# oresat-backplane-2u-hasp.net
KiCad netlist of a schematic drawn in EAGLE
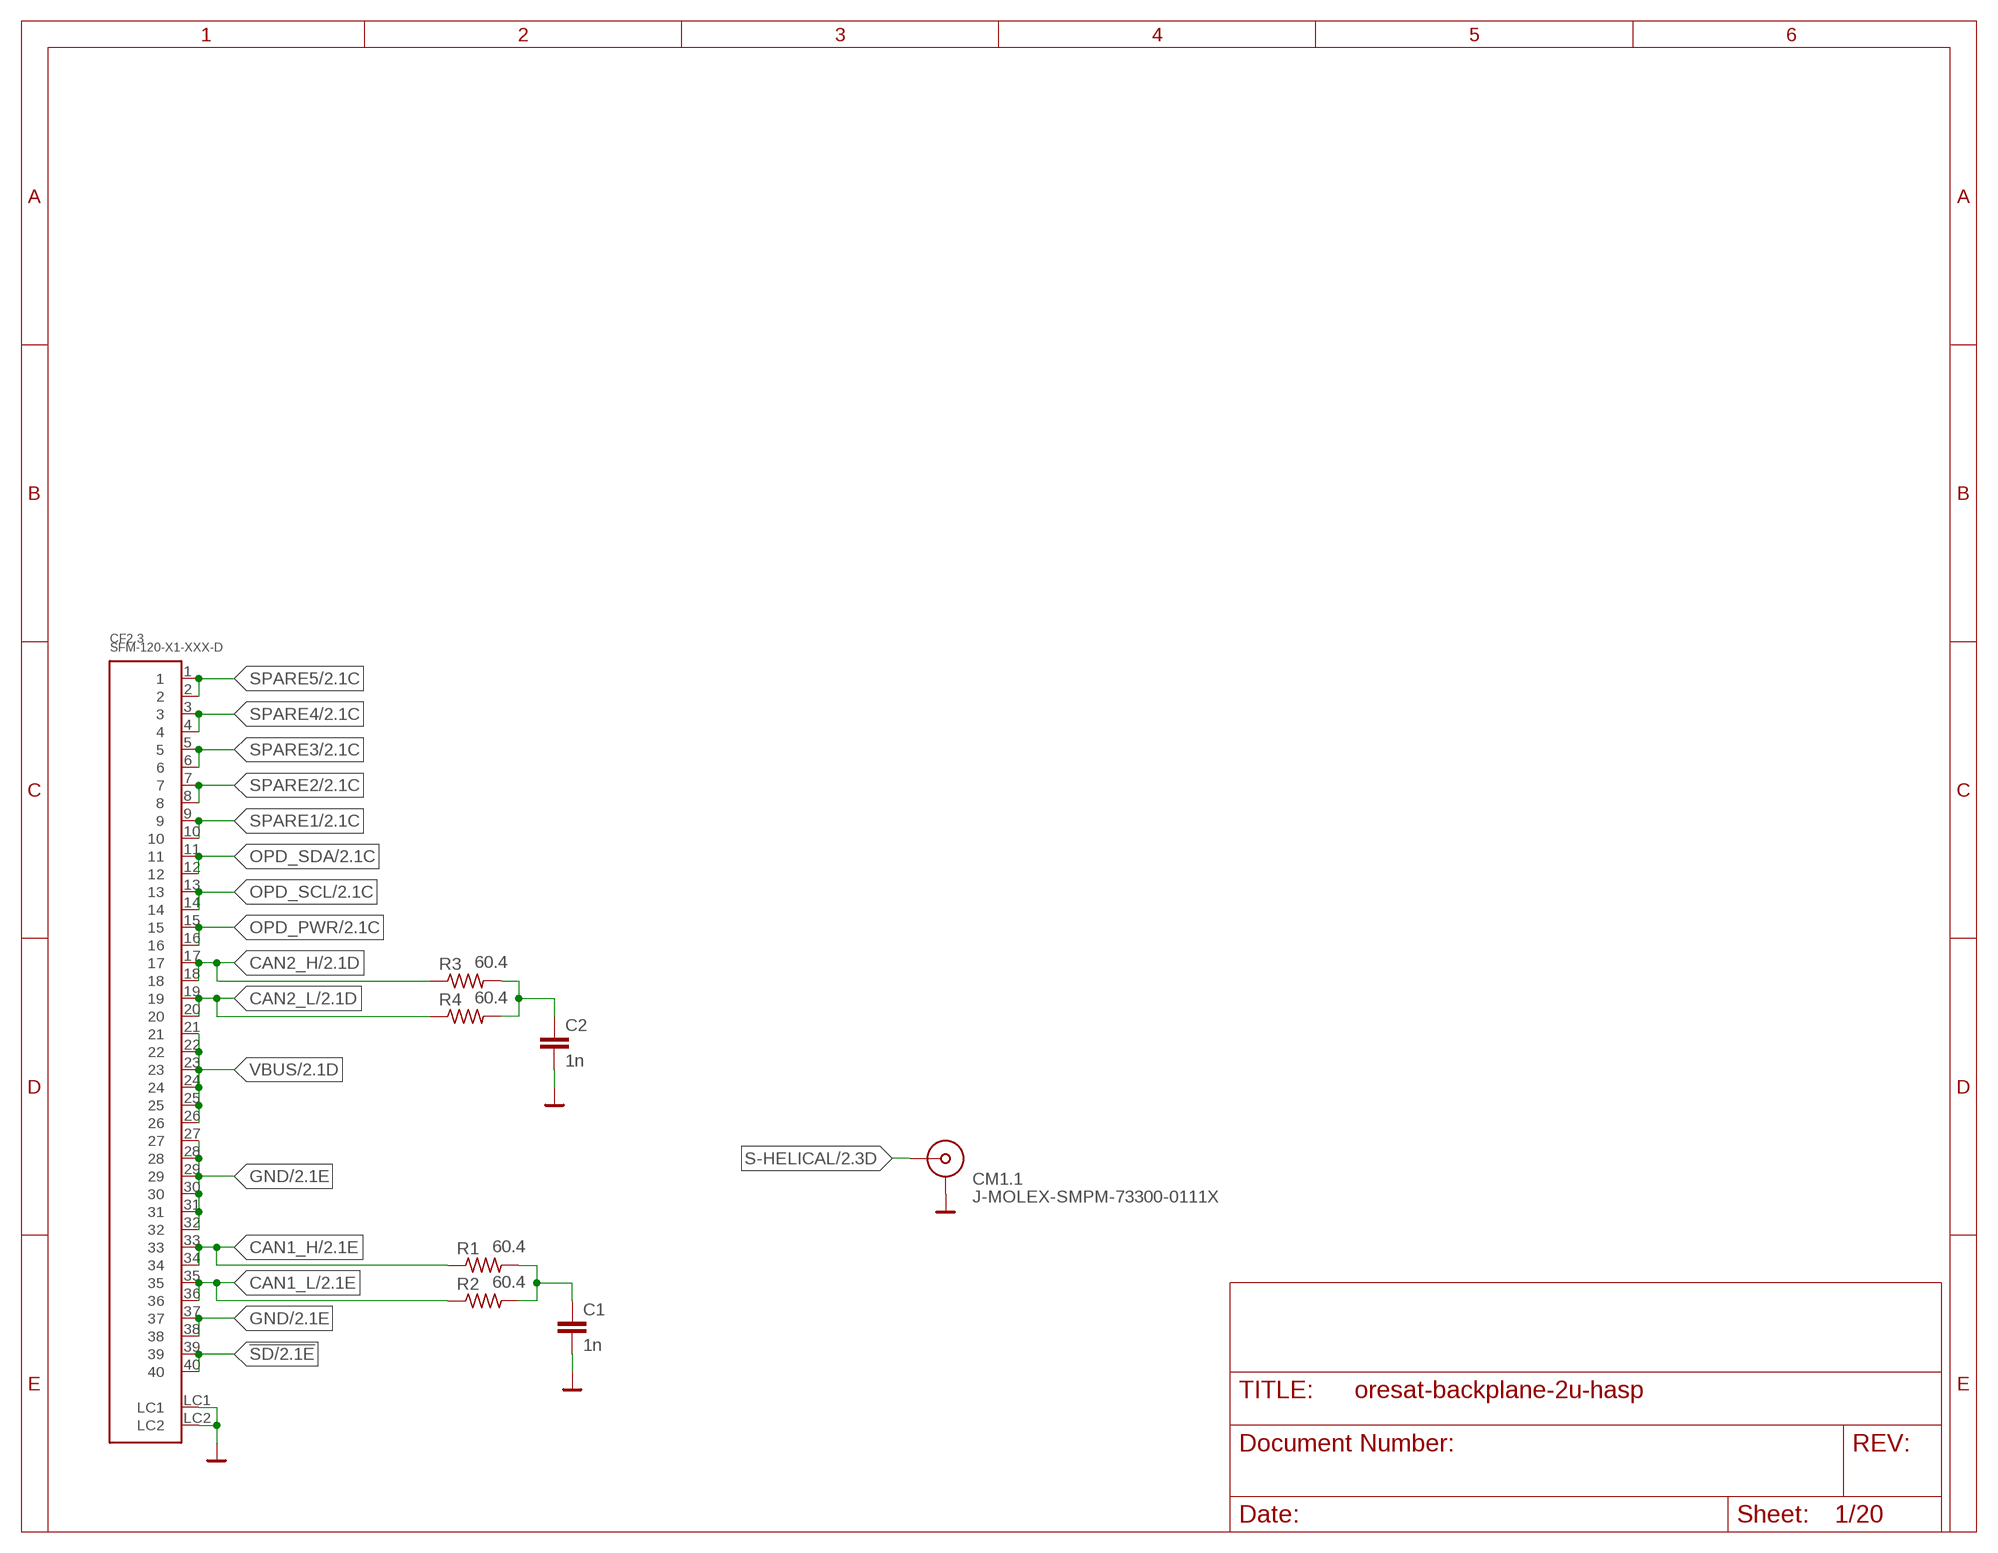
[diagram p0: schematic, sheet 1]
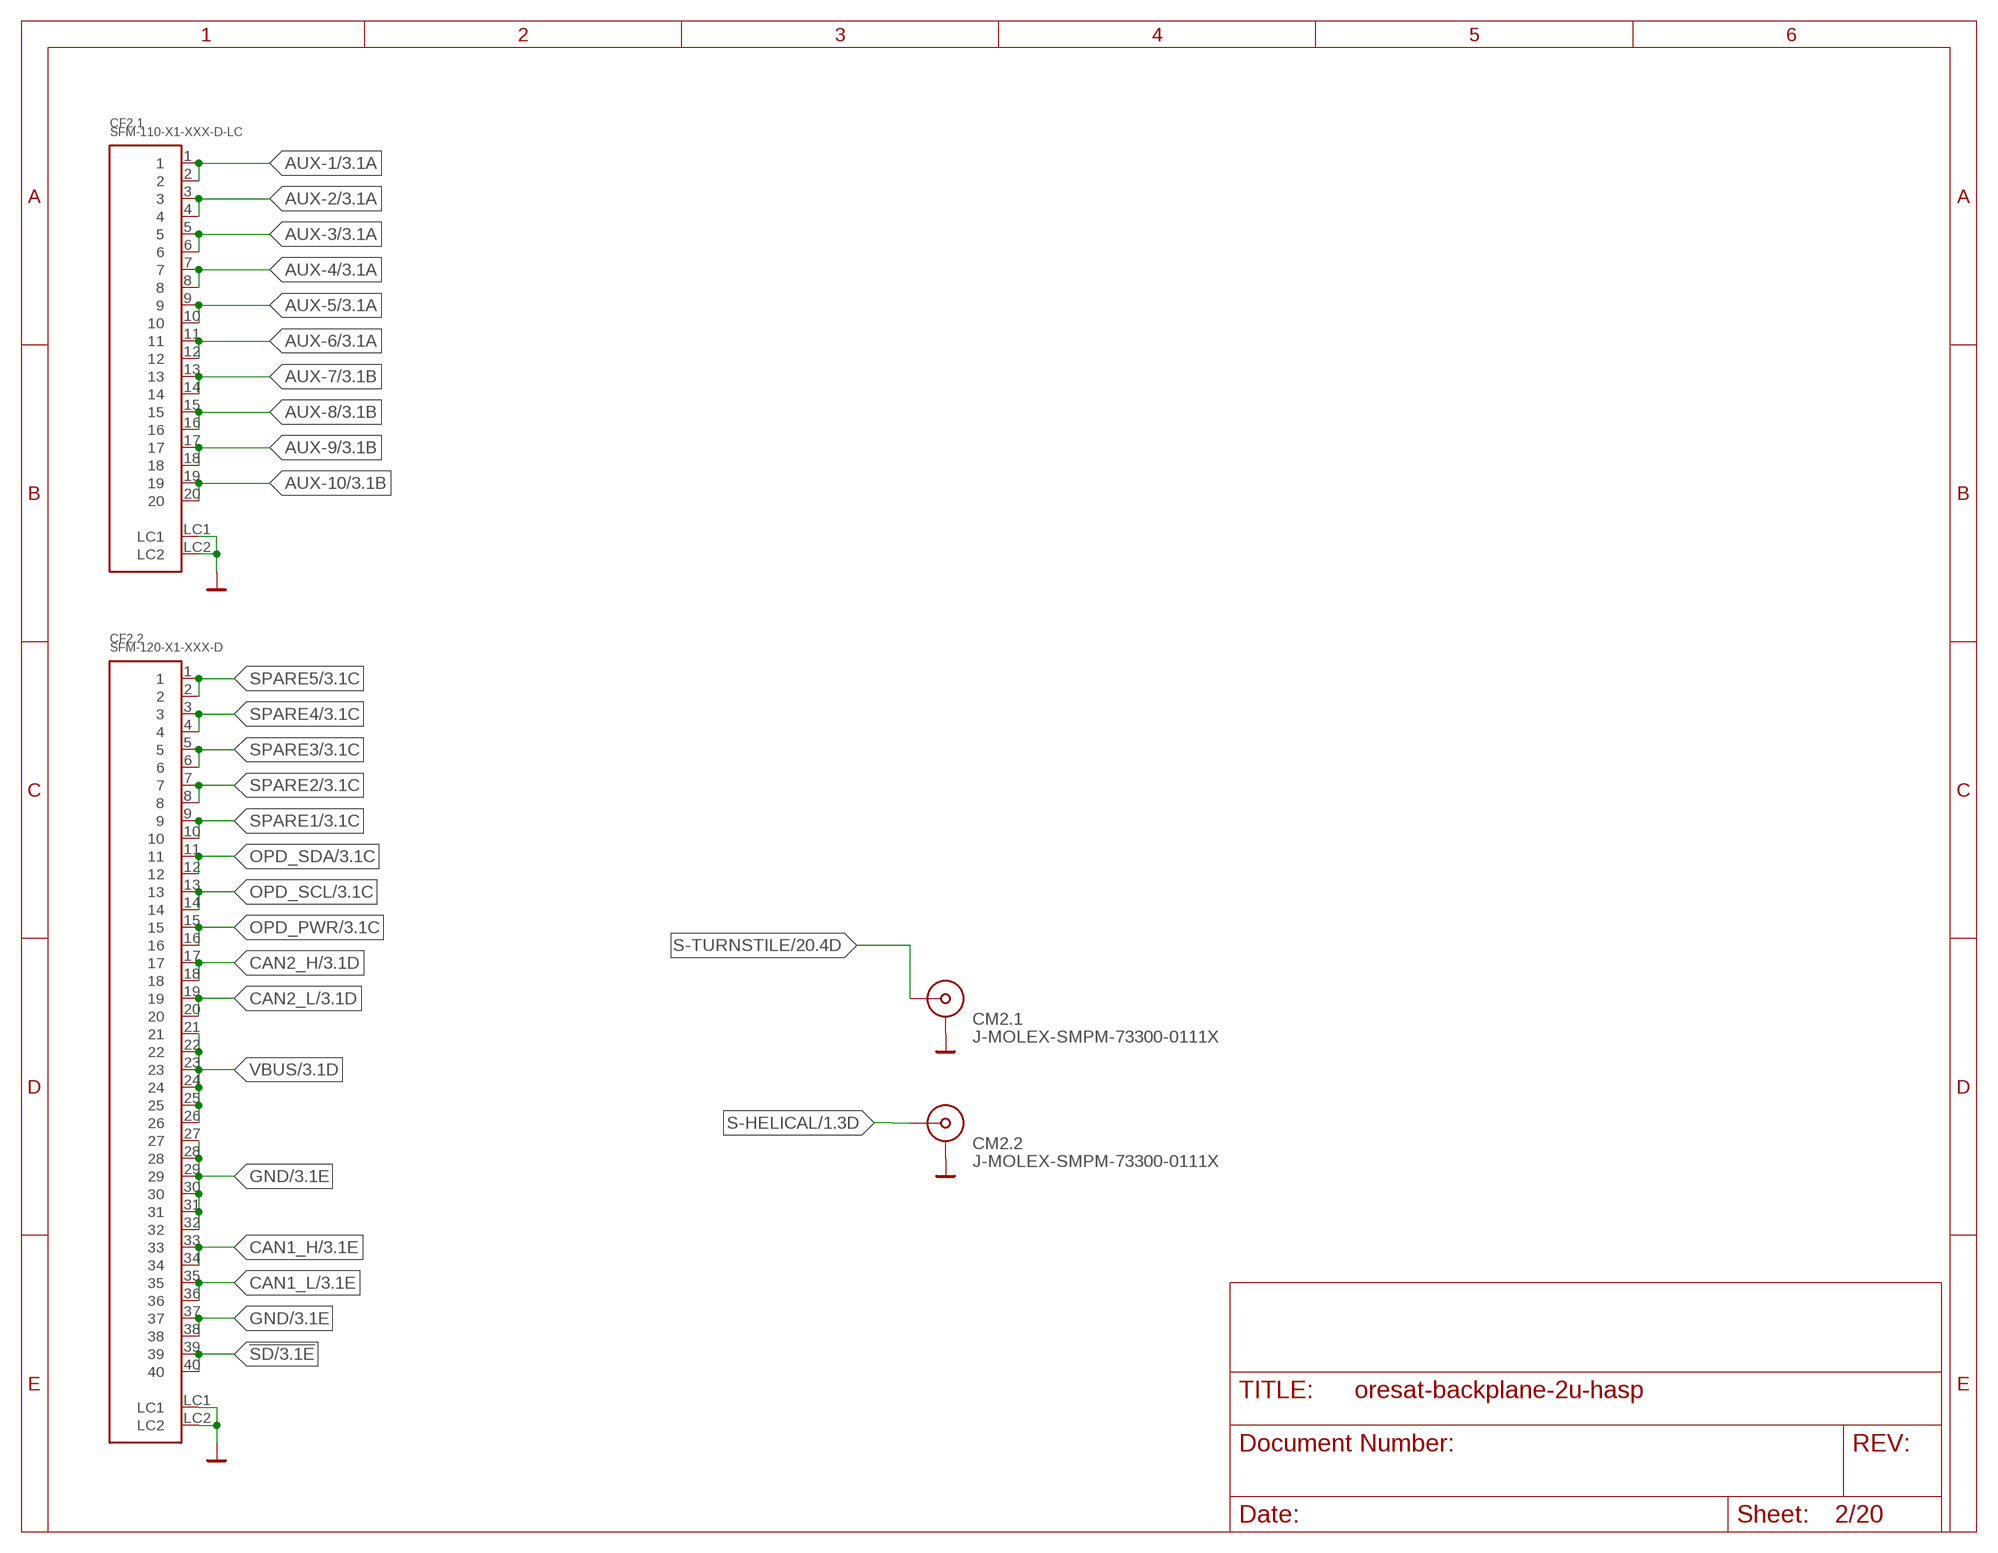
[diagram p1: schematic, sheet 2]
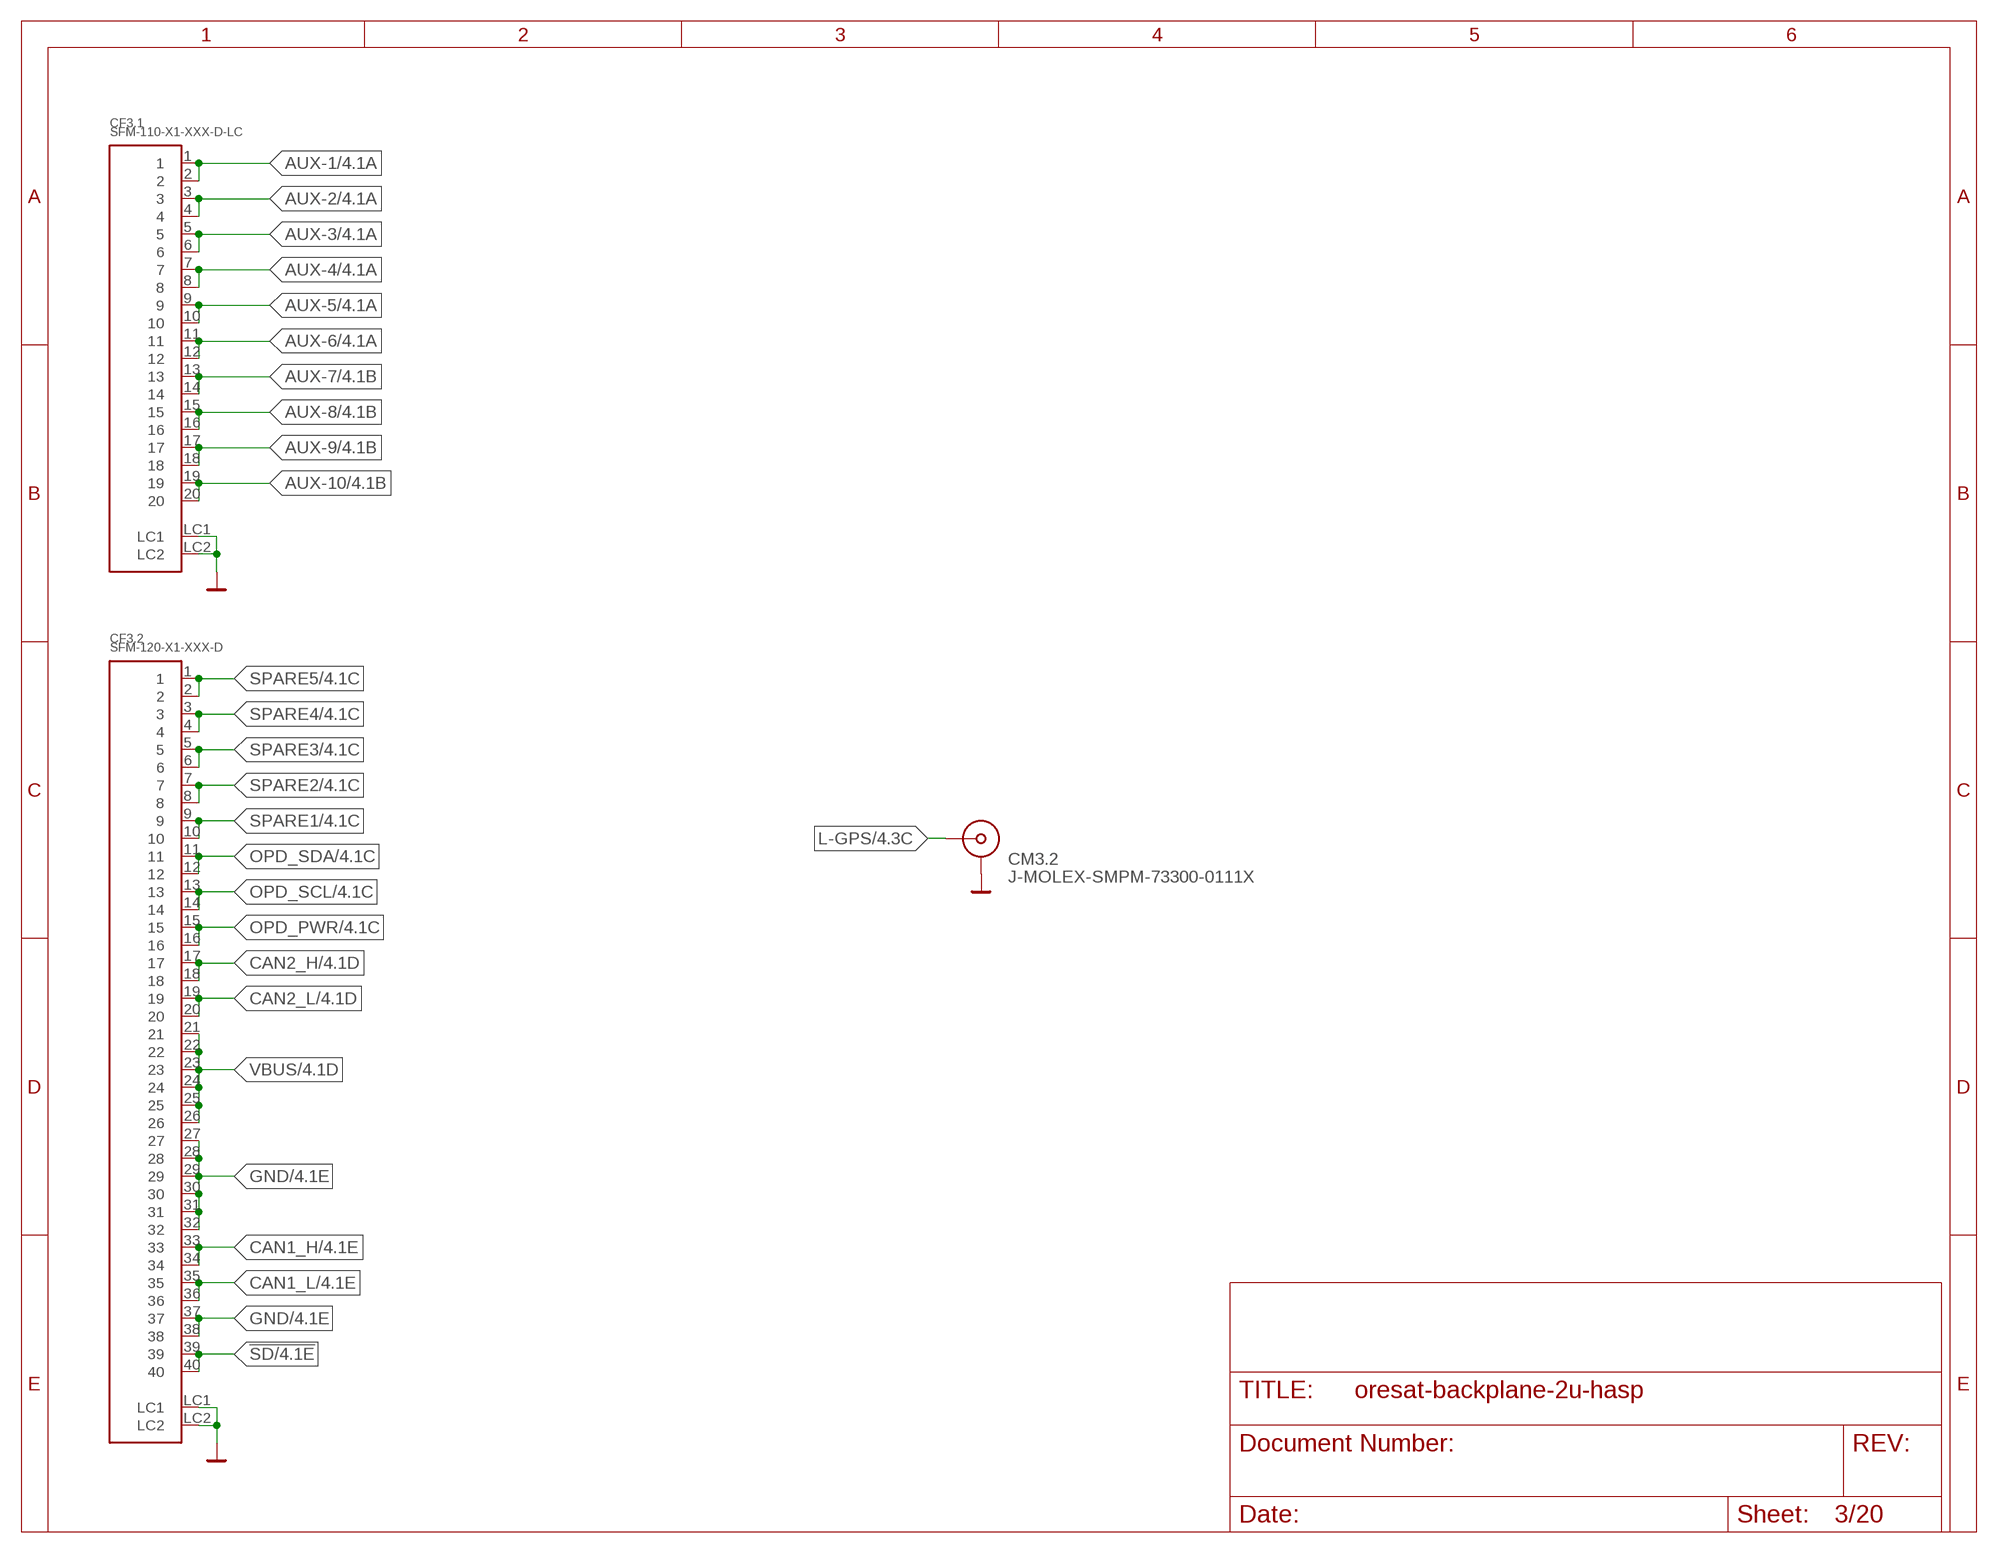
[diagram p2: schematic, sheet 3]
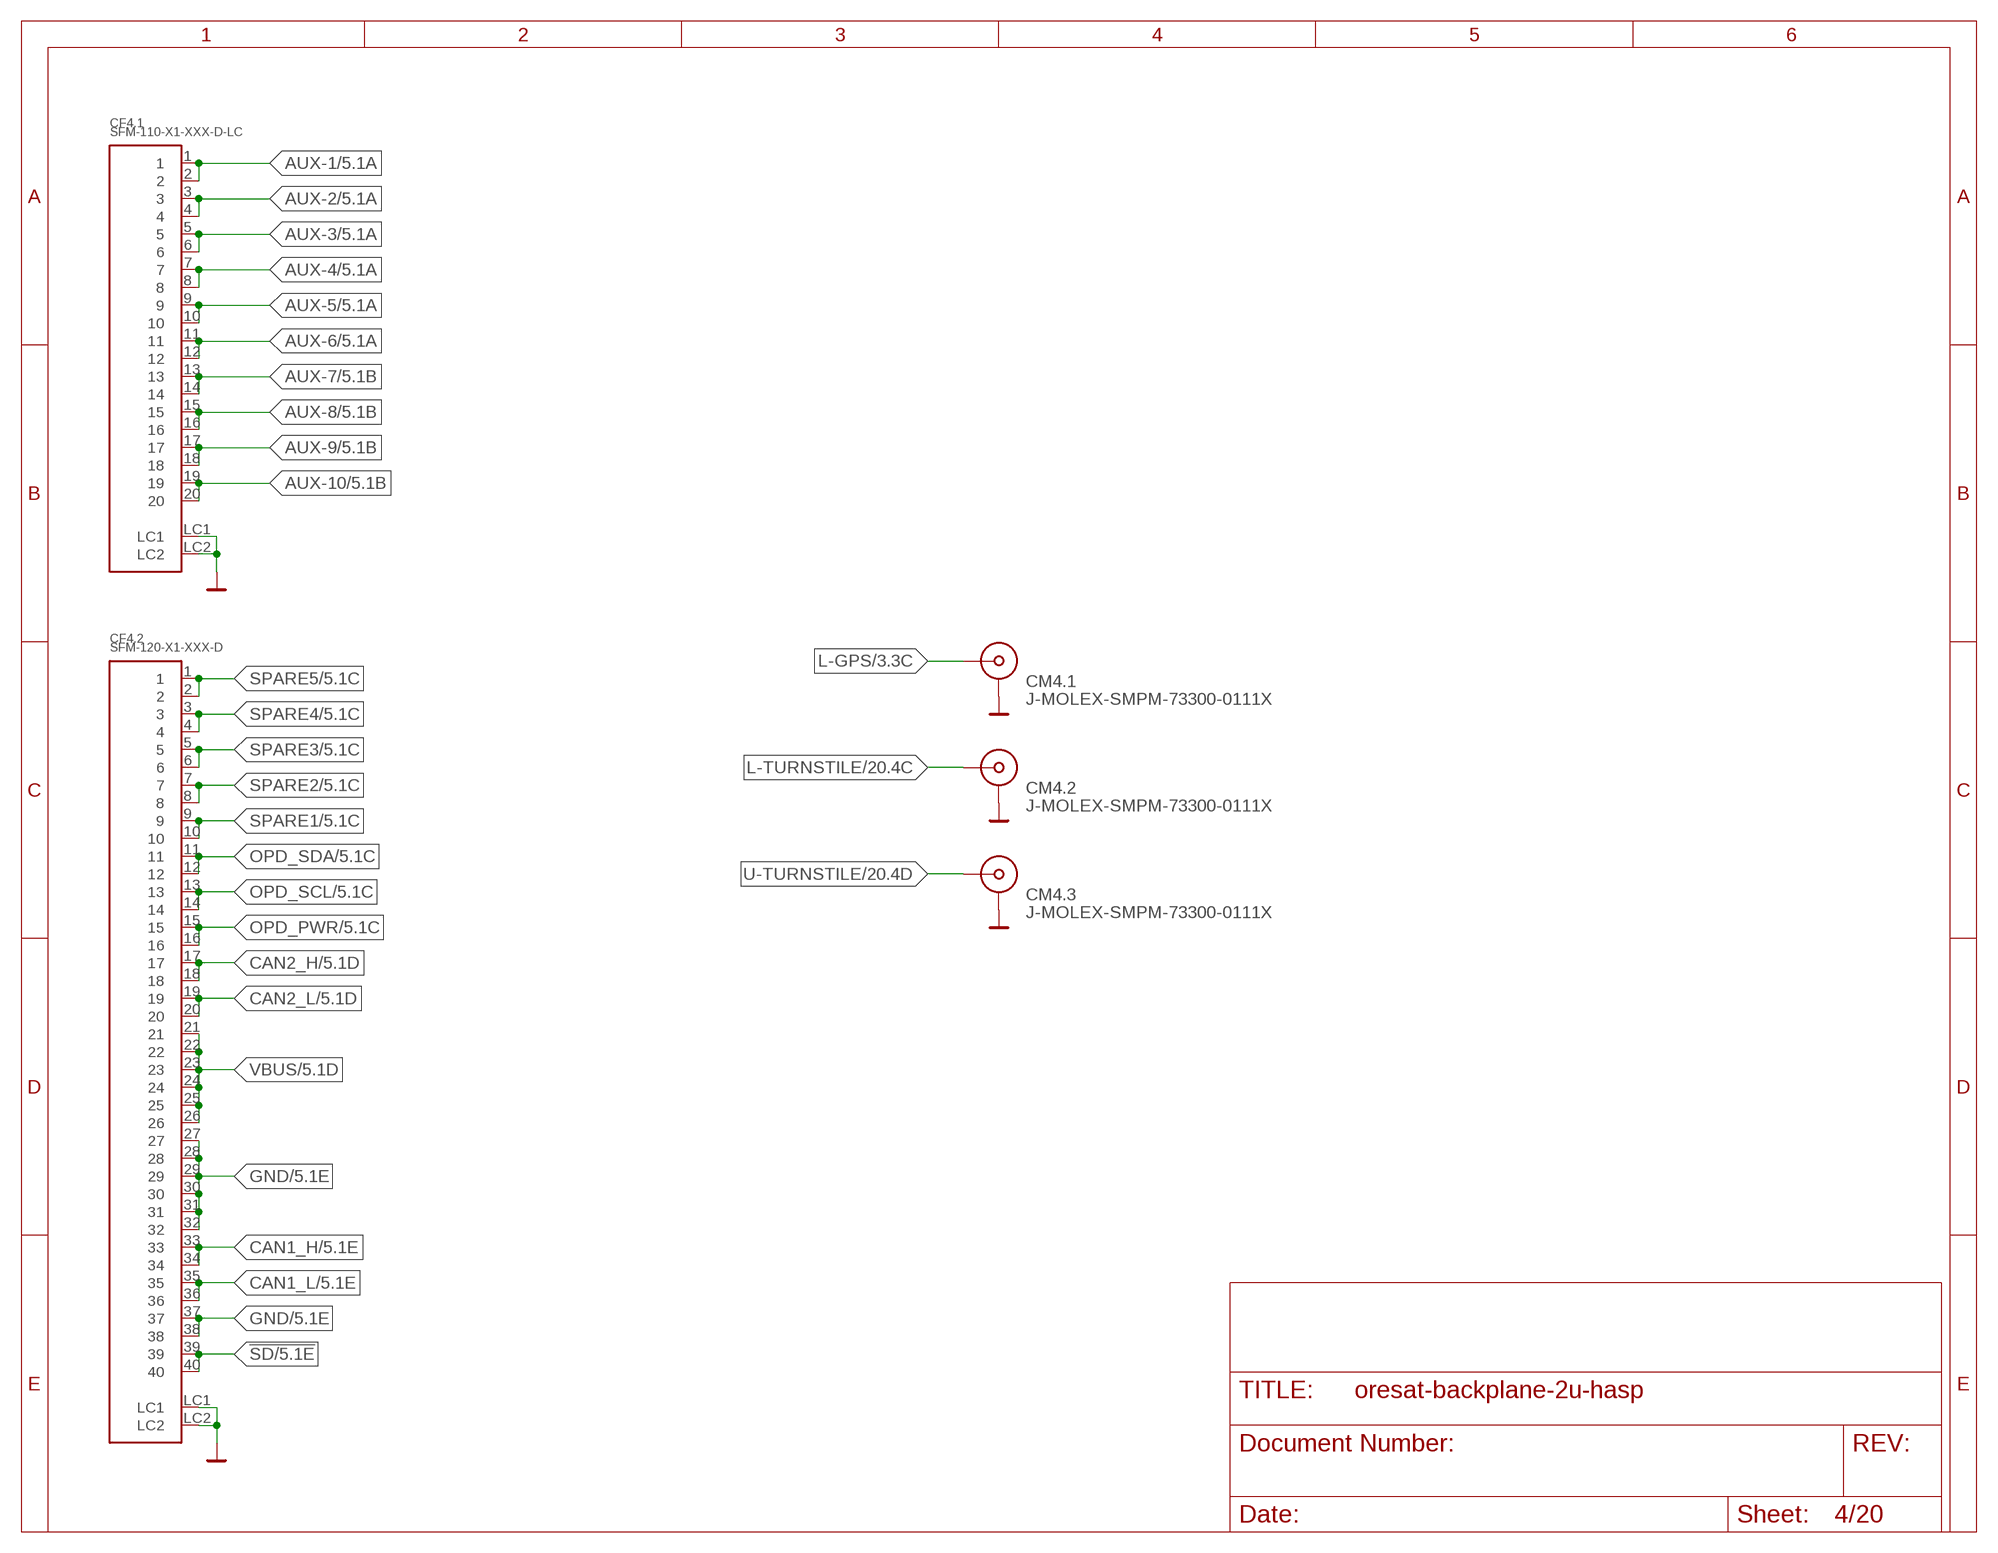
[diagram p3: schematic, sheet 4]
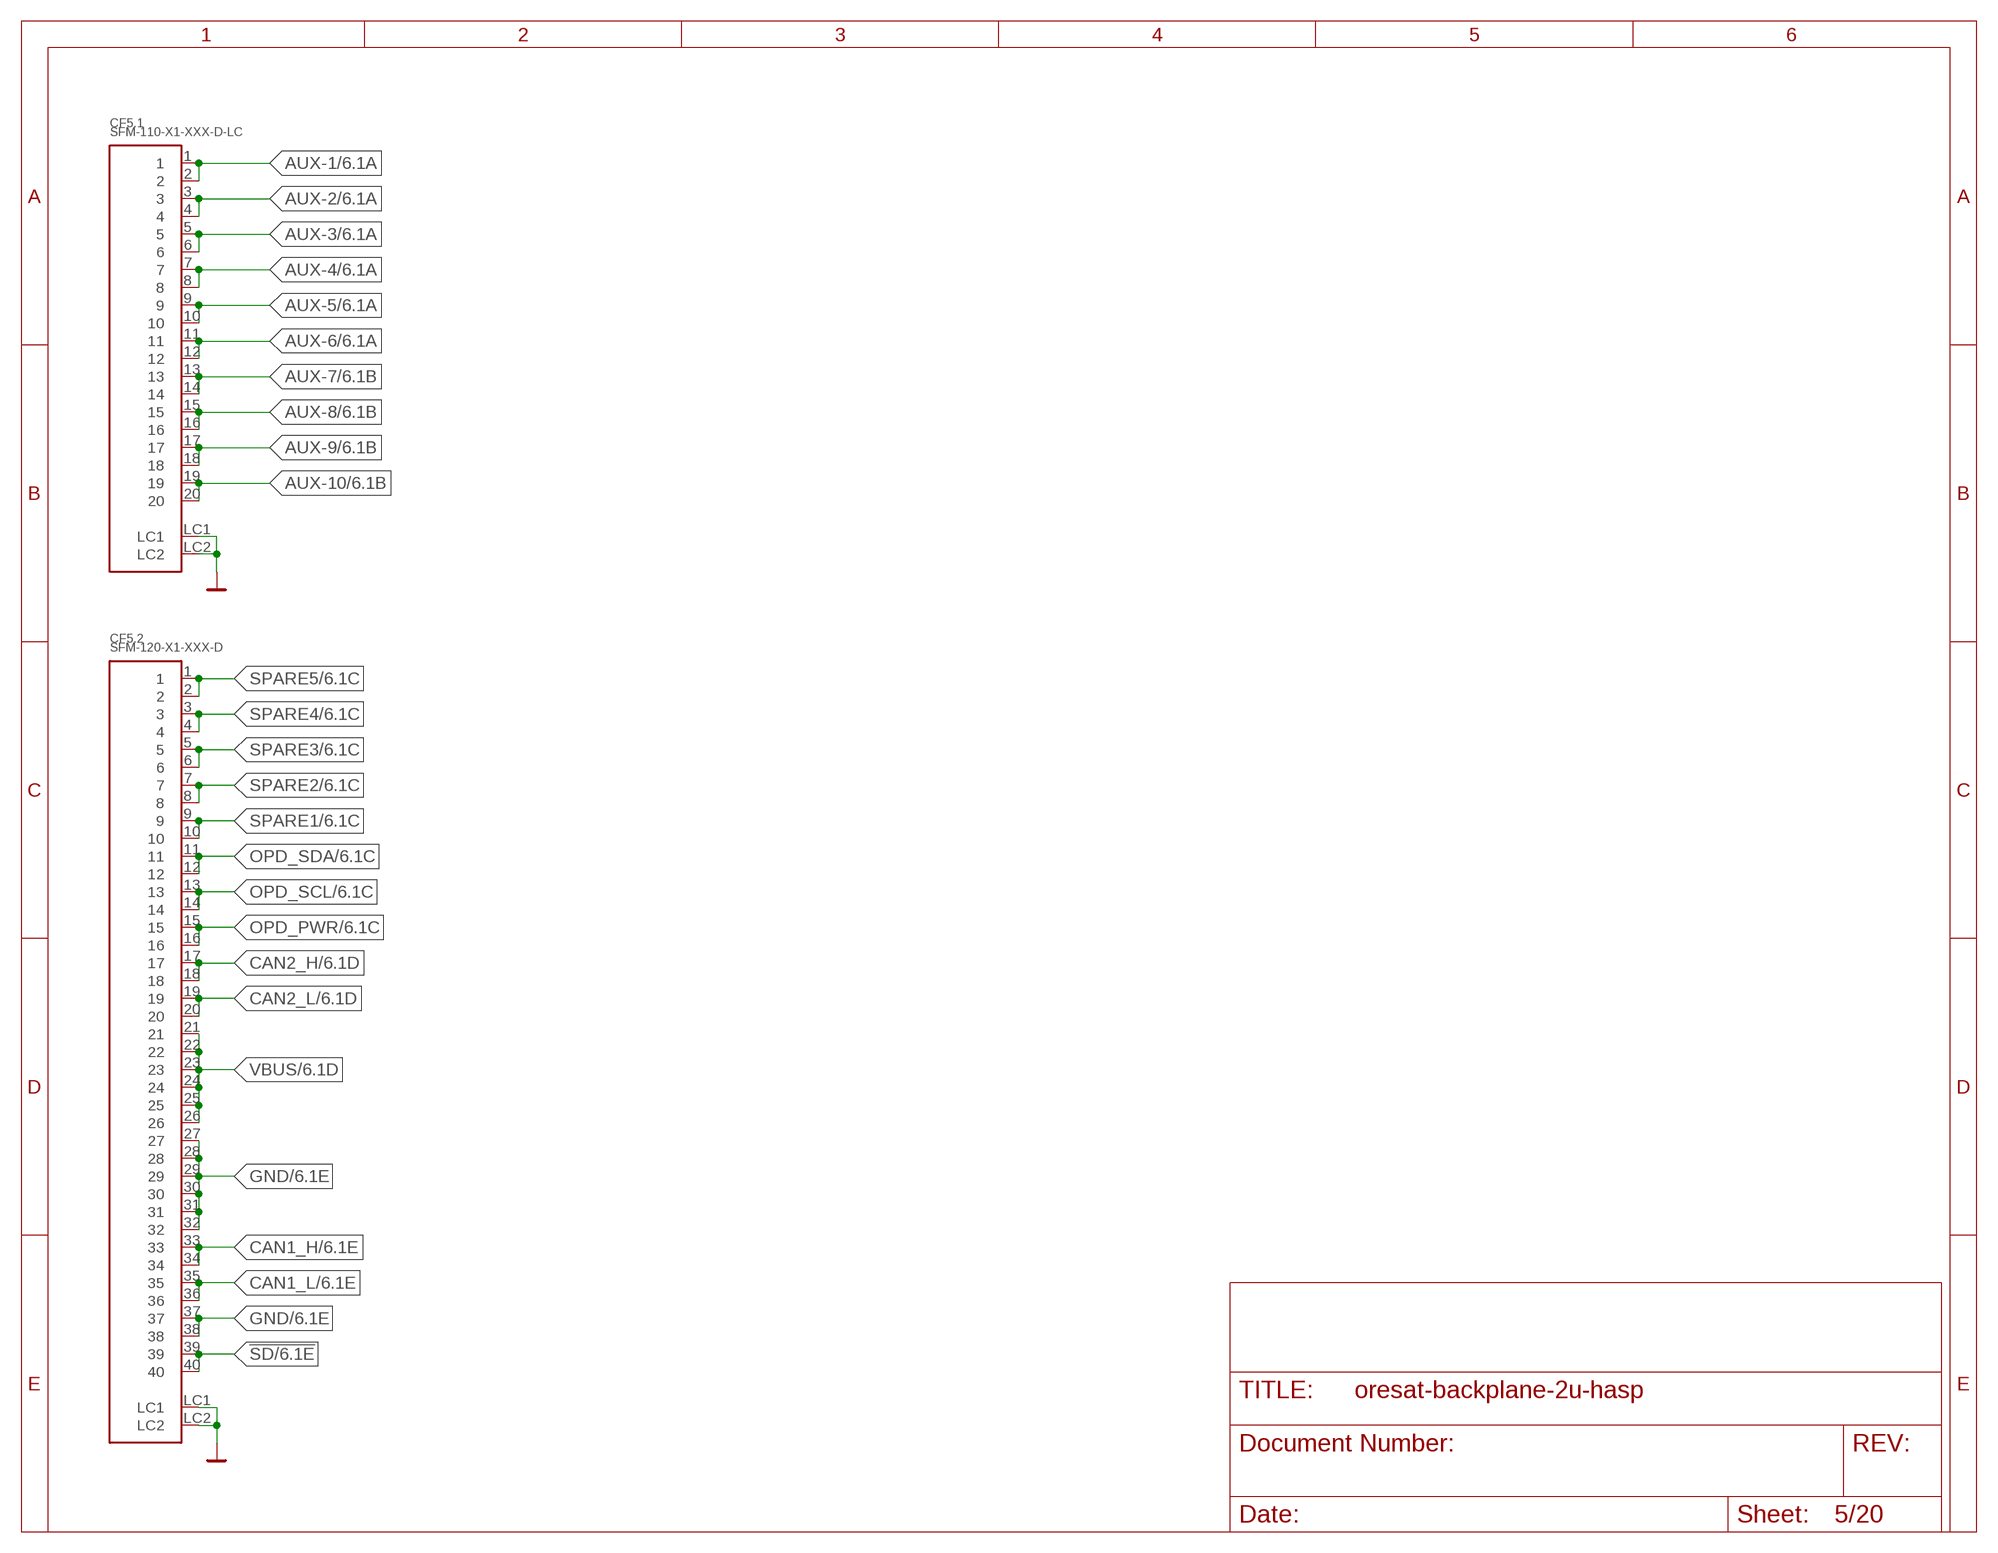
[diagram p4: schematic, sheet 5]
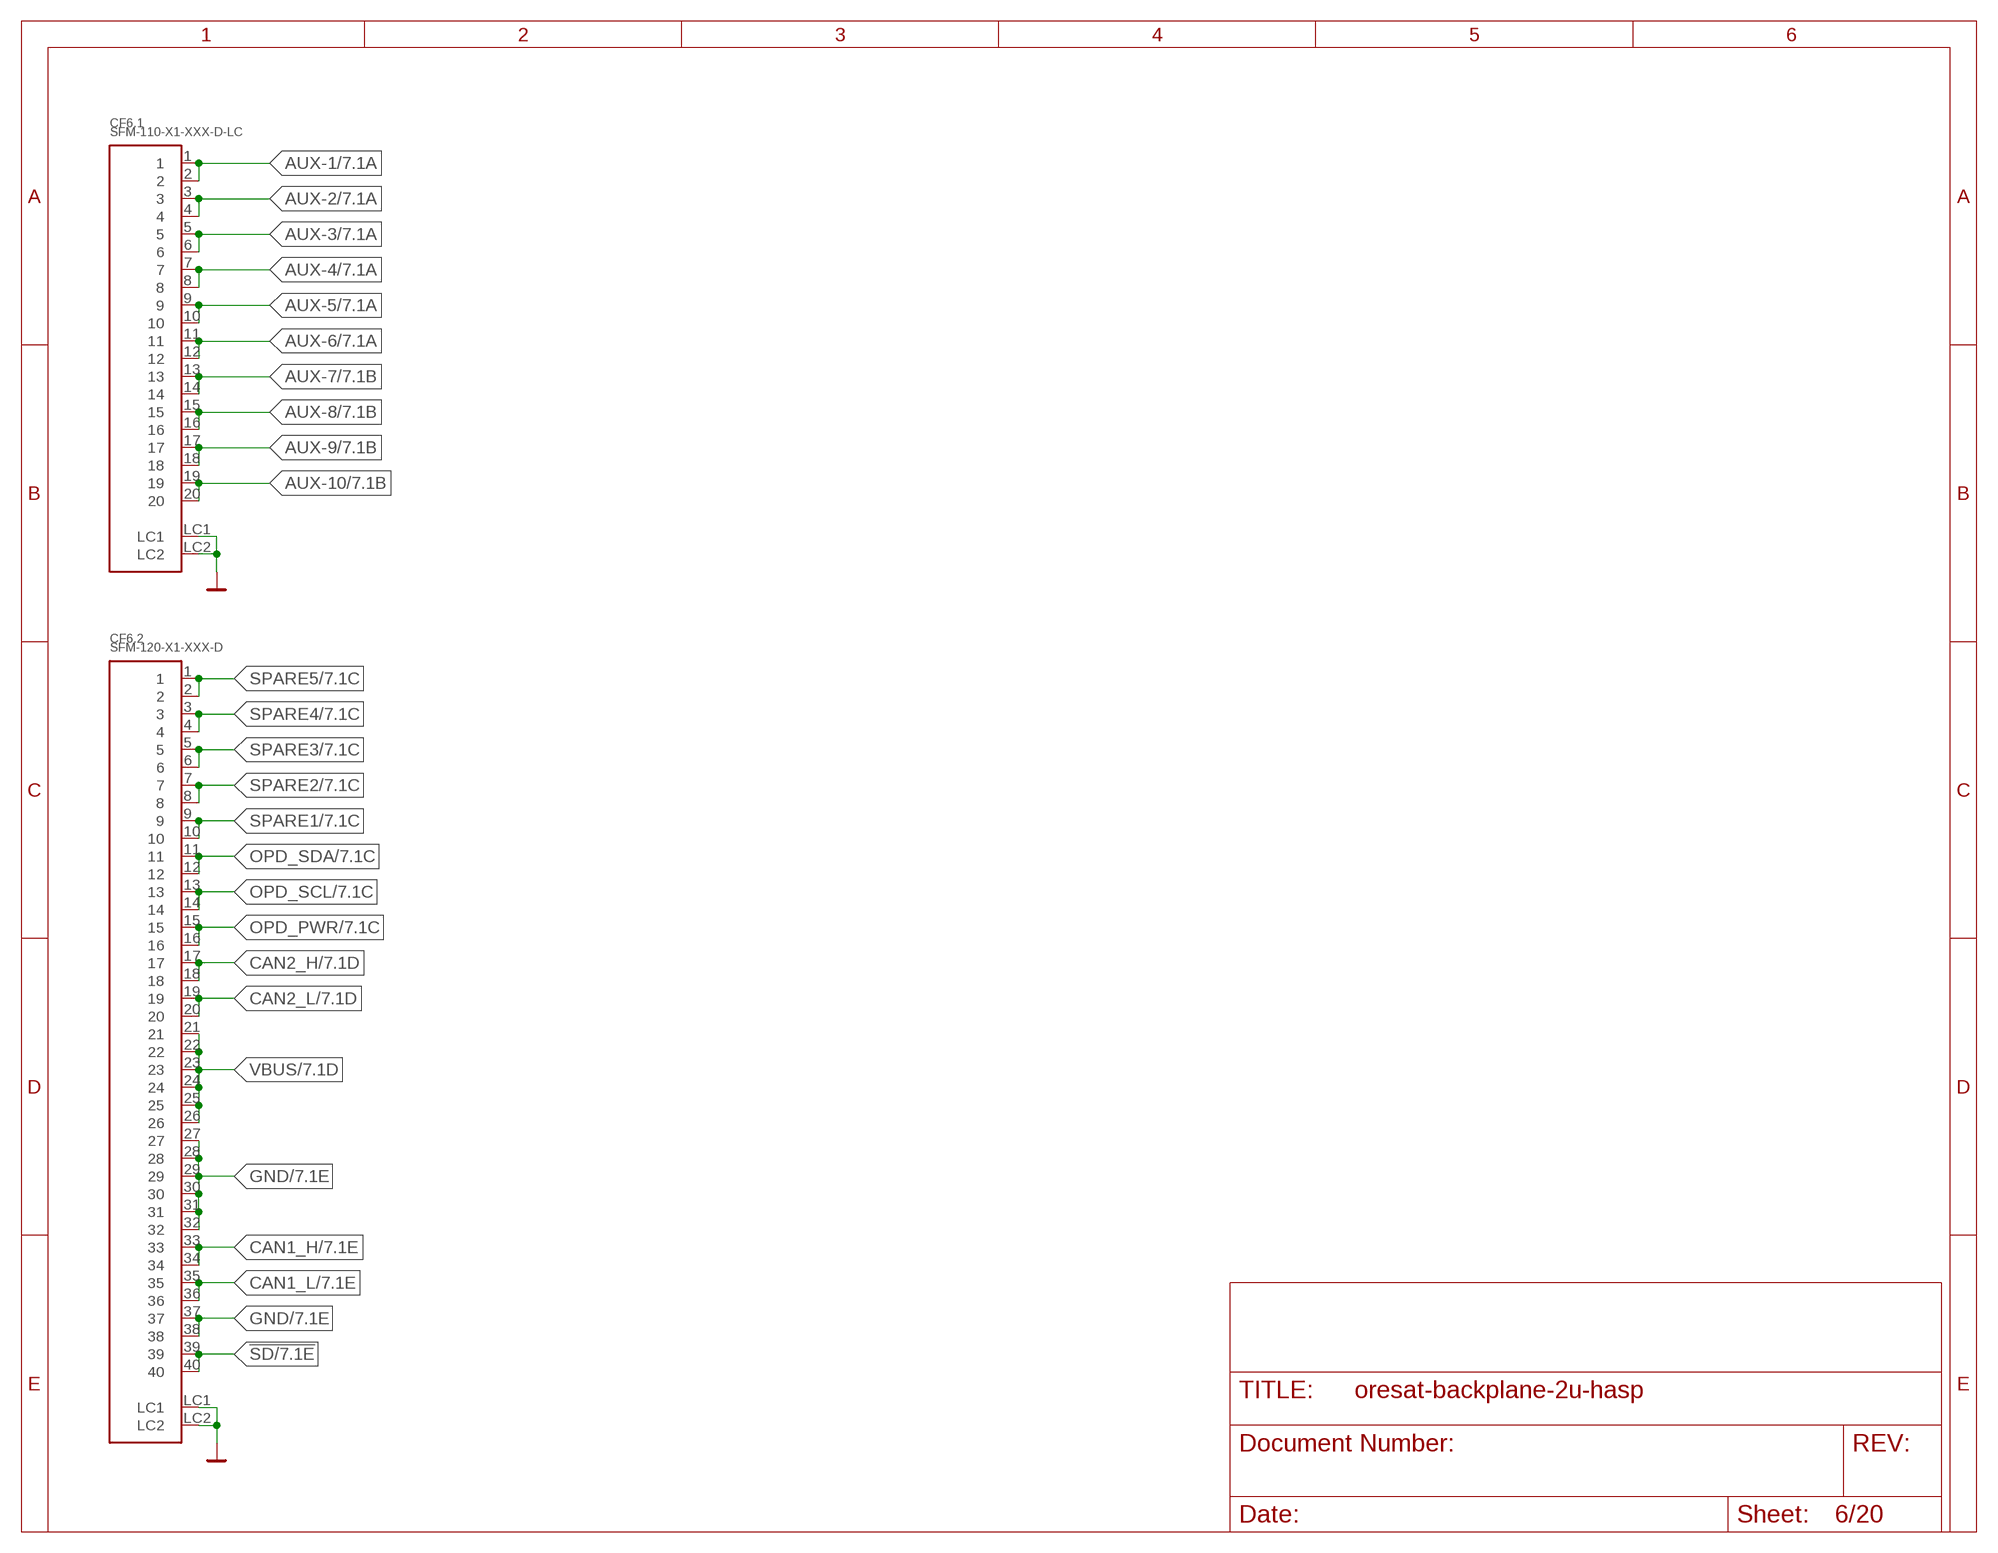
[diagram p5: schematic, sheet 6]
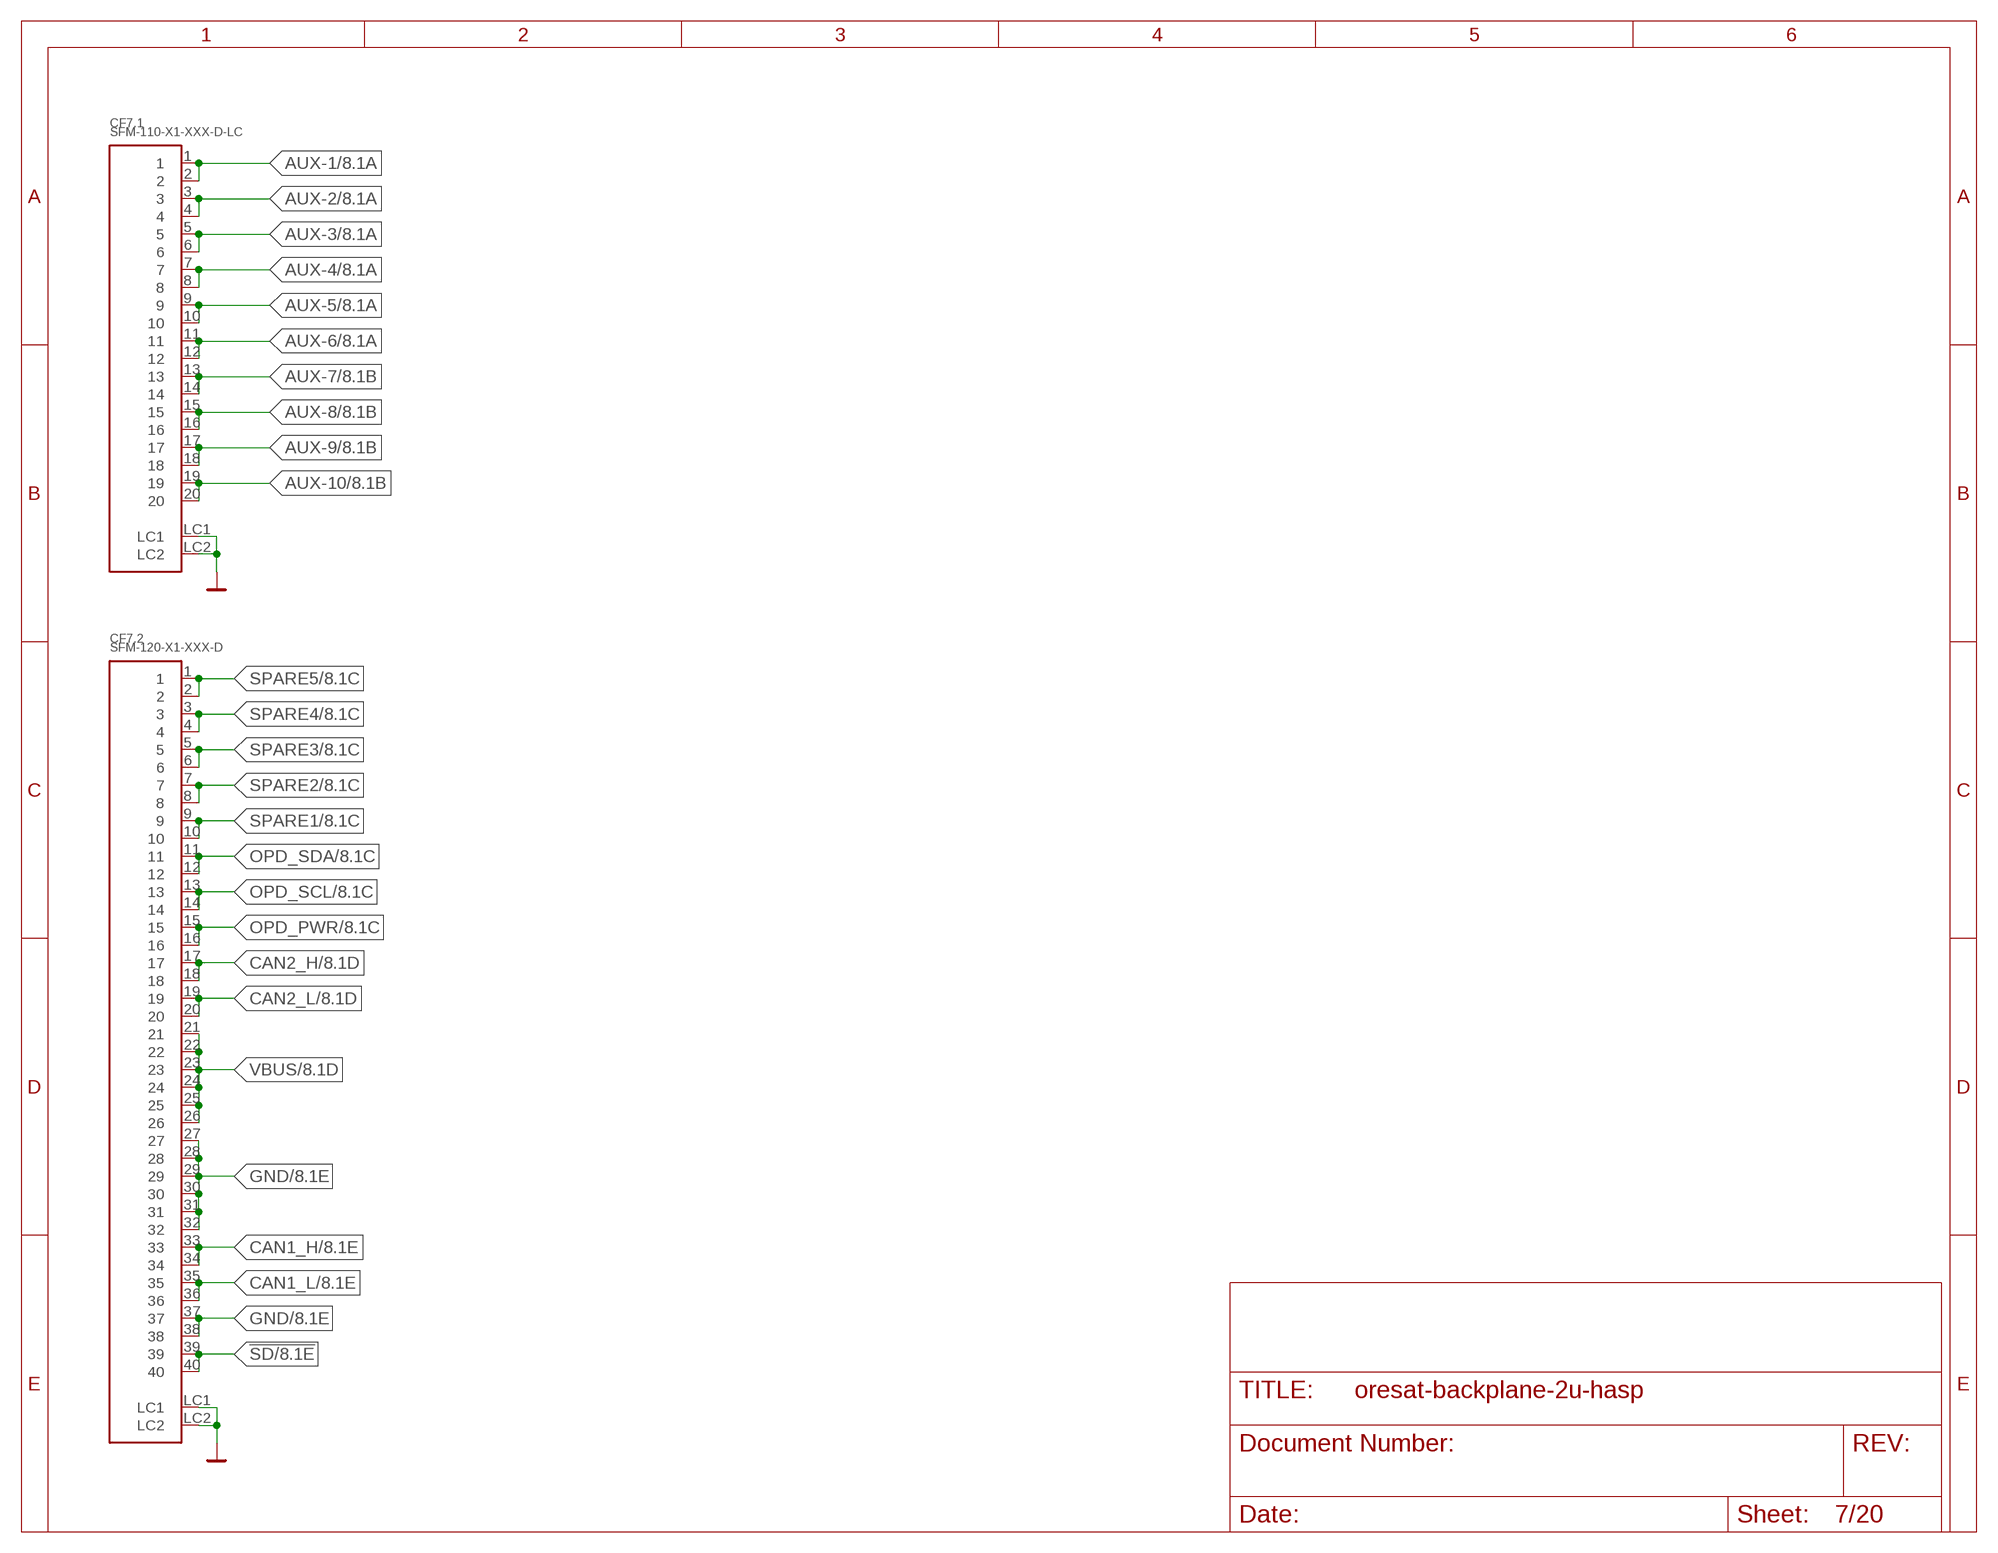
[diagram p6: schematic, sheet 7]
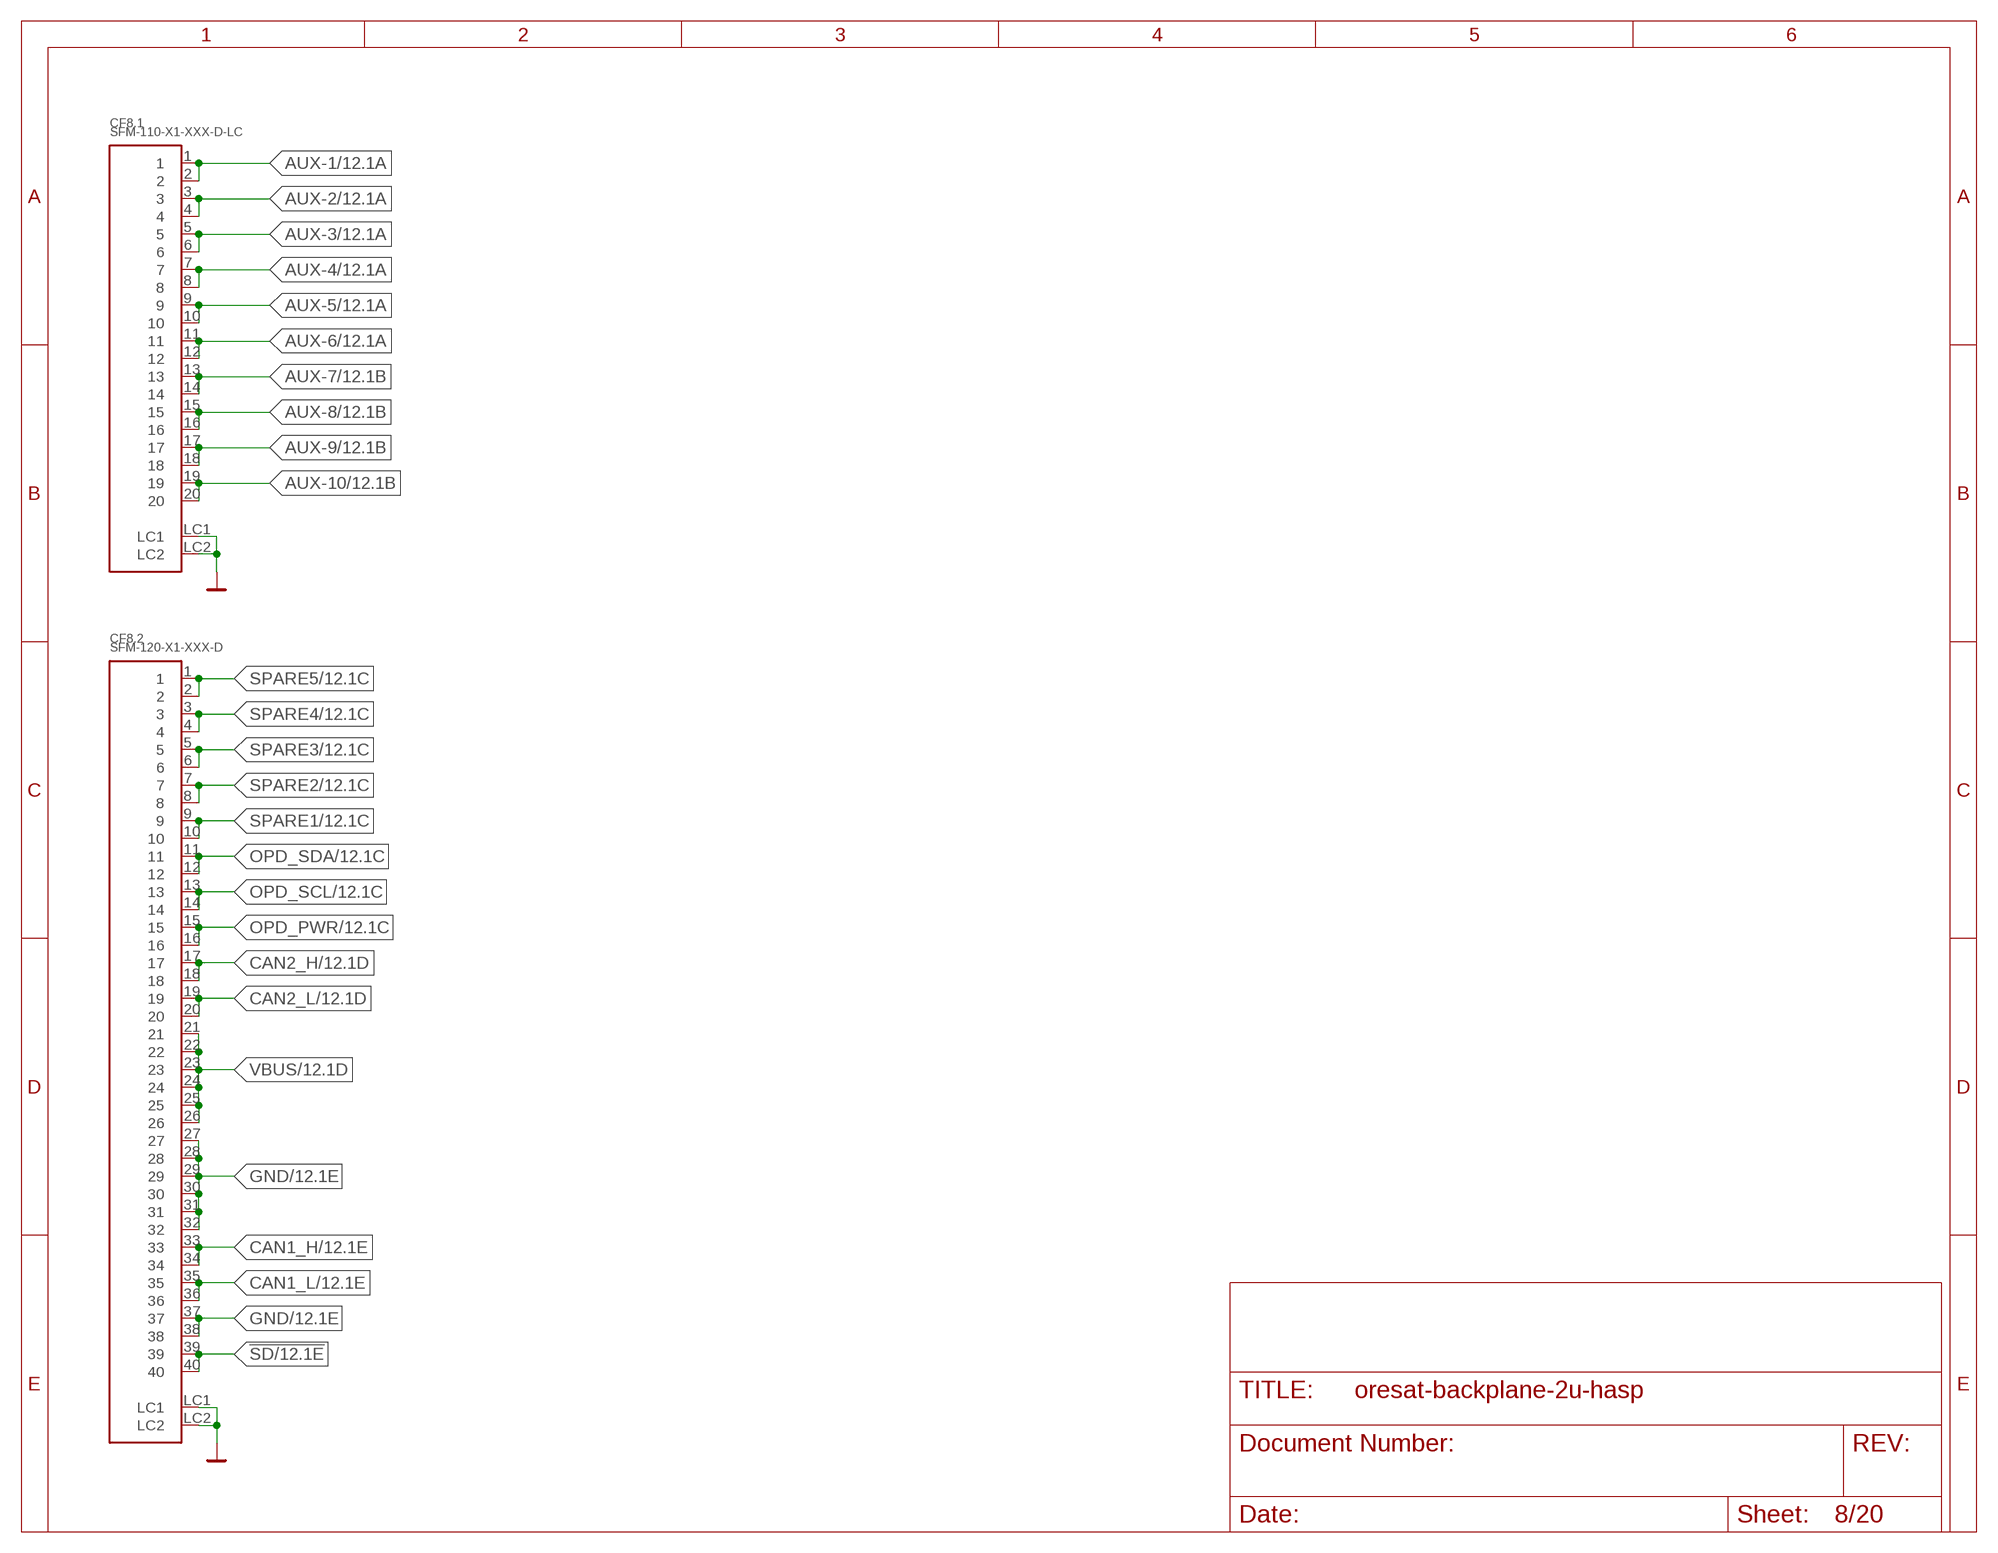
[diagram p7: schematic, sheet 8]
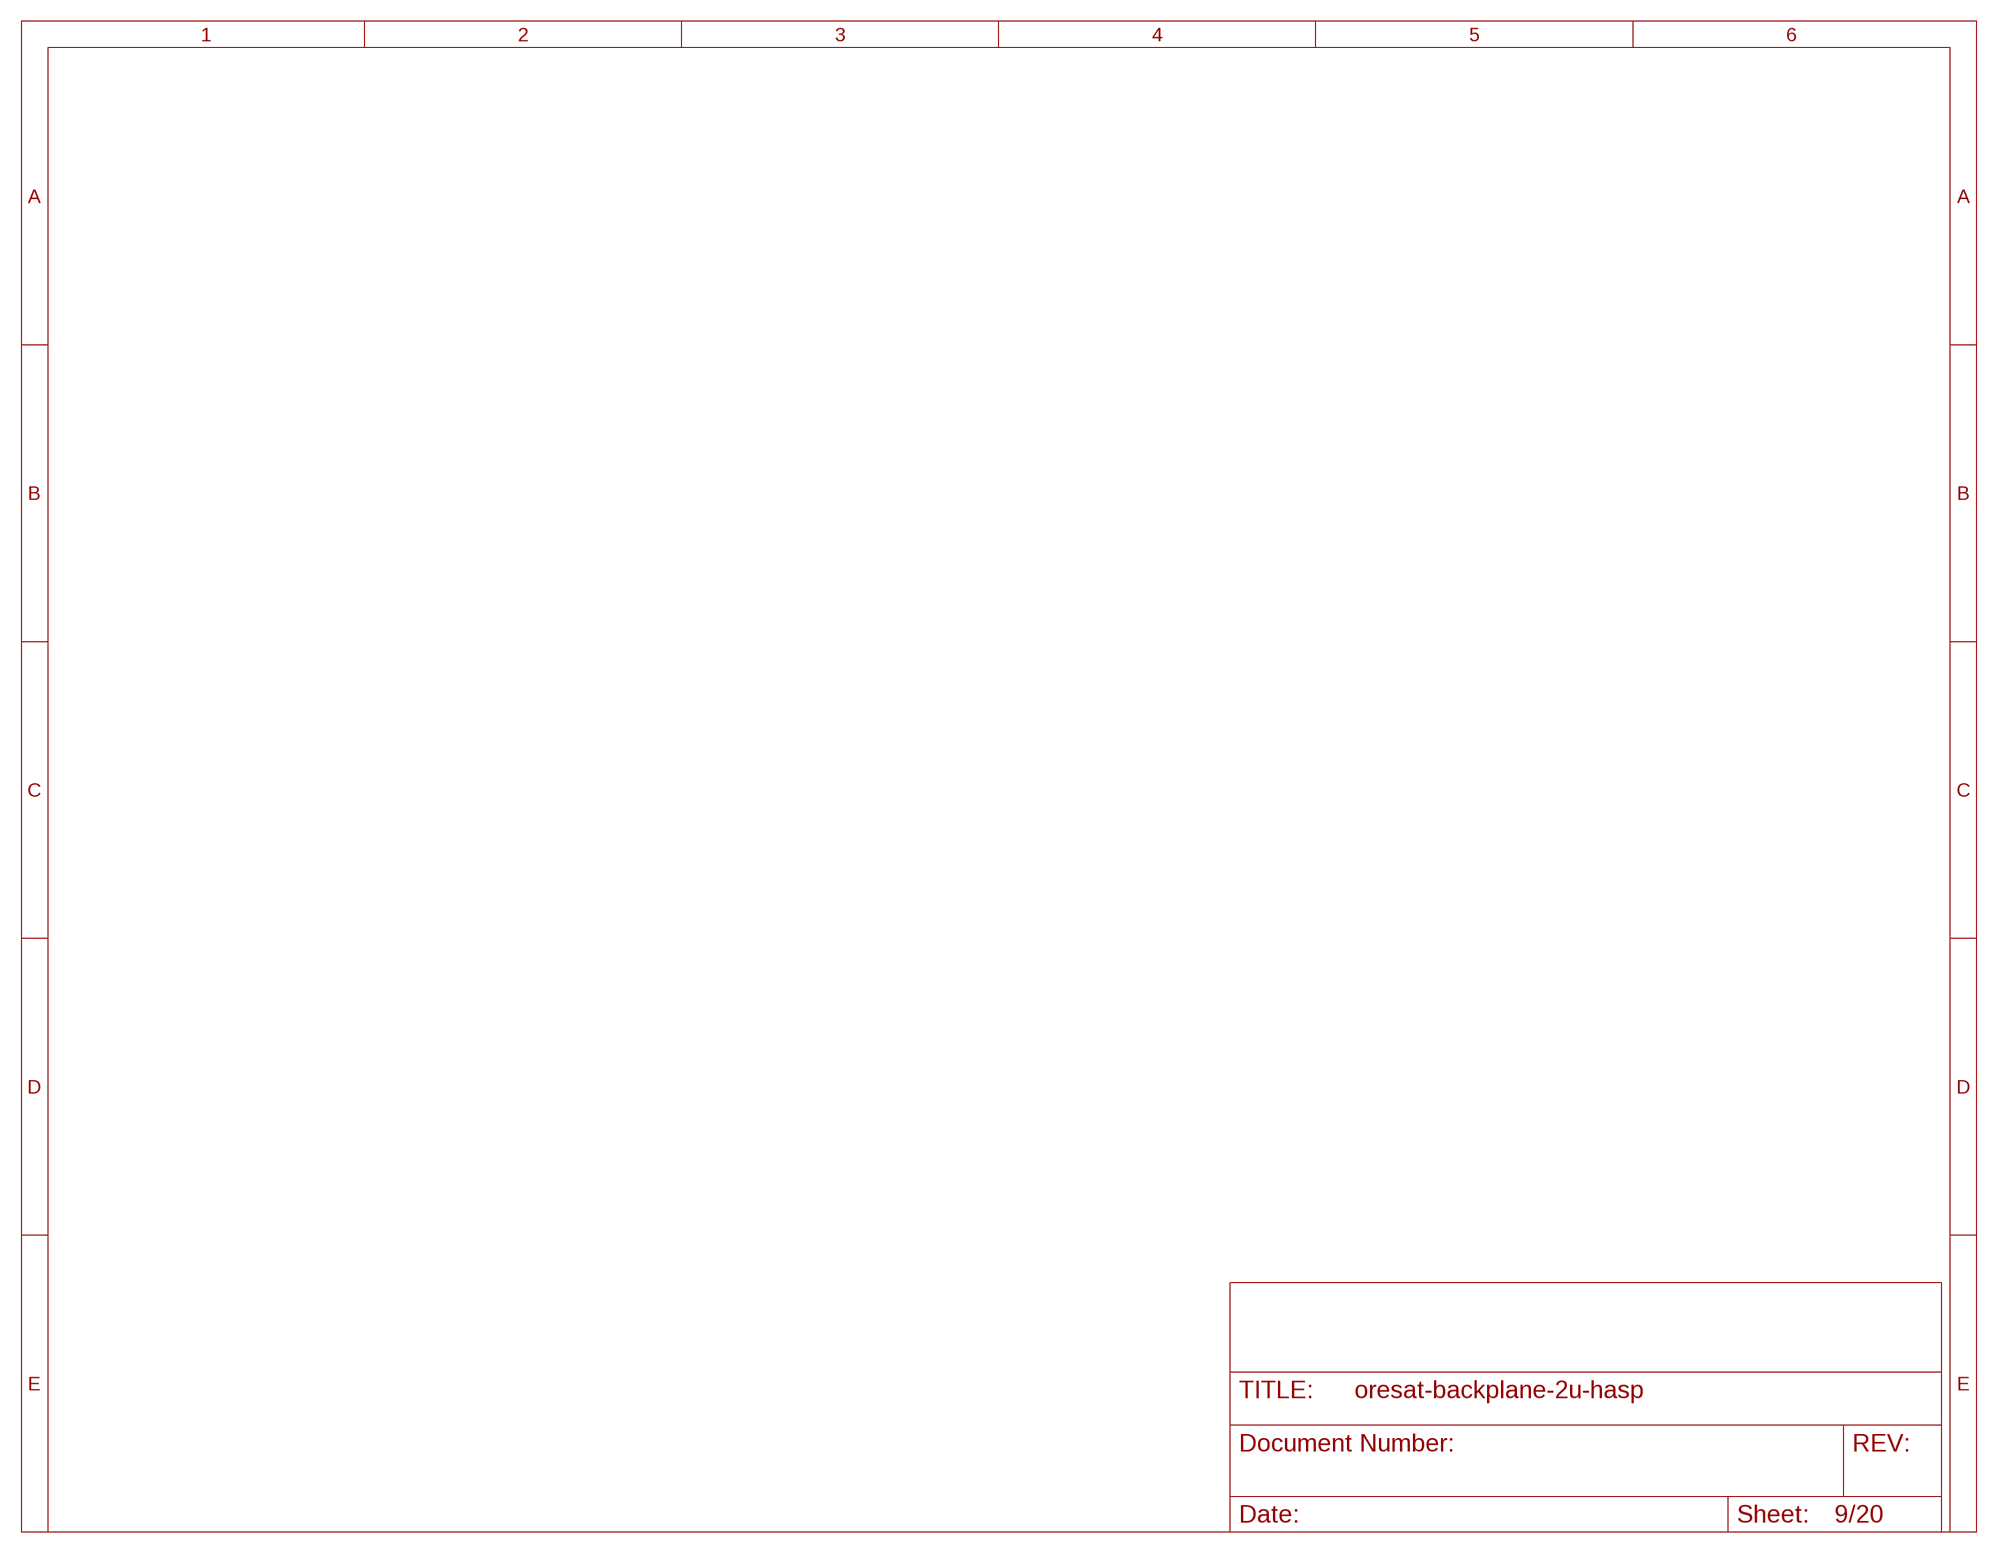
[diagram p8: schematic, sheet 9]
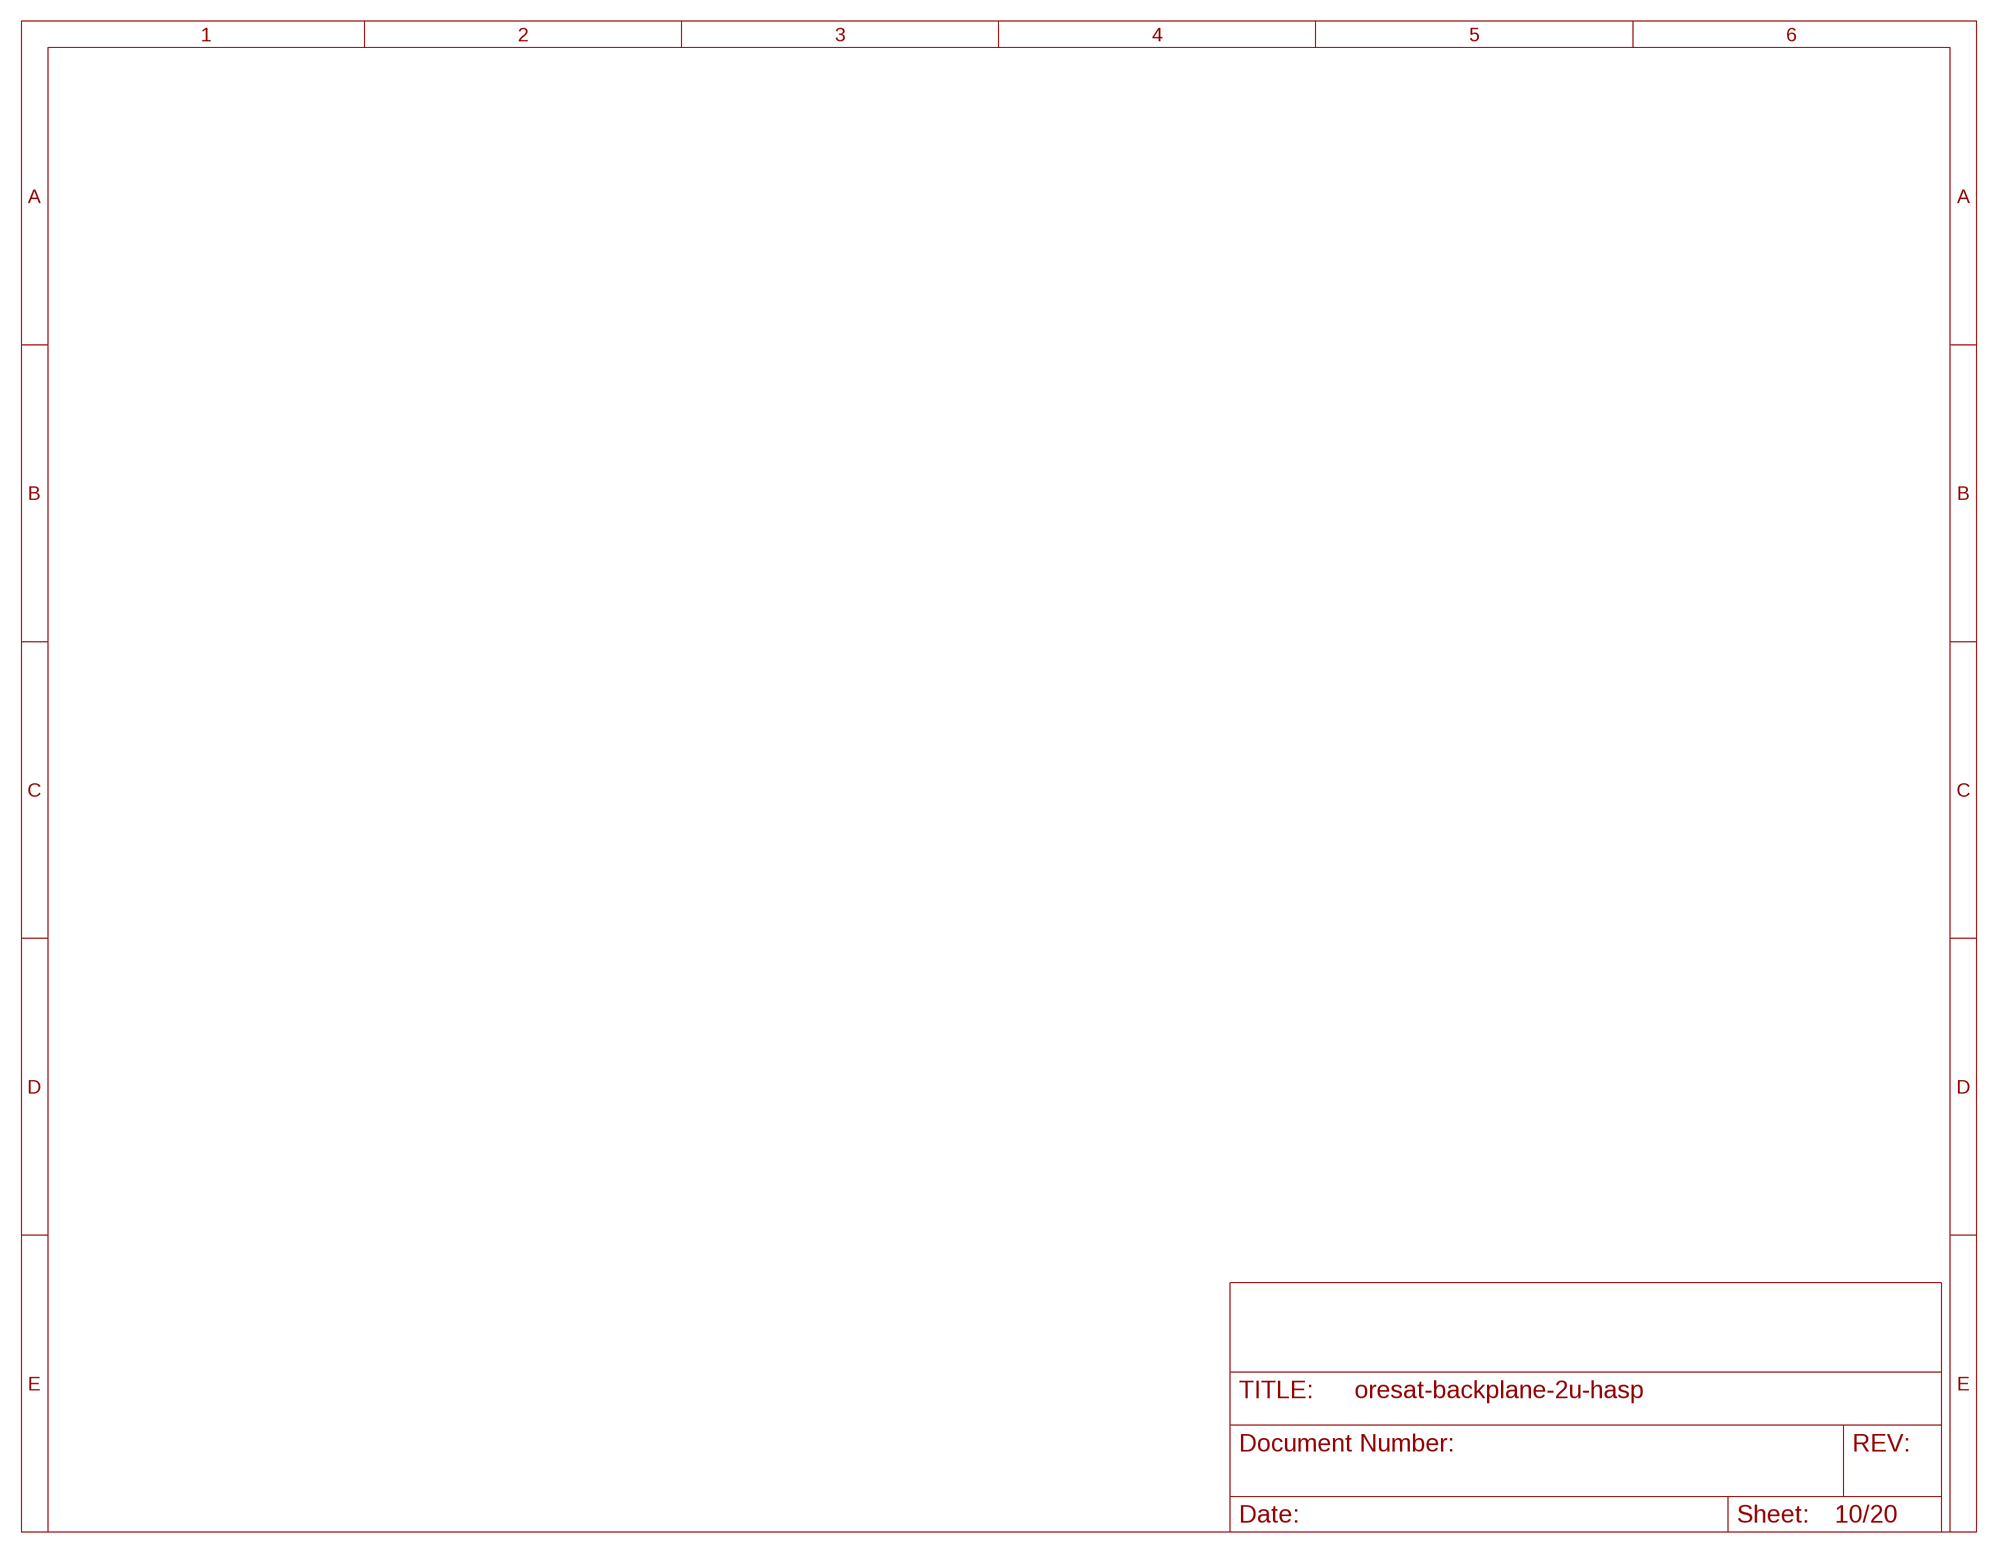
[diagram p9: schematic, sheet 10]
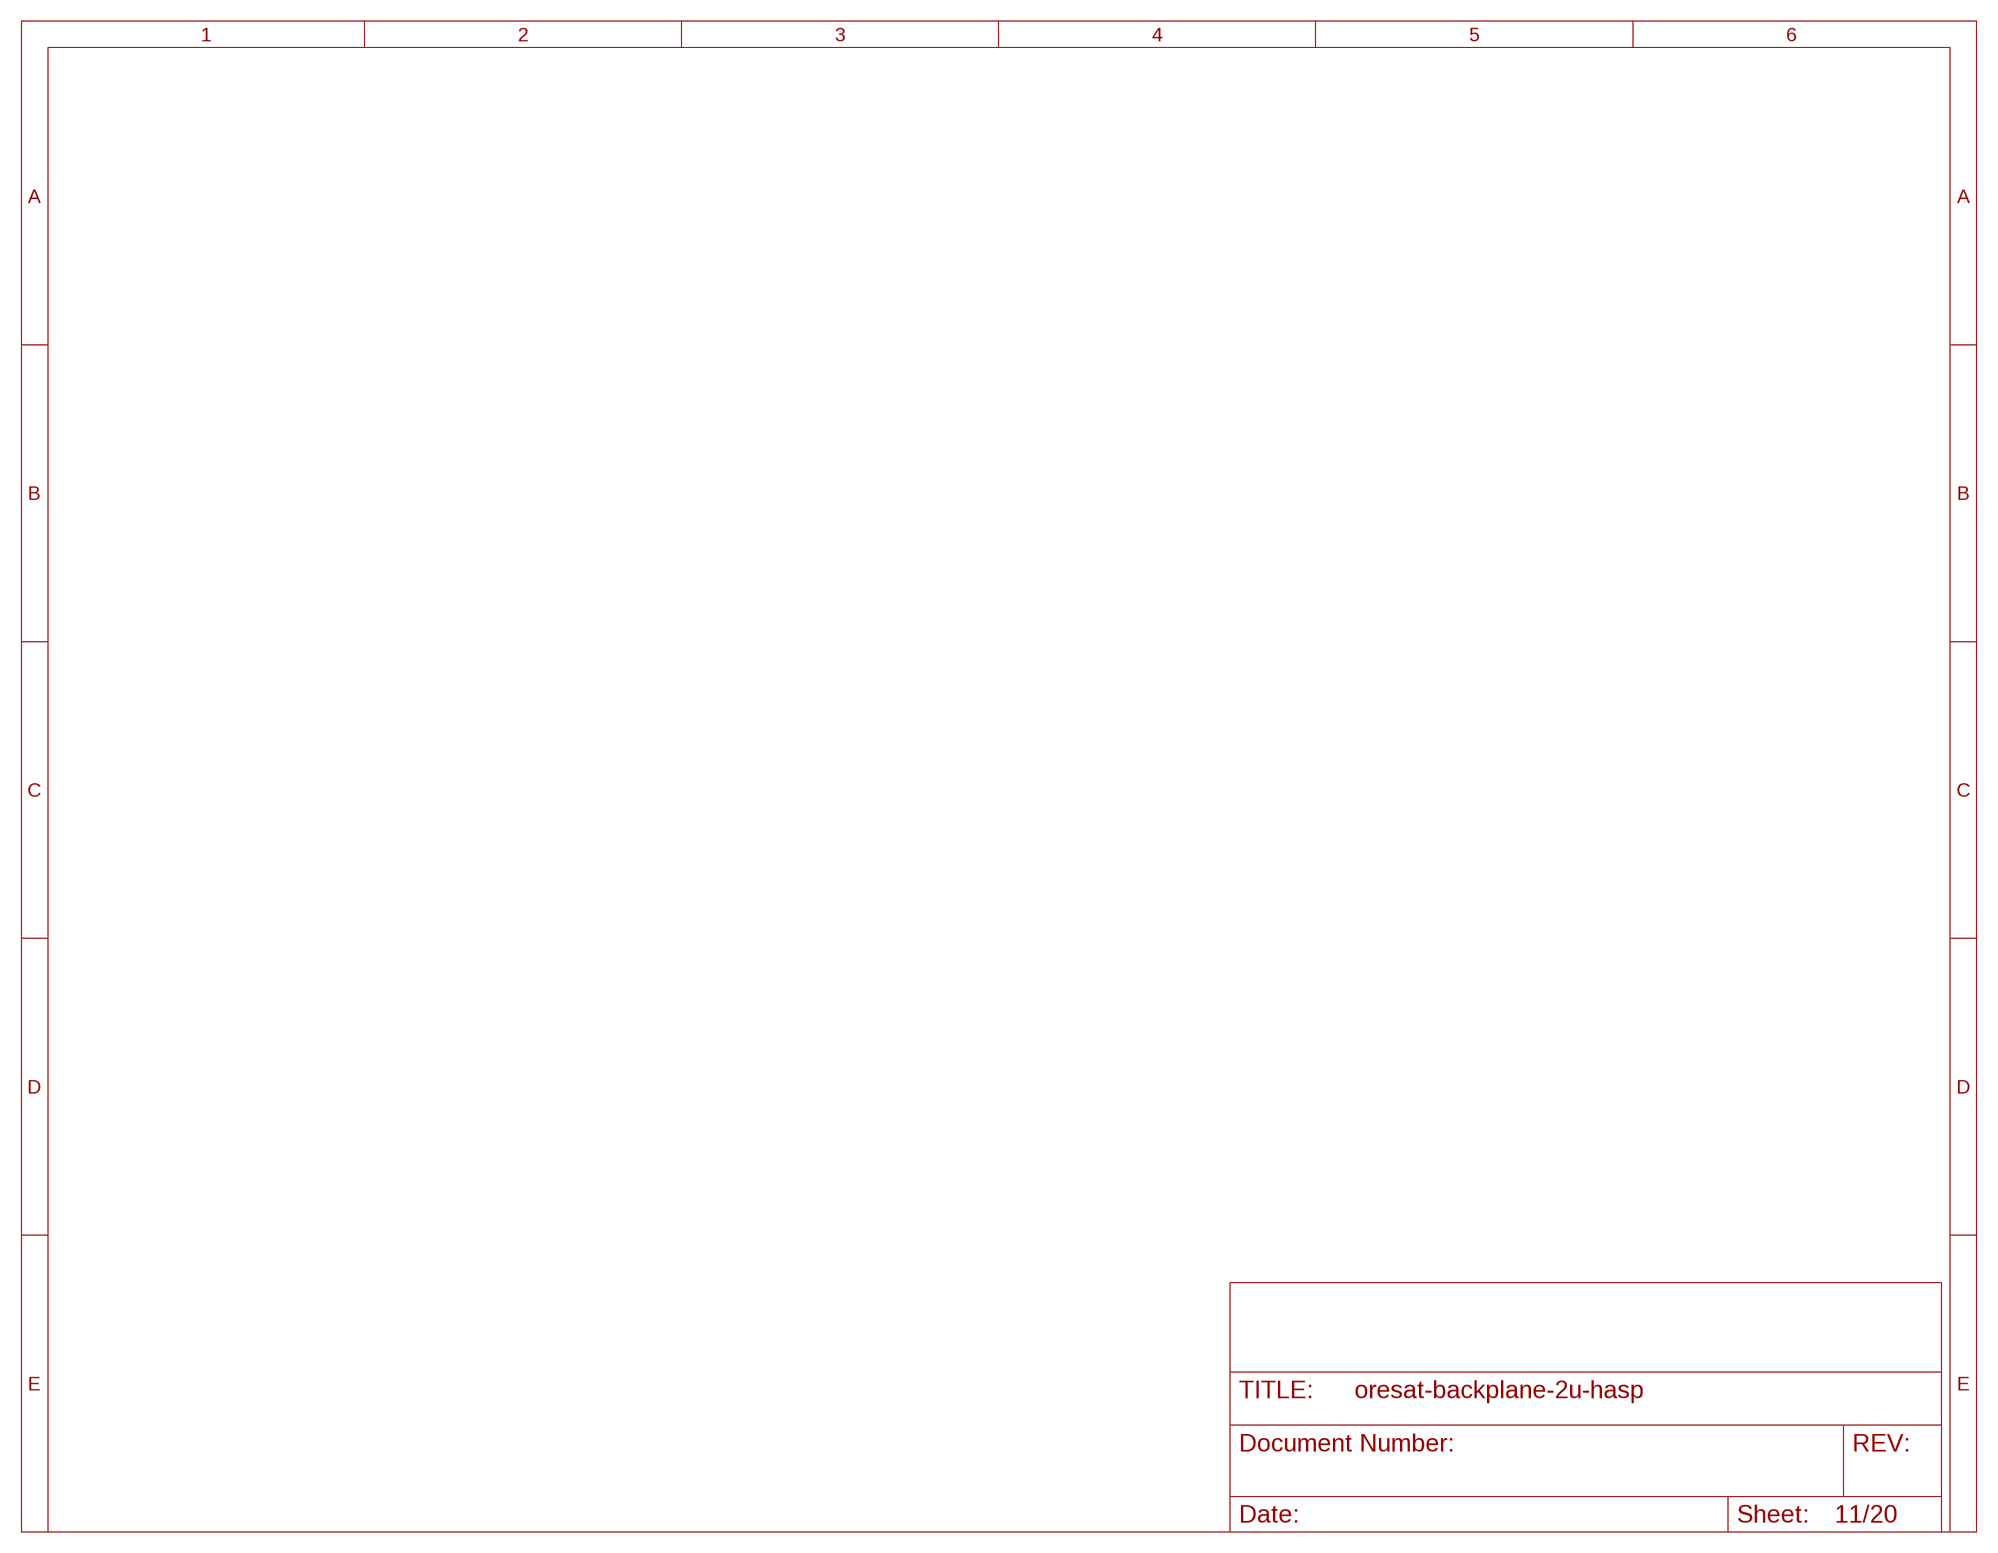
[diagram p10: schematic, sheet 11]
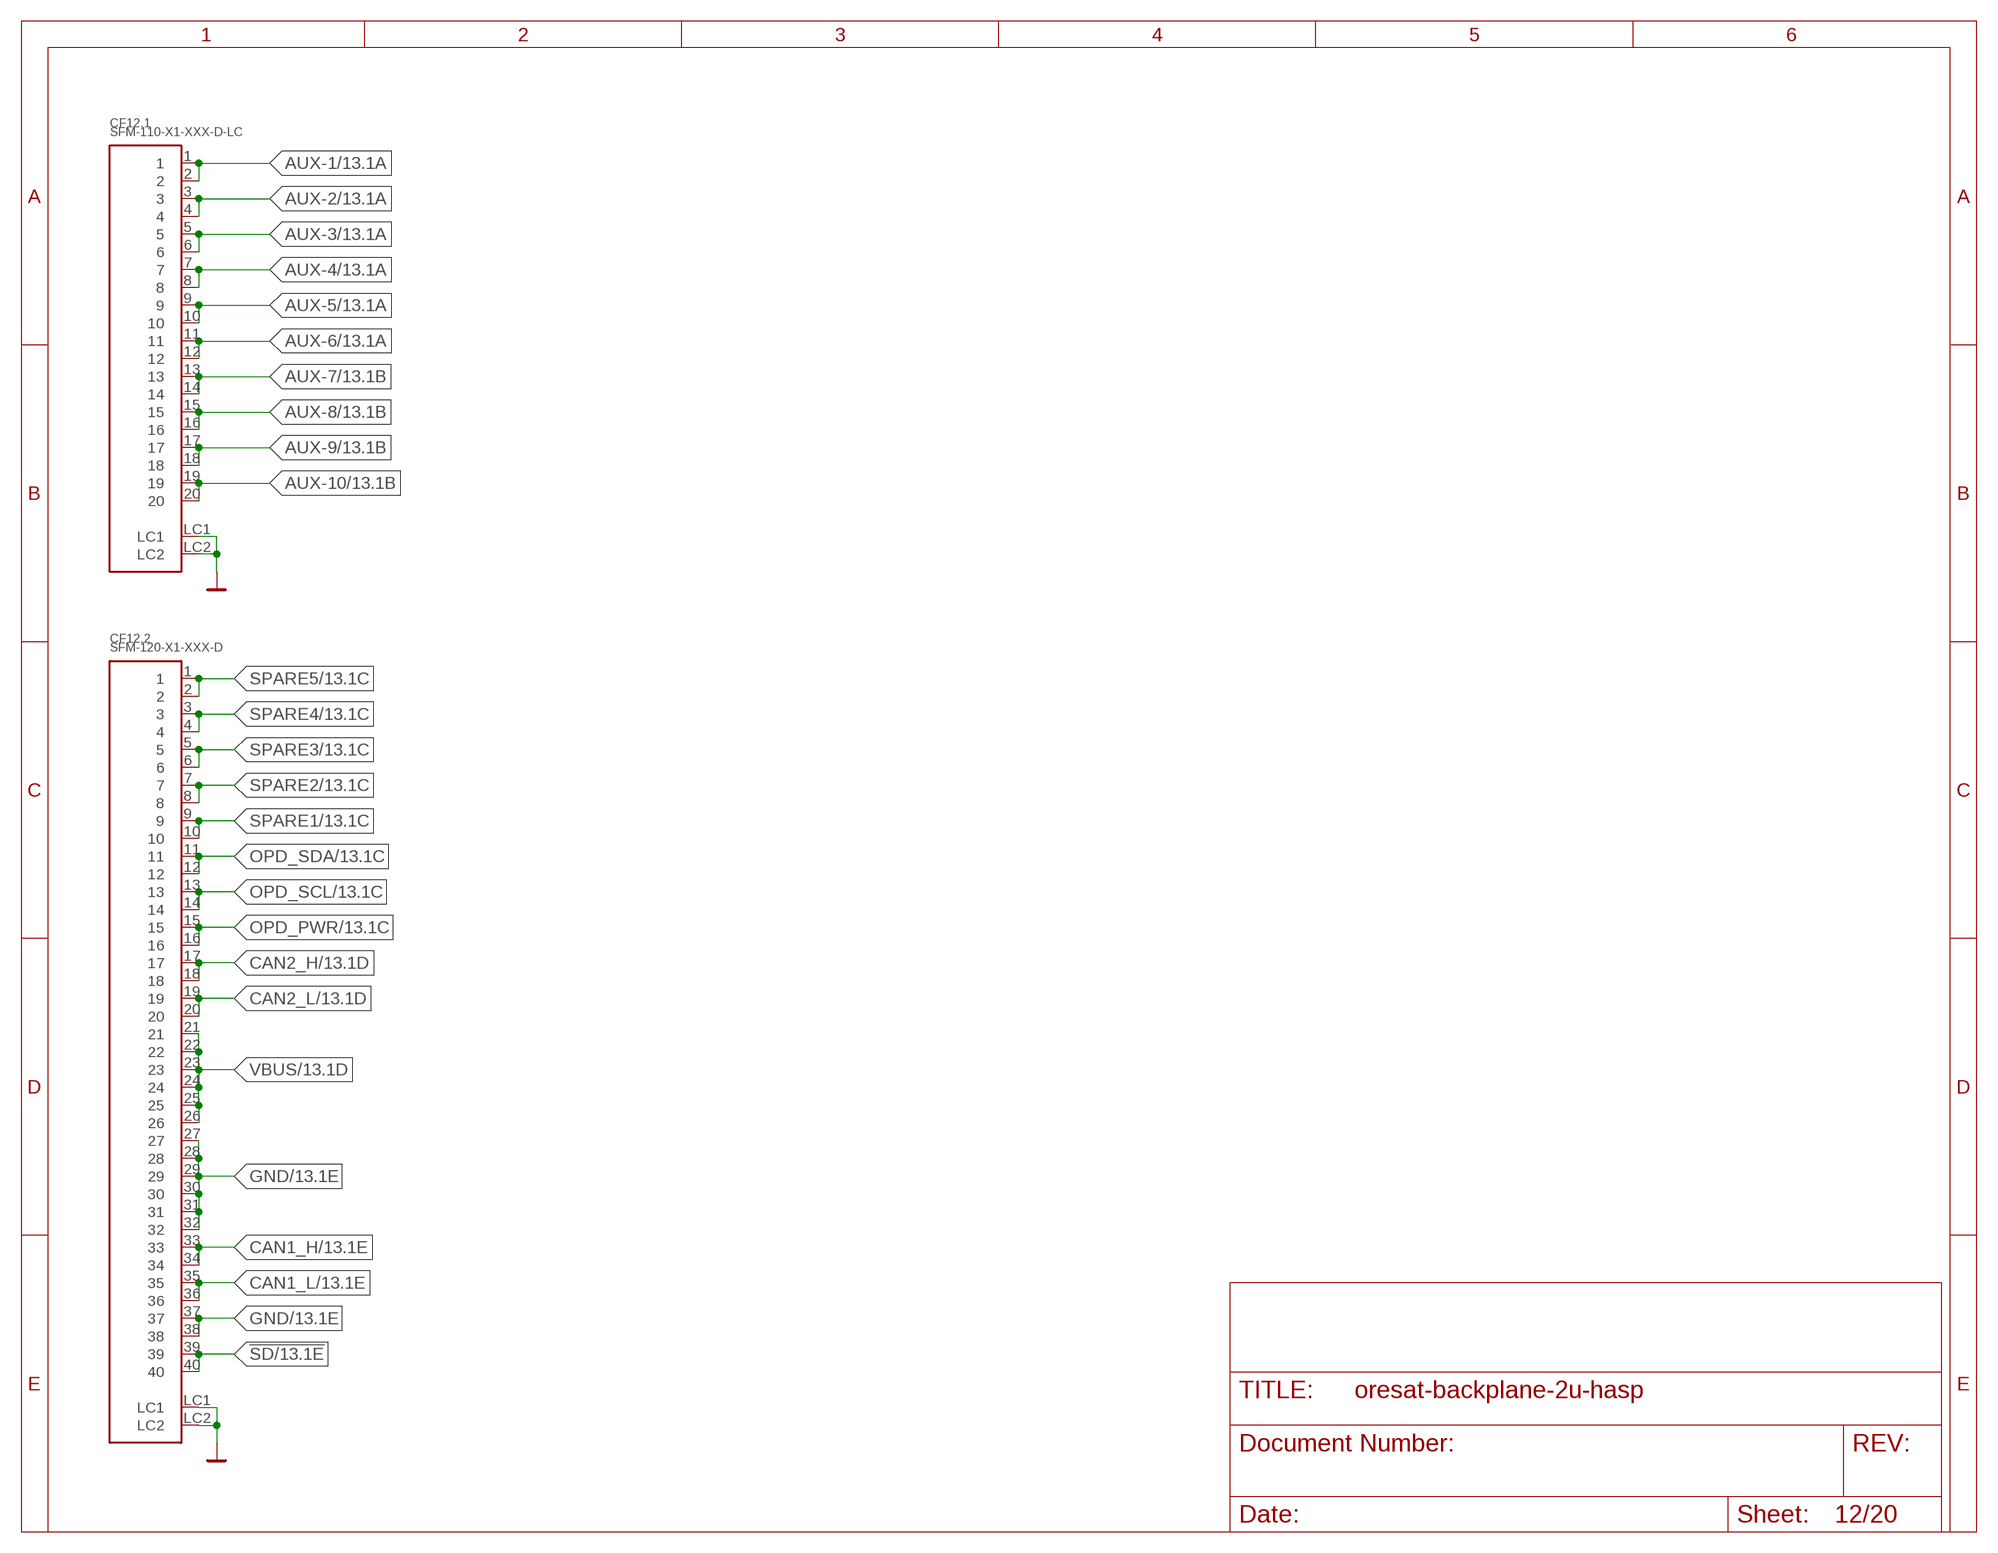
[diagram p11: schematic, sheet 12]
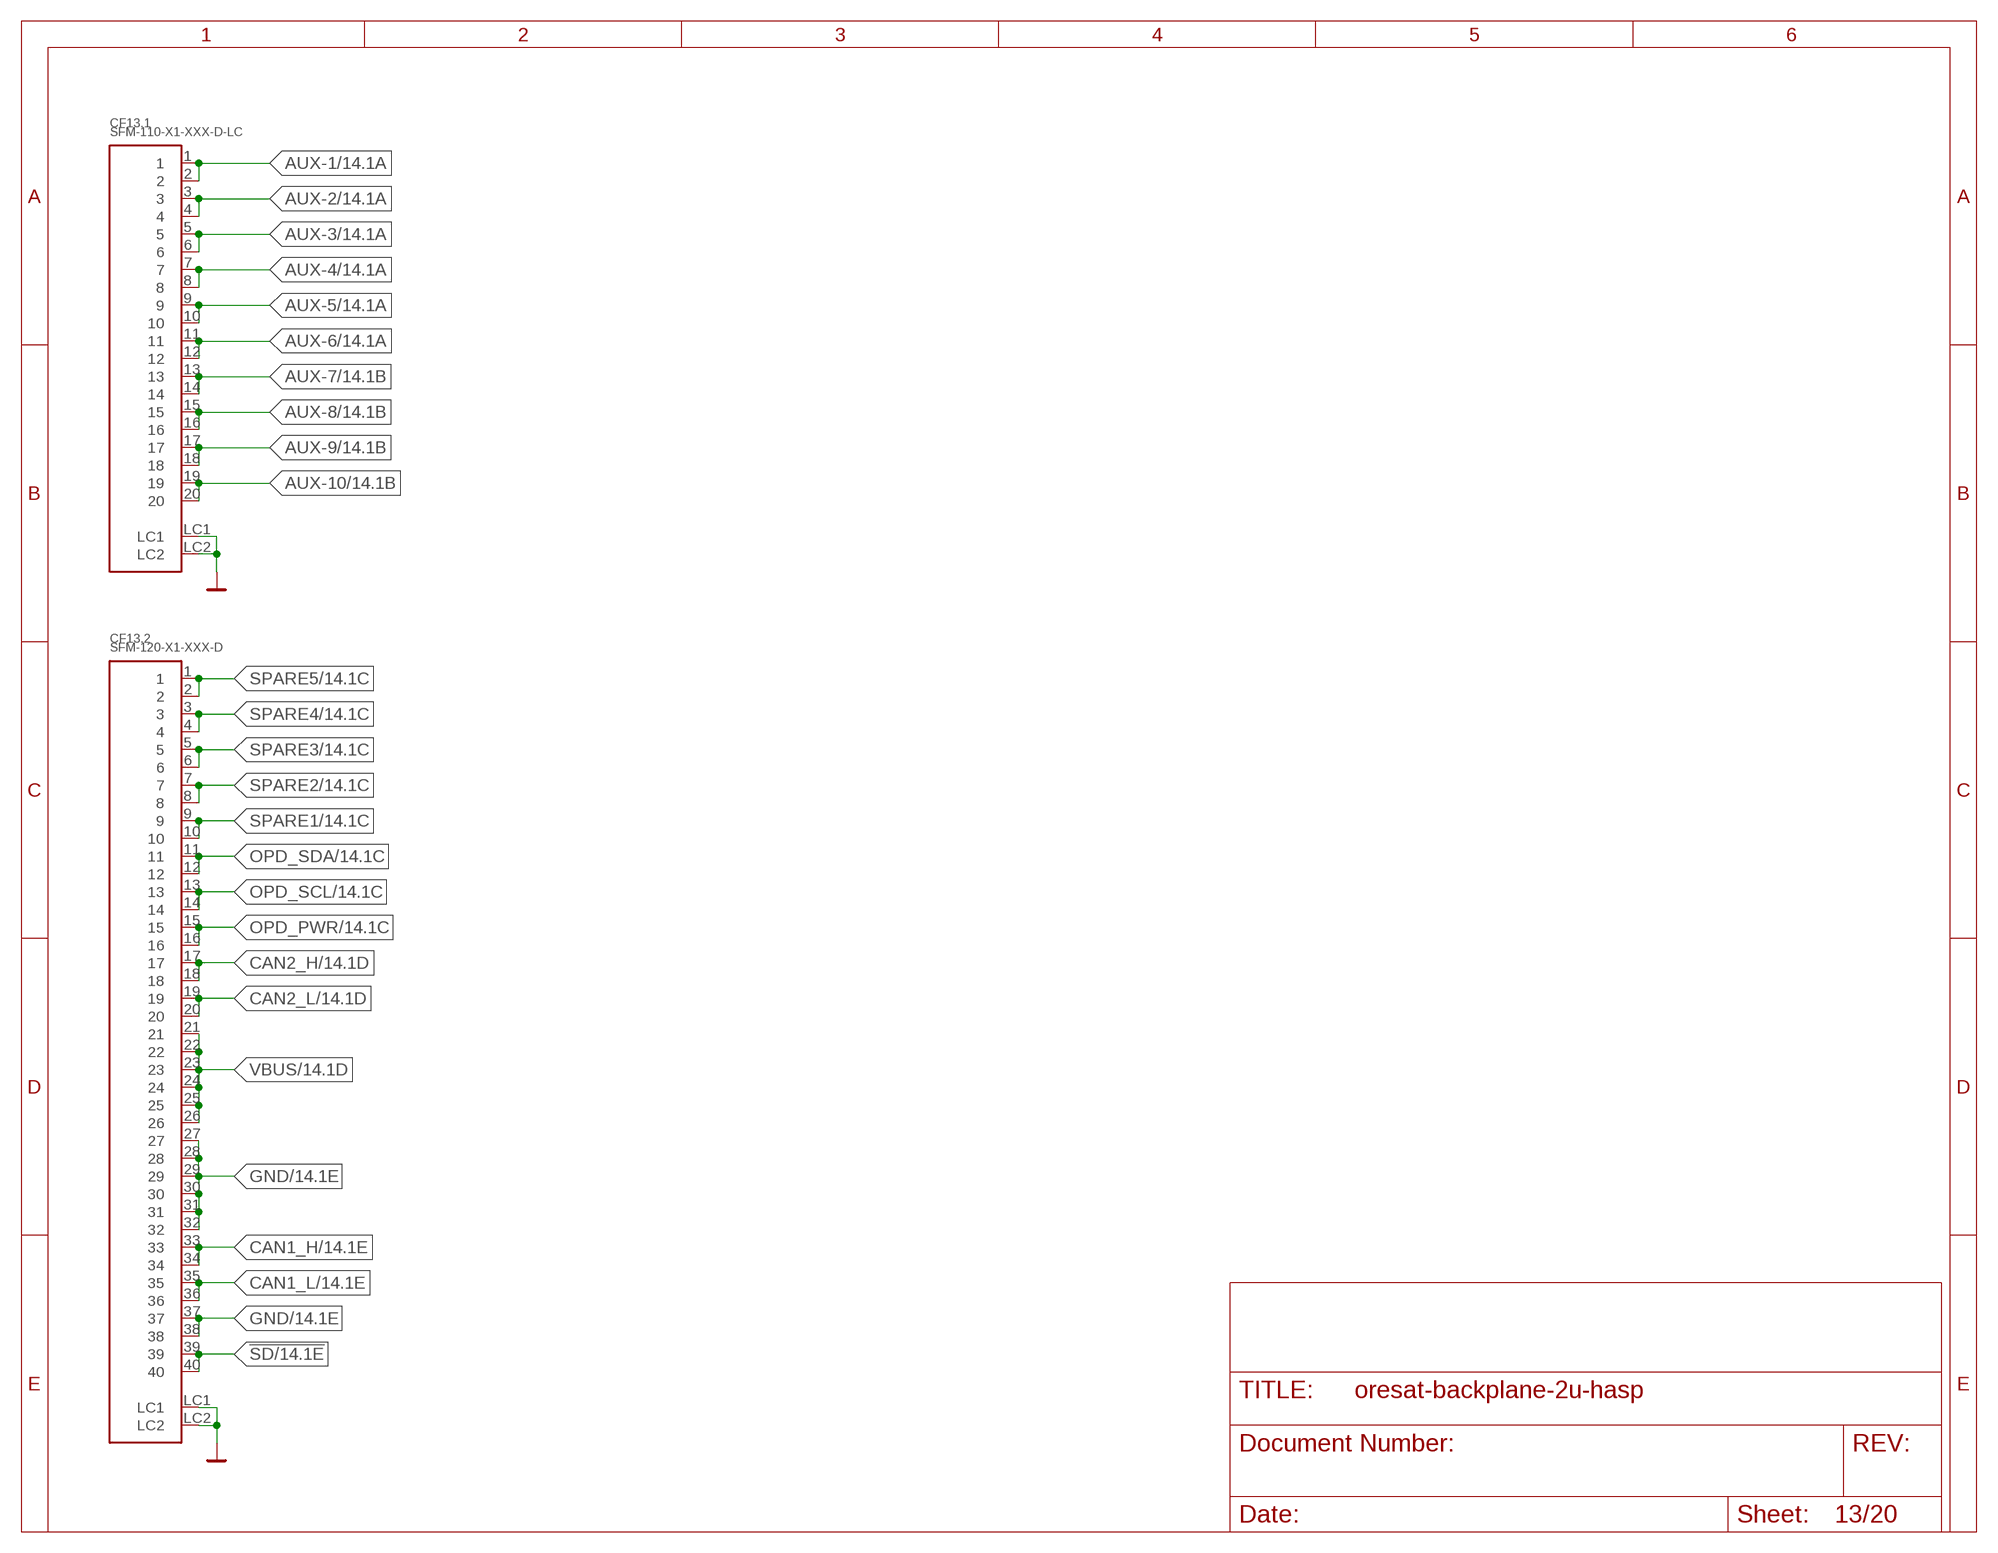
[diagram p12: schematic, sheet 13]
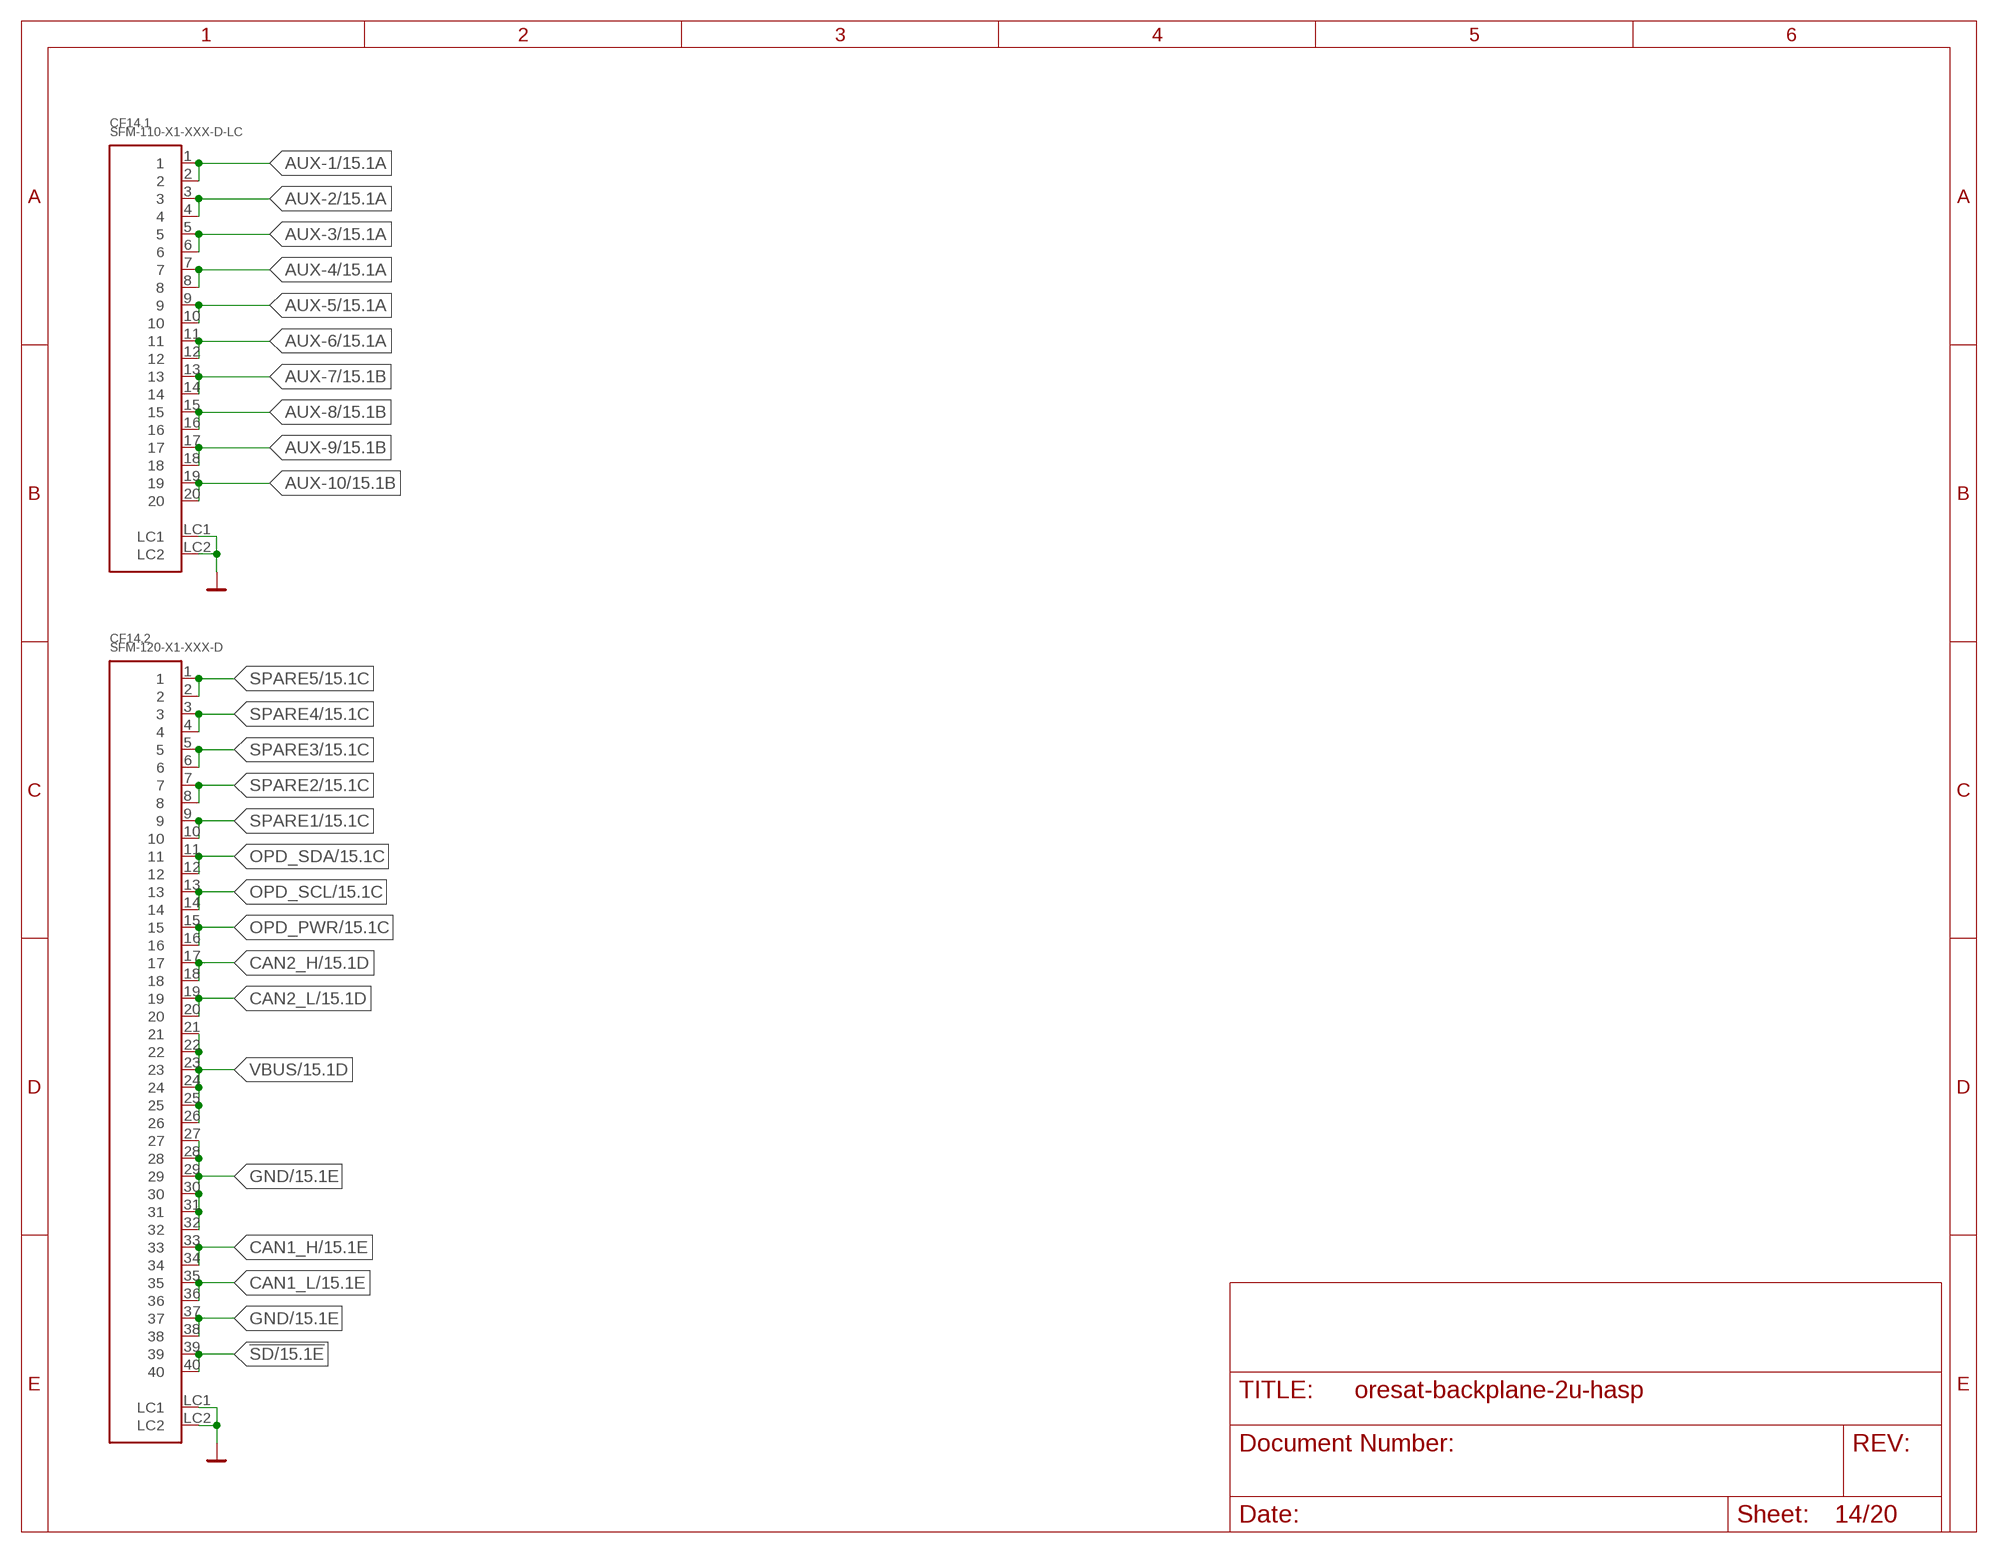
[diagram p13: schematic, sheet 14]
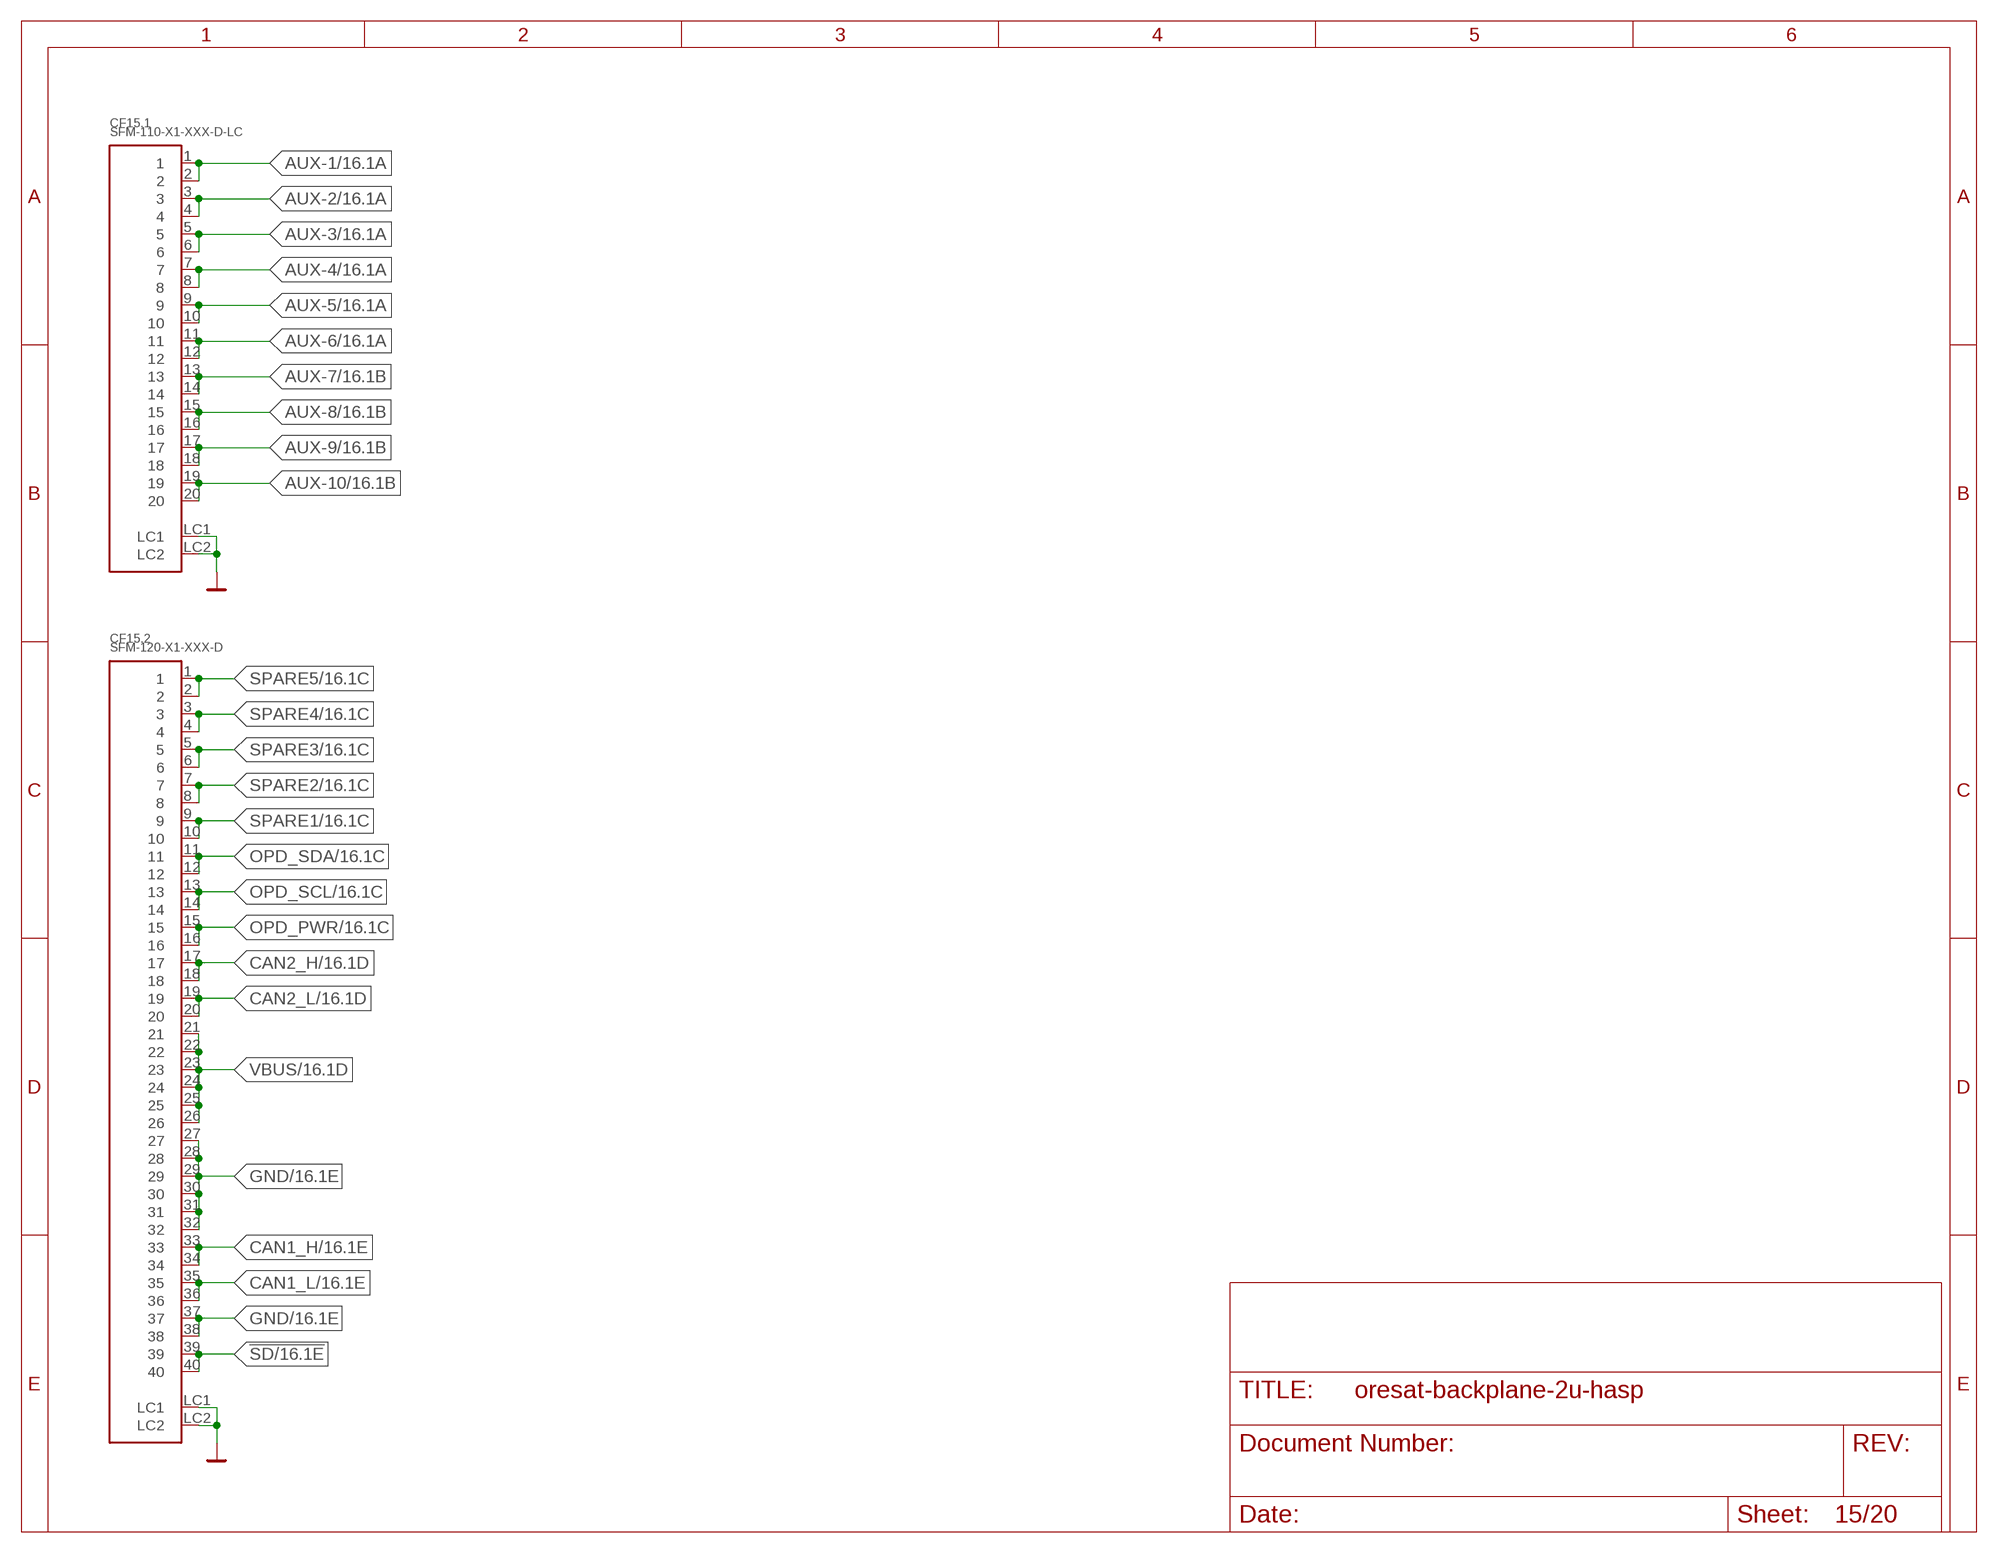
[diagram p14: schematic, sheet 15]
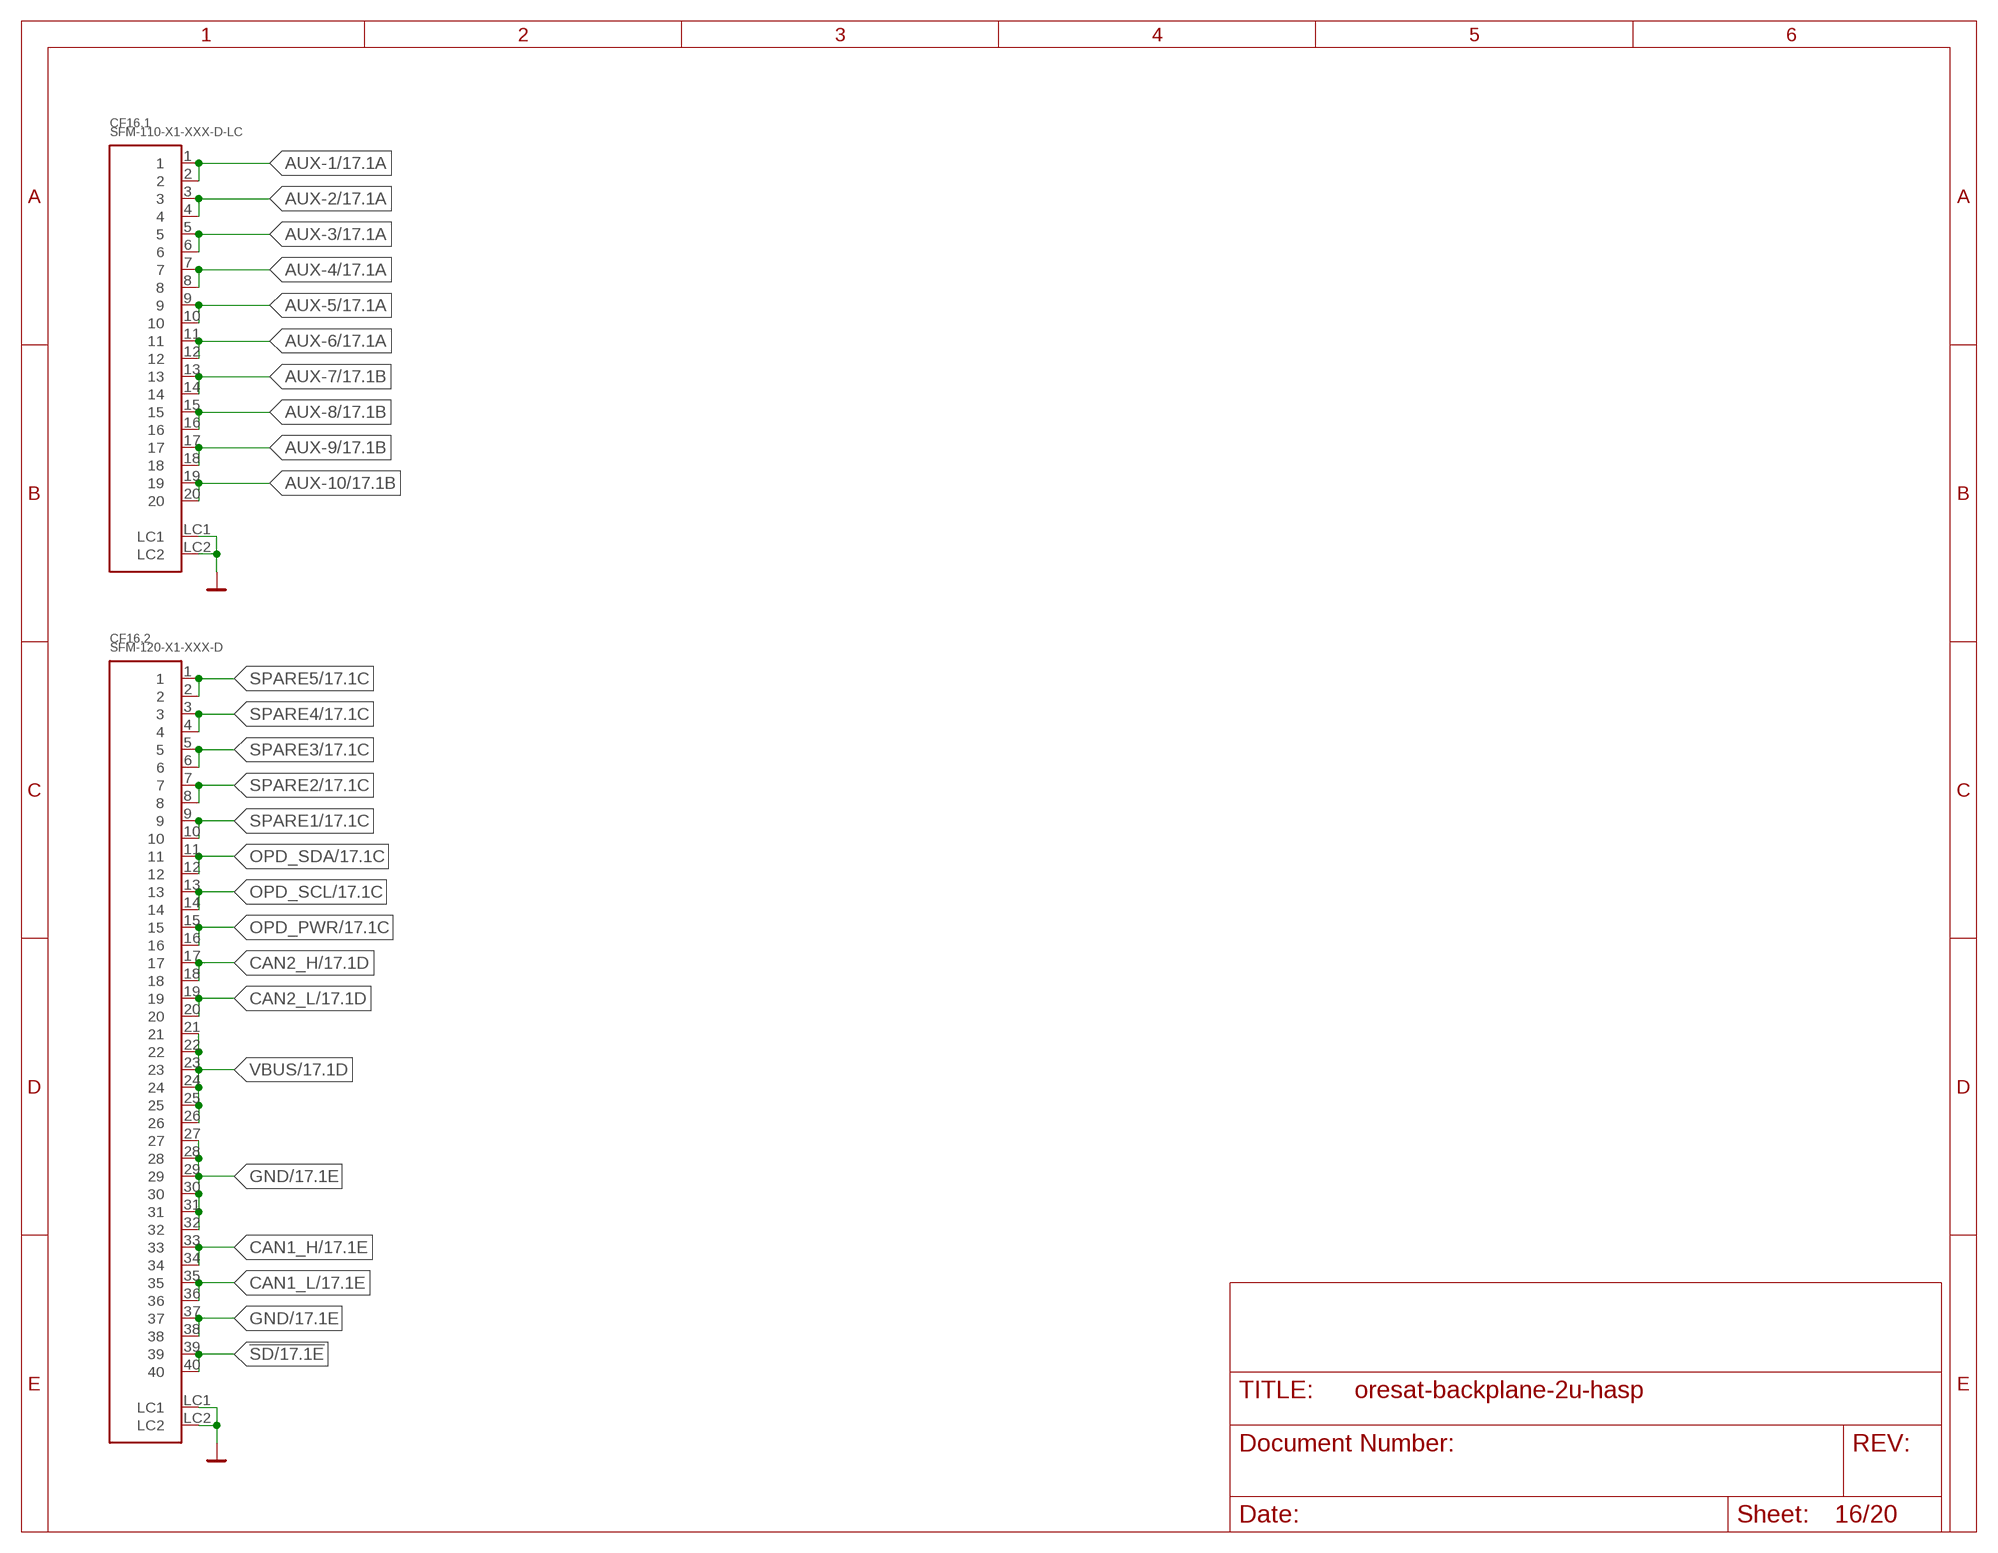
[diagram p15: schematic, sheet 16]
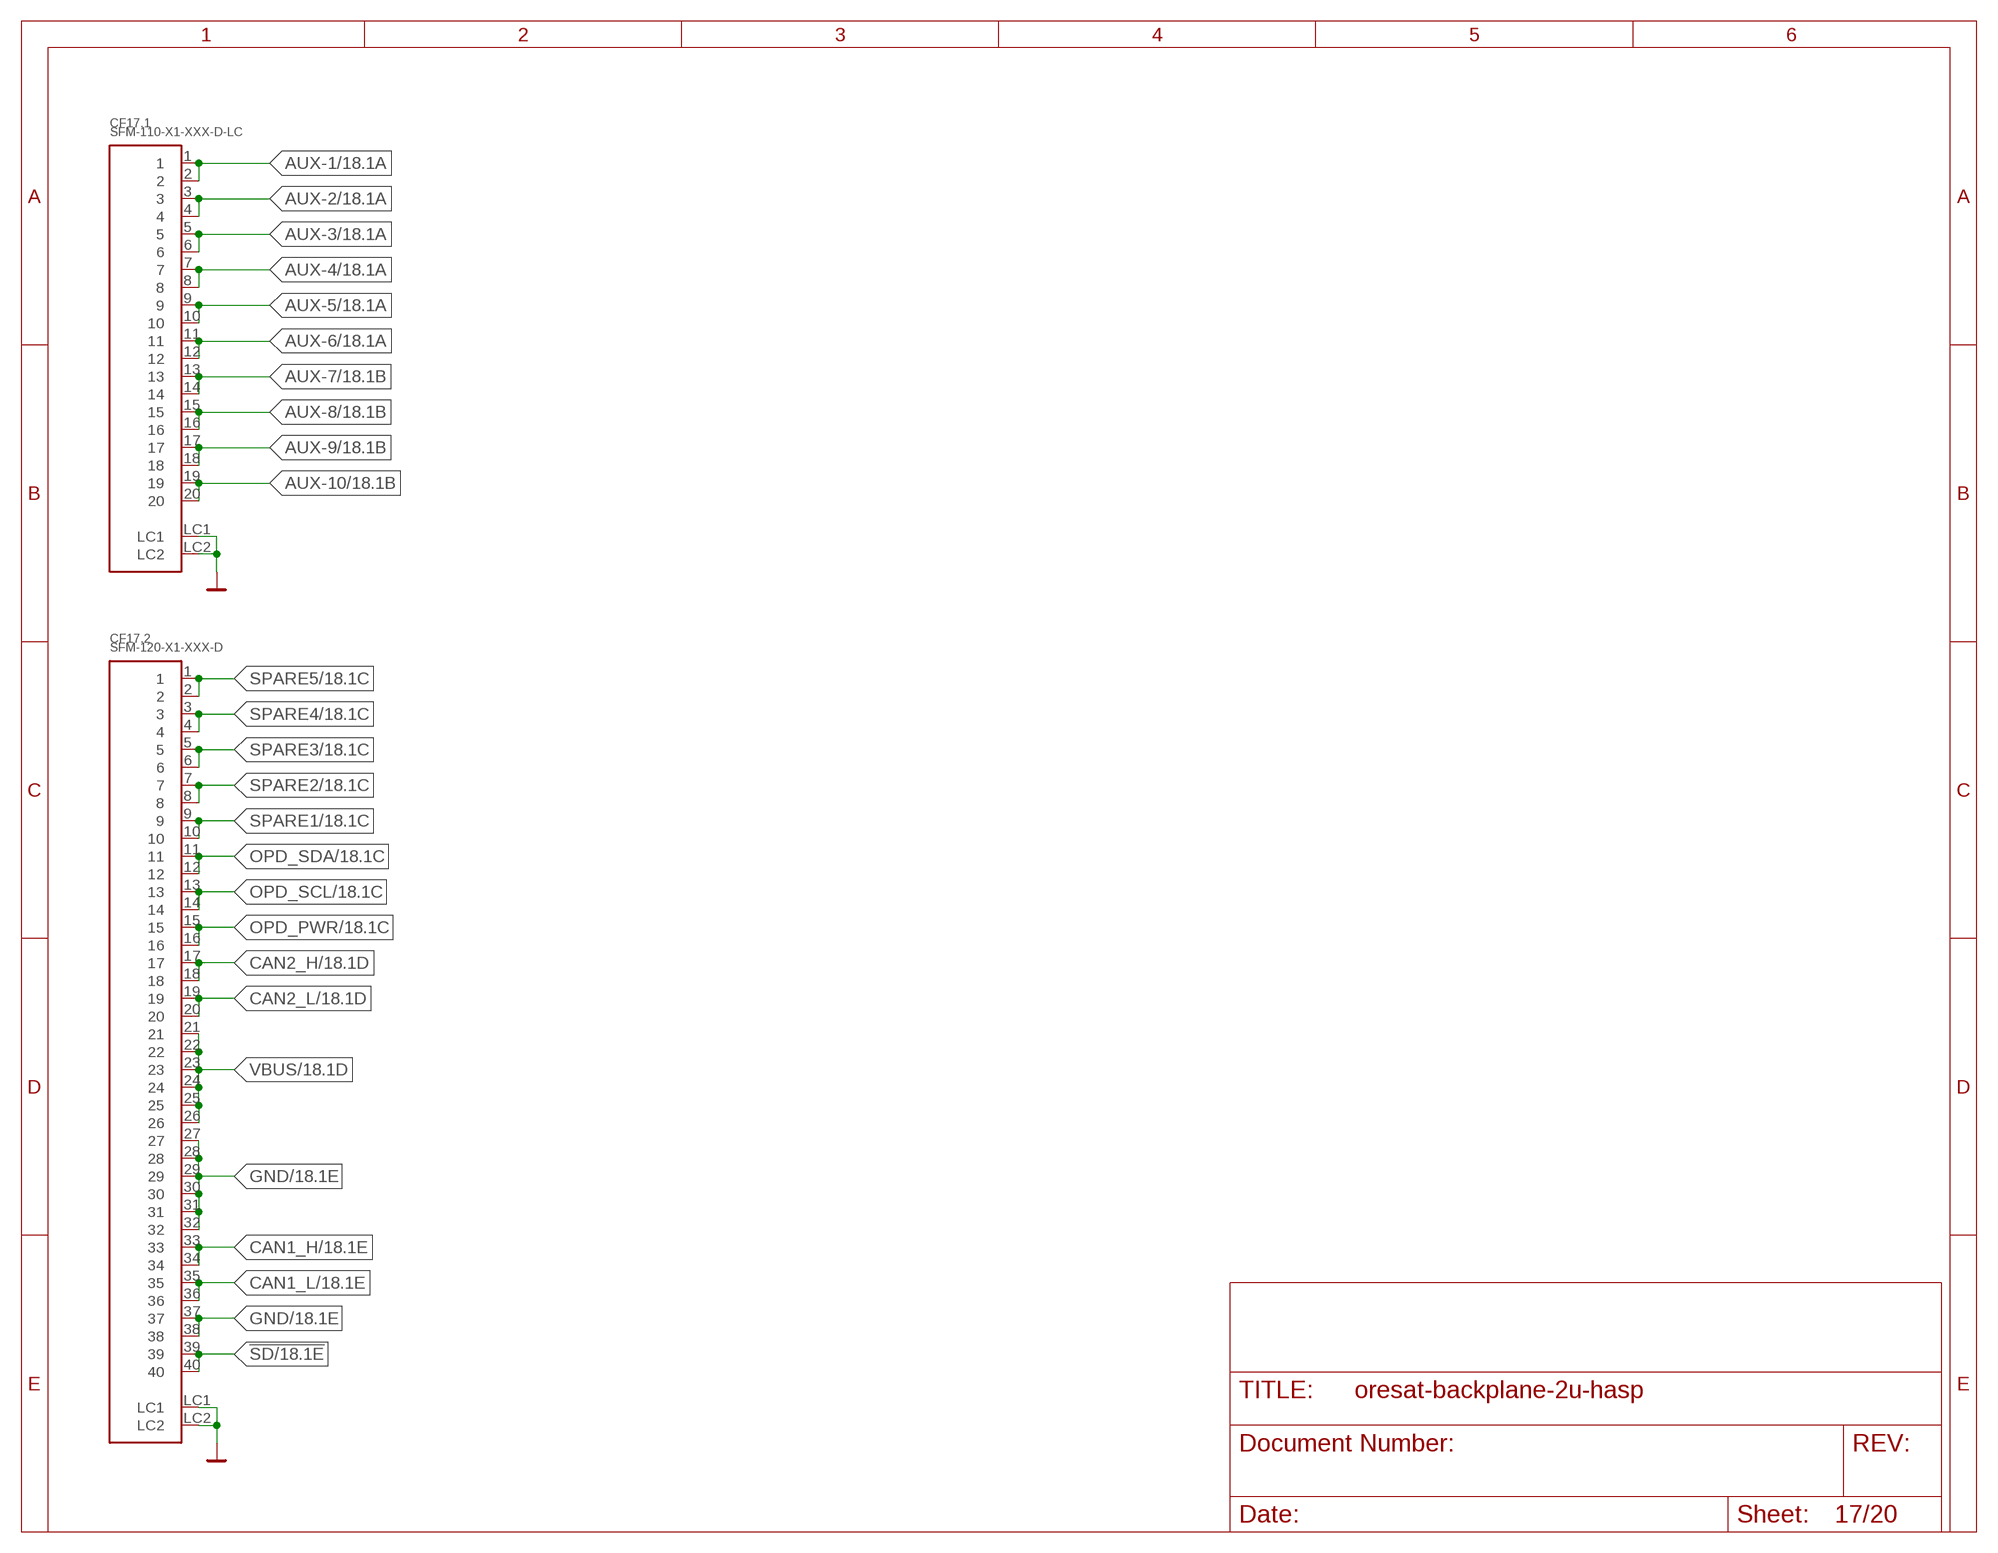
[diagram p16: schematic, sheet 17]
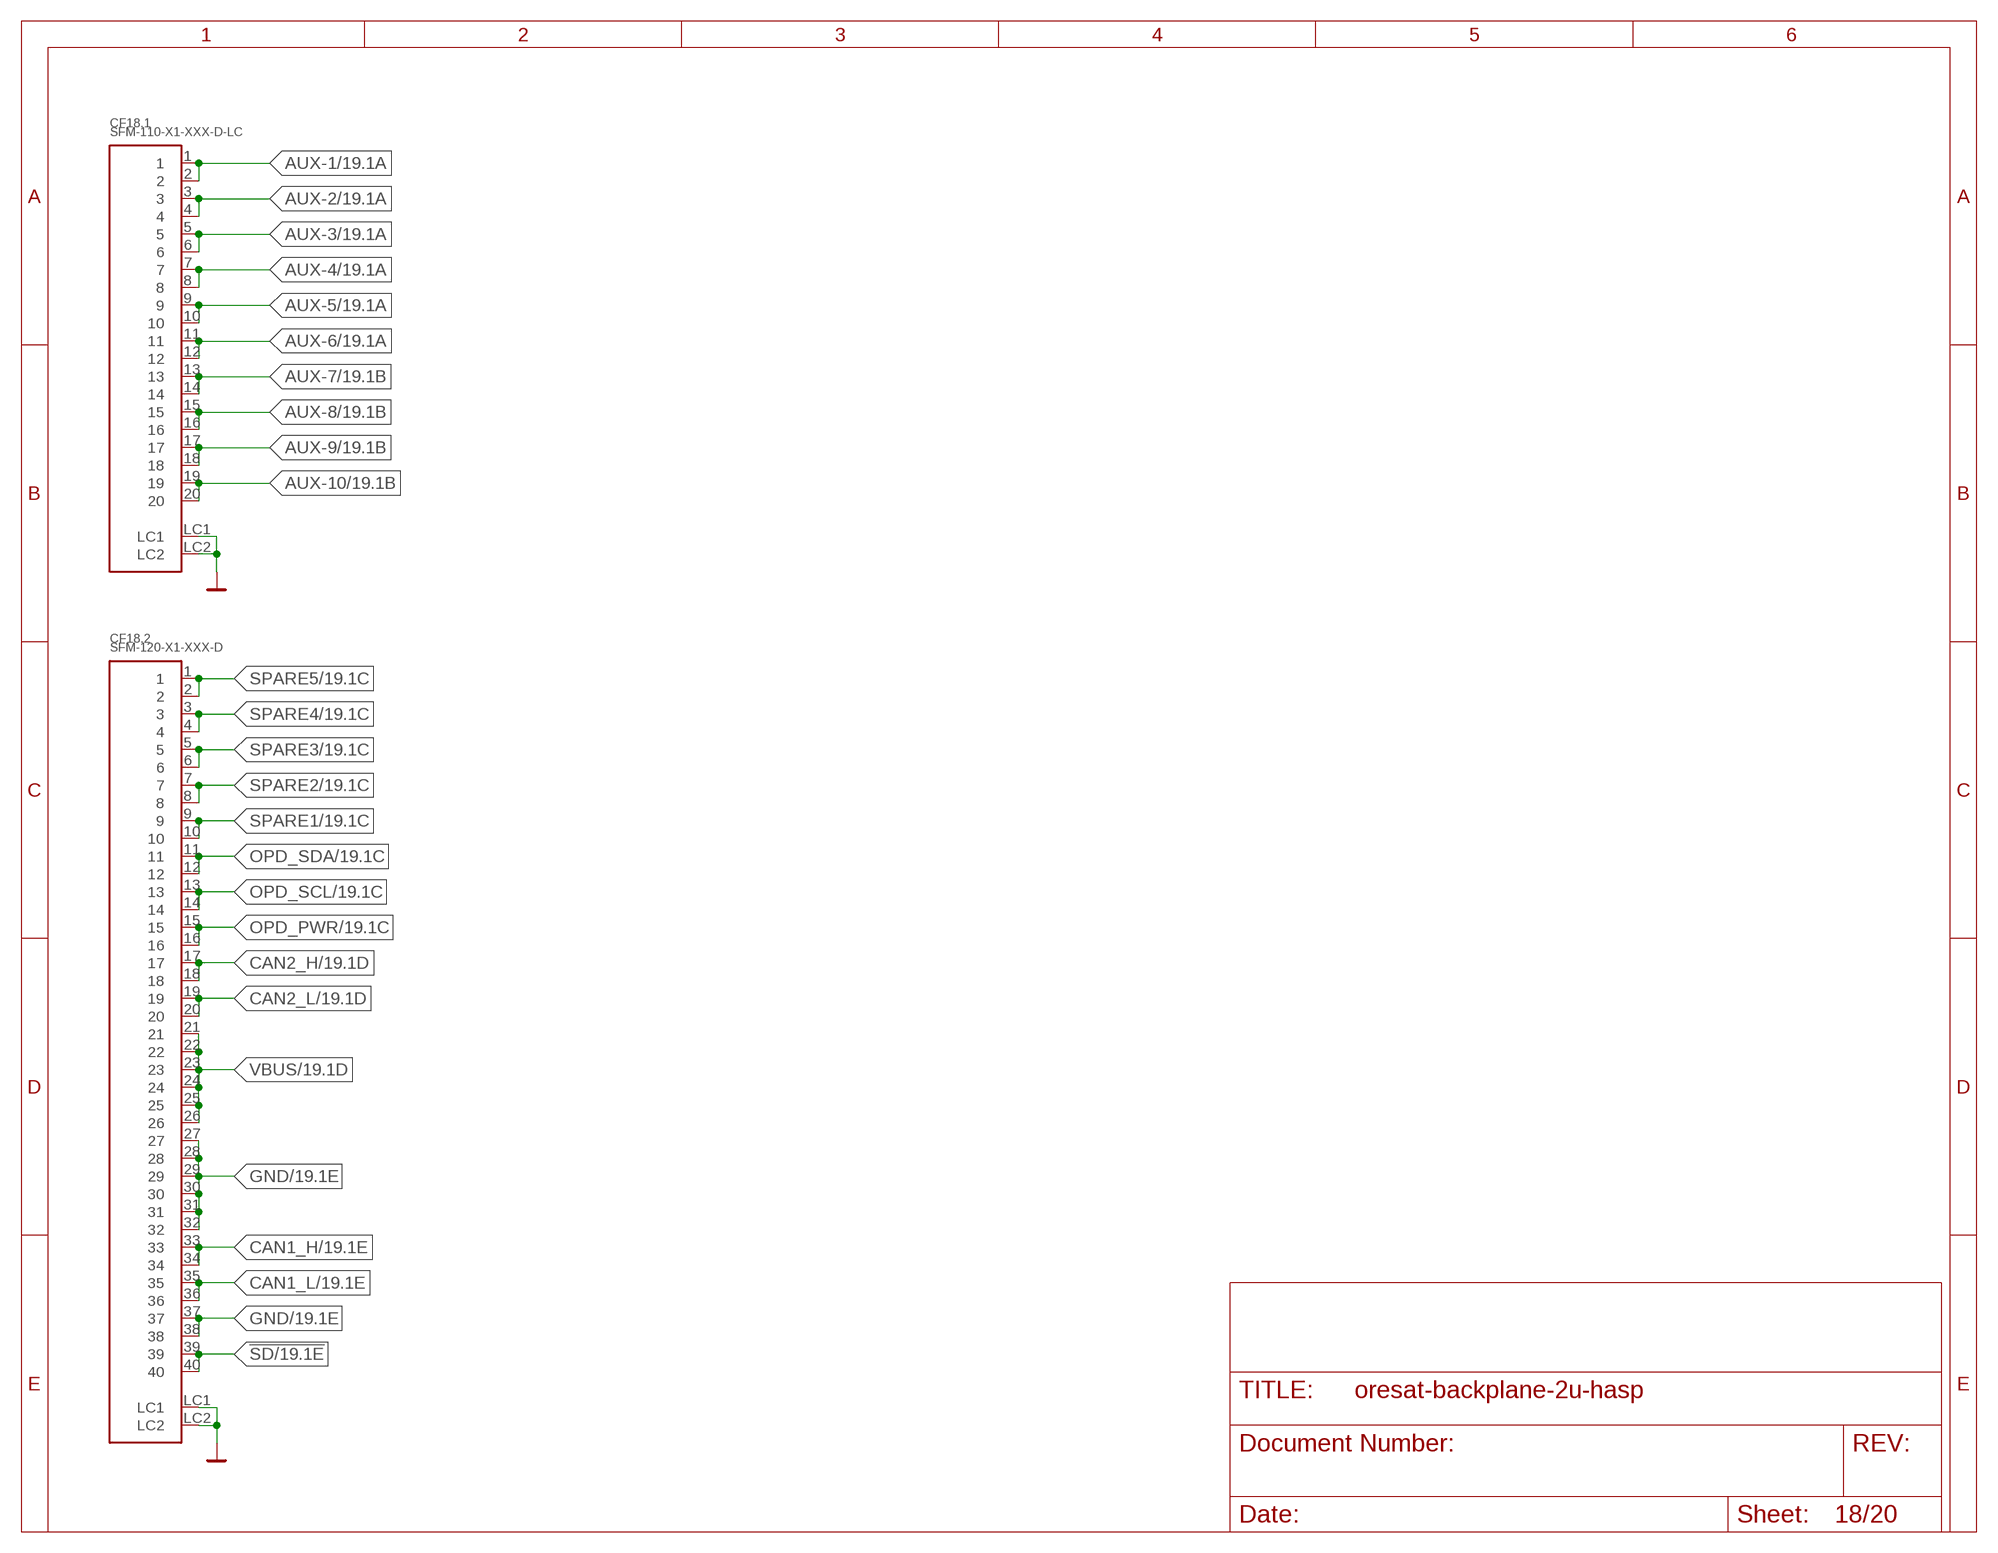
[diagram p17: schematic, sheet 18]
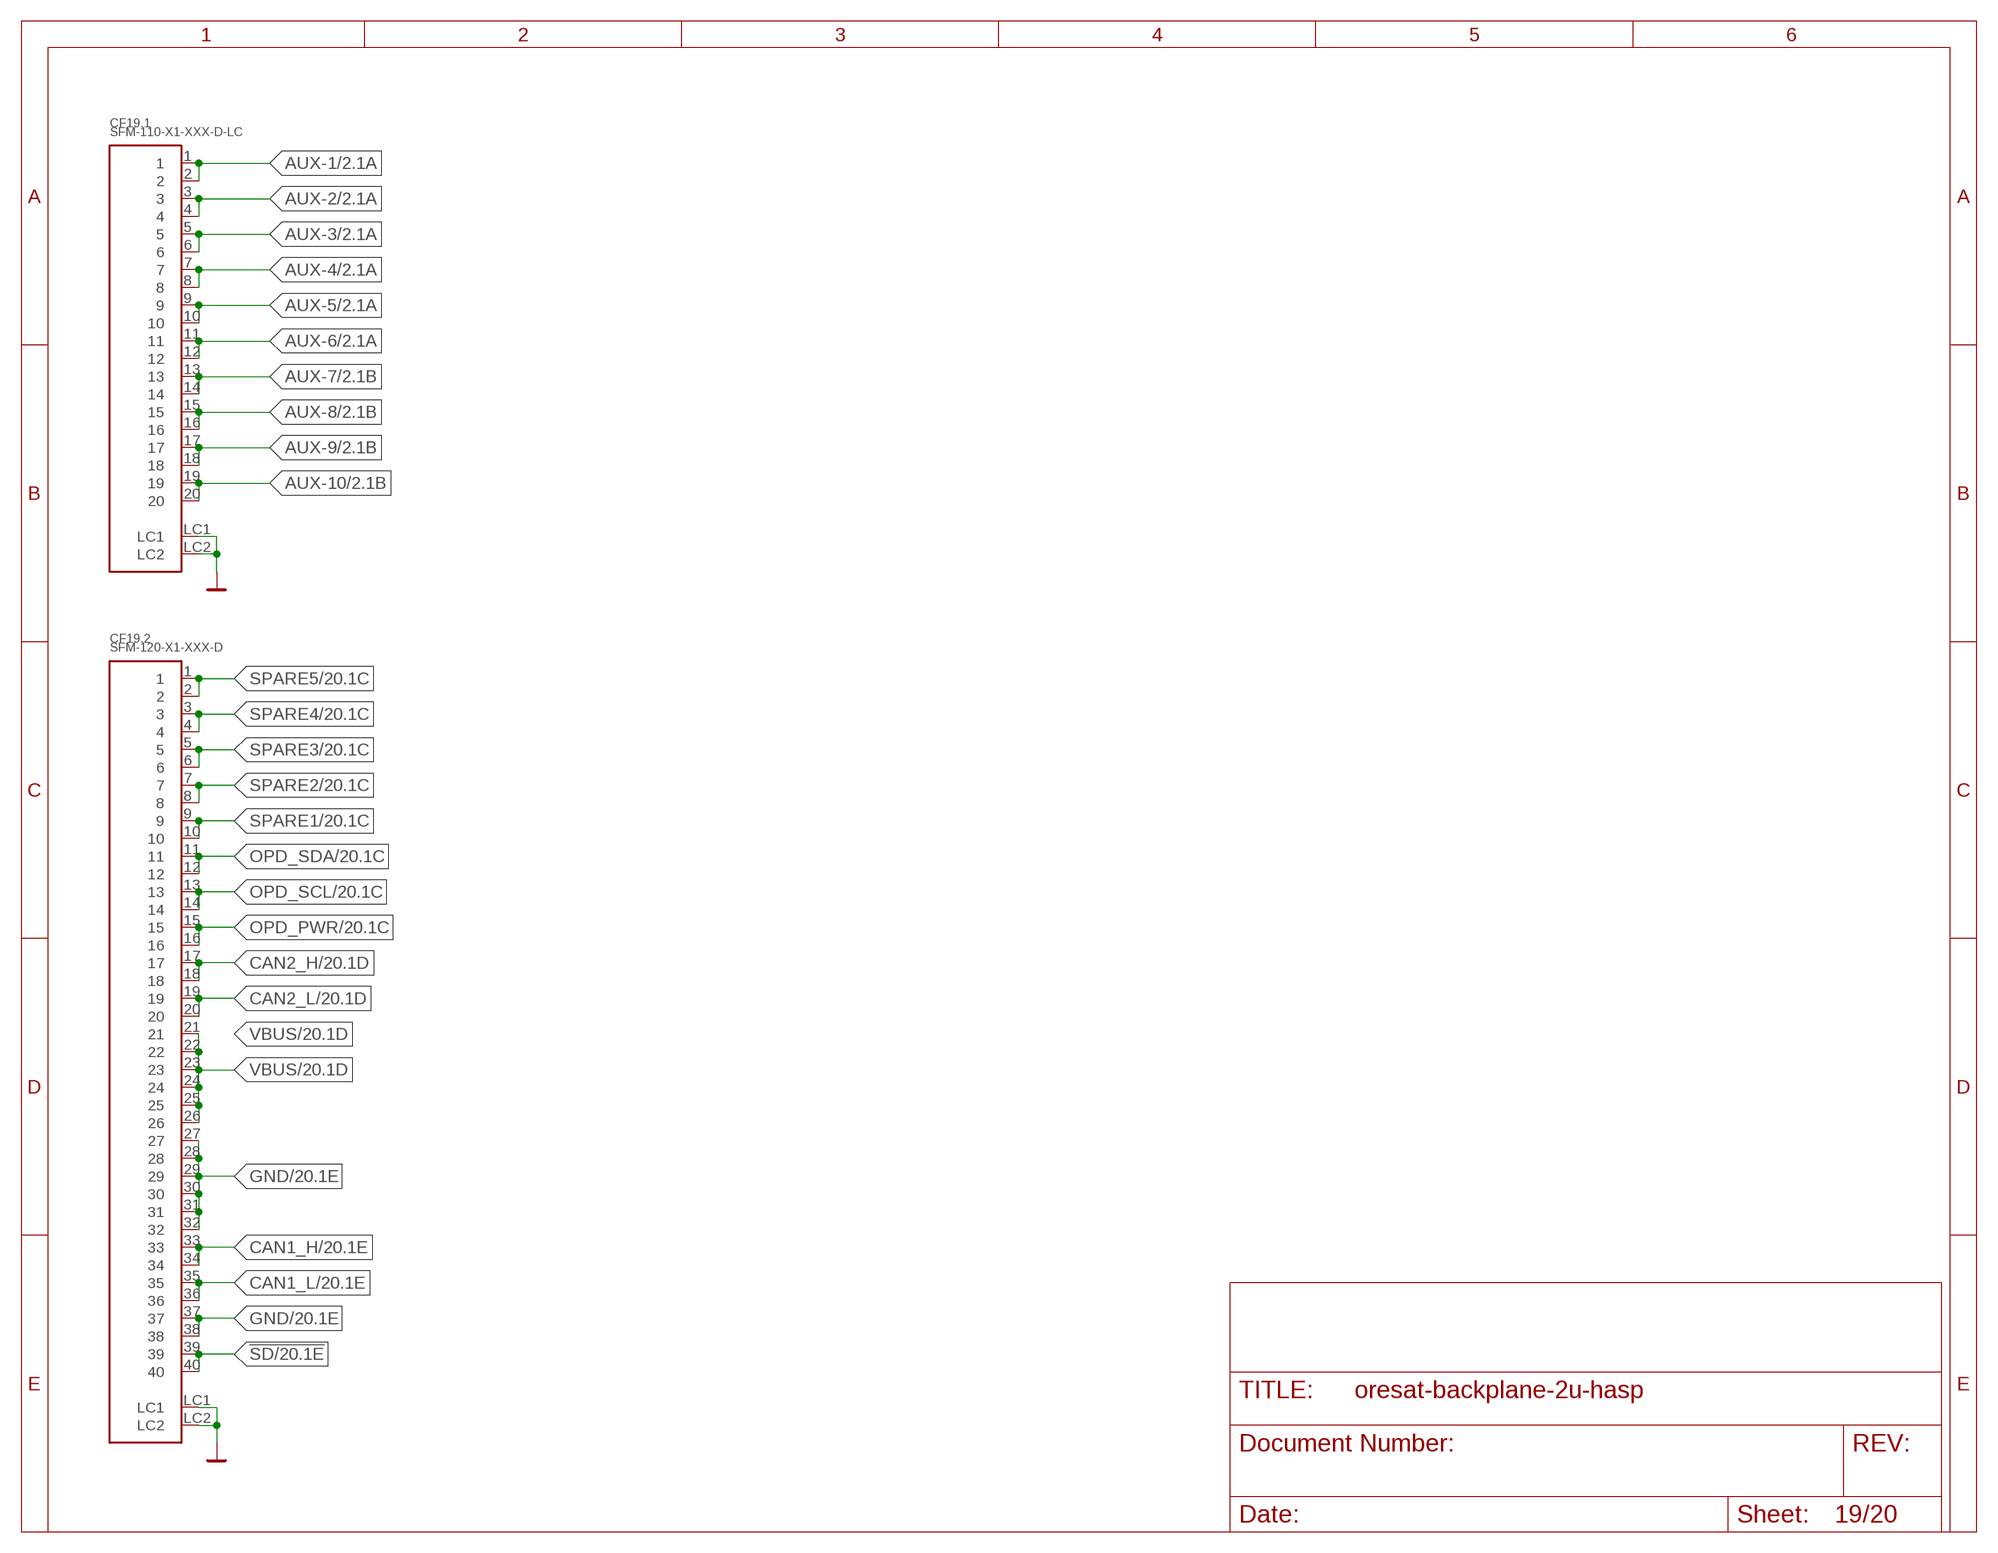
[diagram p18: schematic, sheet 19]
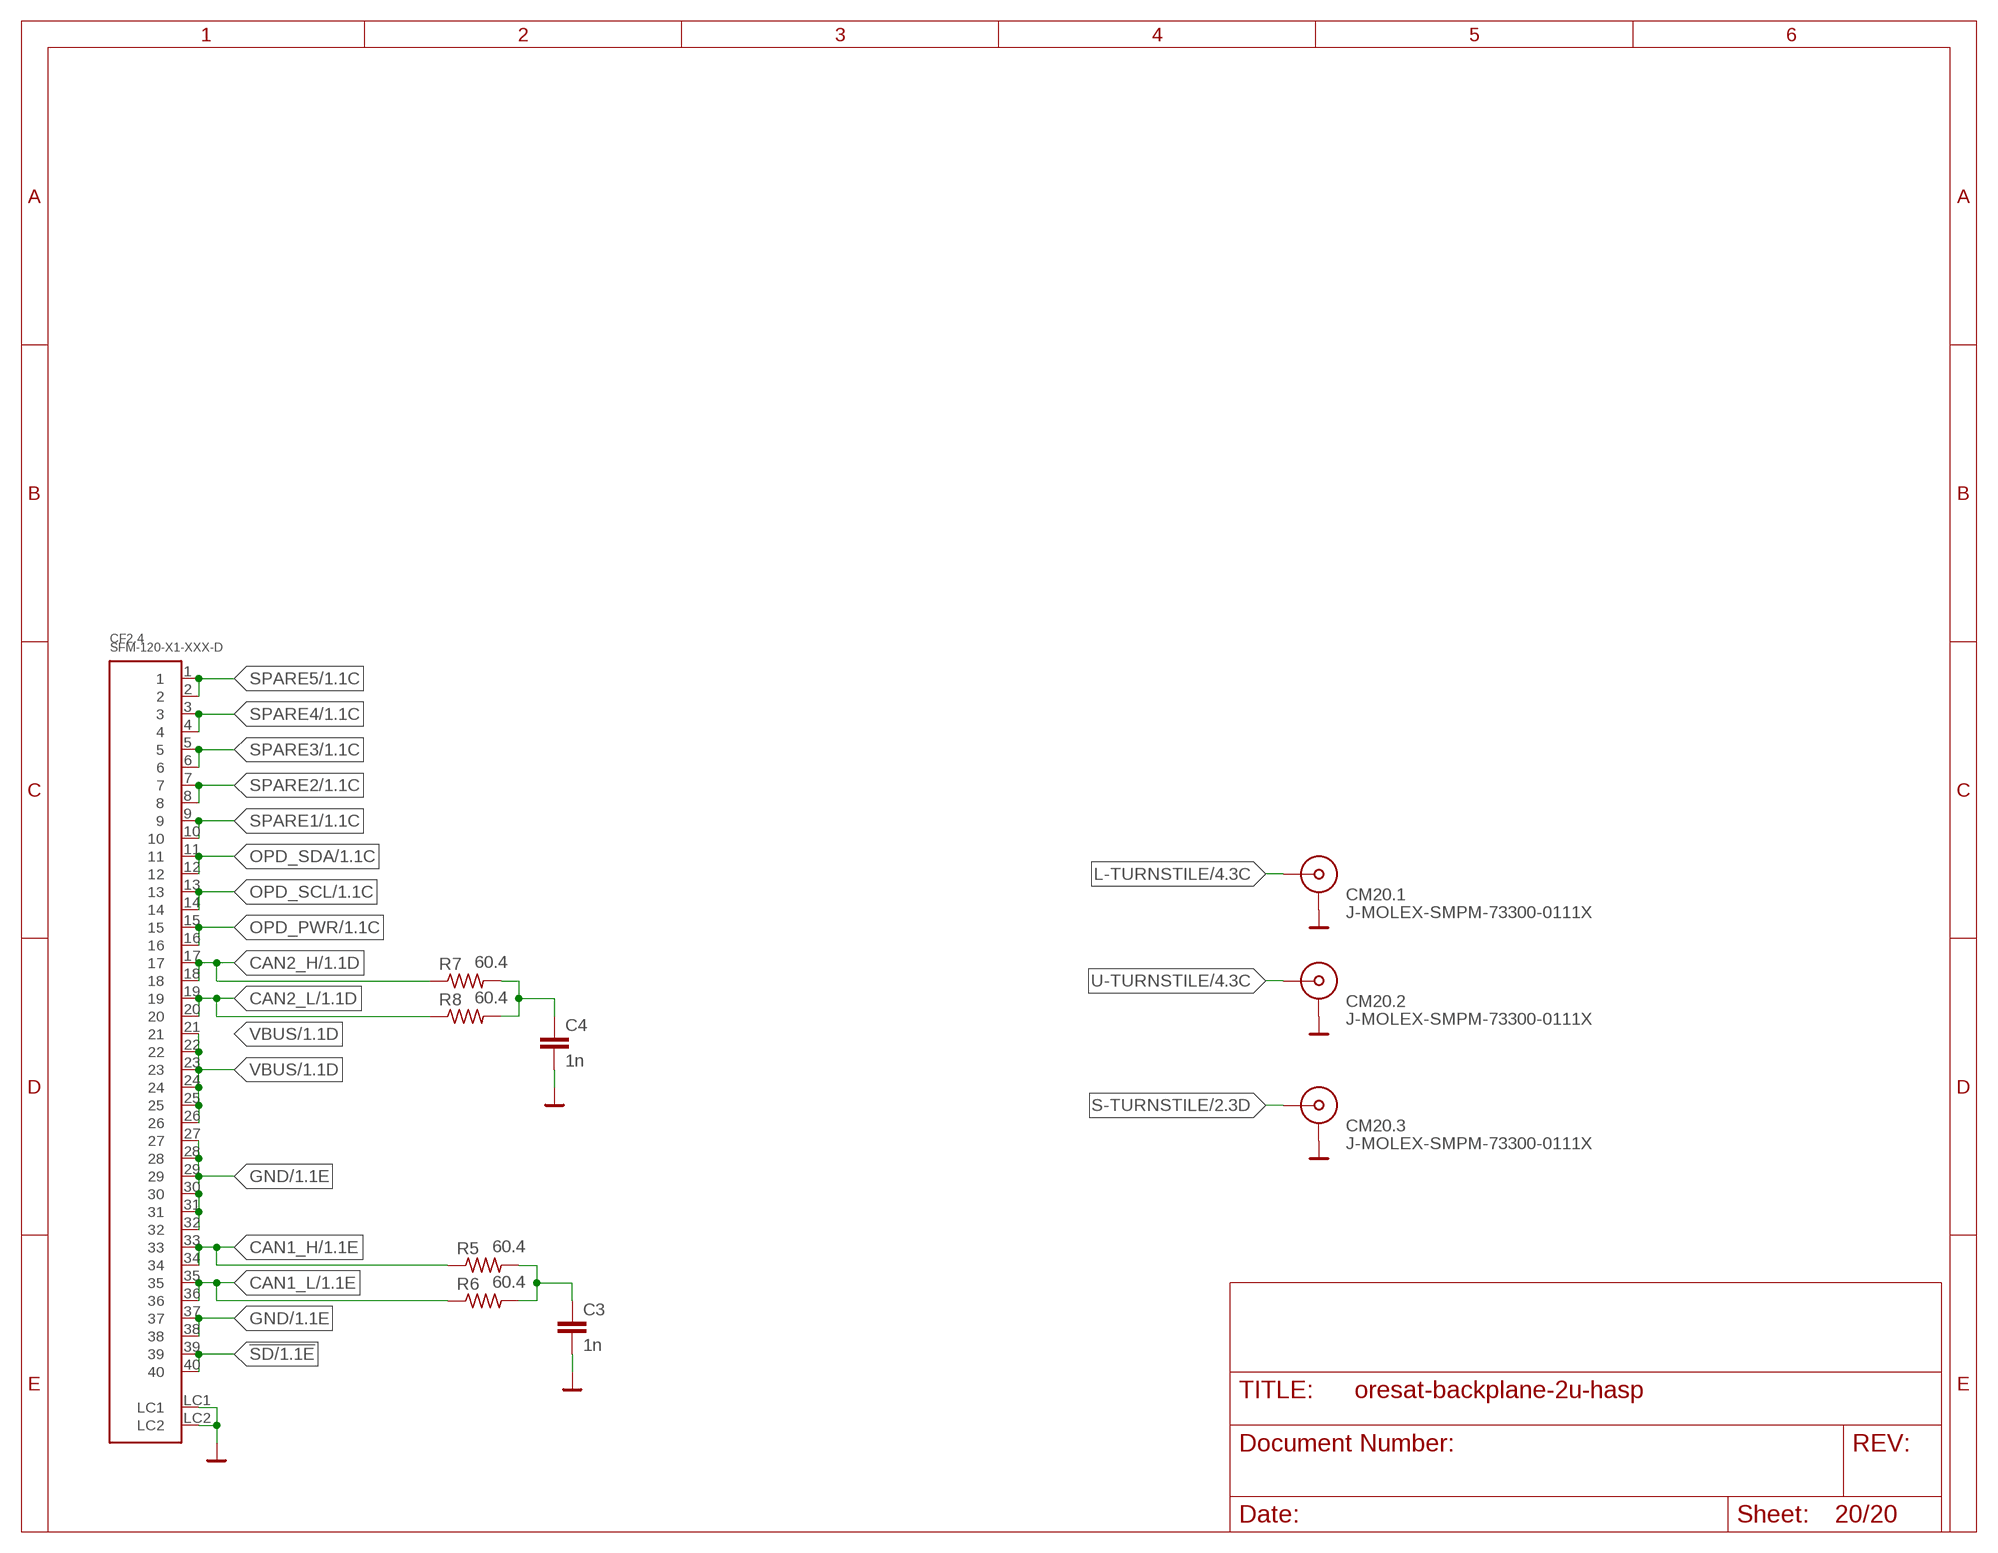
[diagram p19: schematic, sheet 20]

(export (version "E")
  (design (tool "Eeschema 10.0.6"))
  (components
    (comp (ref "CF7.1")
      (value "SFM-110-X1-XXX-D-LC")
      (footprint "eagle-import:SFM-110-X1-XXX-D-LC")
      (libsource (lib "eagle-import") (part "SFM-110-X1-XXX-D-LC"))
    )
    (comp (ref "CF7.2")
      (value "SFM-120-X1-XXX-D")
      (footprint "eagle-import:SFM-120-X1-XXX-D")
      (libsource (lib "eagle-import") (part "SFM-120-X1-XXX-D"))
    )
    (comp (ref "CF6.1")
      (value "SFM-110-X1-XXX-D-LC")
      (footprint "eagle-import:SFM-110-X1-XXX-D-LC")
      (libsource (lib "eagle-import") (part "SFM-110-X1-XXX-D-LC"))
    )
    (comp (ref "CF6.2")
      (value "SFM-120-X1-XXX-D")
      (footprint "eagle-import:SFM-120-X1-XXX-D")
      (libsource (lib "eagle-import") (part "SFM-120-X1-XXX-D"))
    )
    (comp (ref "CF16.1")
      (value "SFM-110-X1-XXX-D-LC")
      (footprint "eagle-import:SFM-110-X1-XXX-D-LC")
      (libsource (lib "eagle-import") (part "SFM-110-X1-XXX-D-LC"))
    )
    (comp (ref "CF16.2")
      (value "SFM-120-X1-XXX-D")
      (footprint "eagle-import:SFM-120-X1-XXX-D")
      (libsource (lib "eagle-import") (part "SFM-120-X1-XXX-D"))
    )
    (comp (ref "CF3.1")
      (value "SFM-110-X1-XXX-D-LC")
      (footprint "eagle-import:SFM-110-X1-XXX-D-LC")
      (libsource (lib "eagle-import") (part "SFM-110-X1-XXX-D-LC"))
    )
    (comp (ref "CF3.2")
      (value "SFM-120-X1-XXX-D")
      (footprint "eagle-import:SFM-120-X1-XXX-D")
      (libsource (lib "eagle-import") (part "SFM-120-X1-XXX-D"))
    )
    (comp (ref "CM3.2")
      (value "J-MOLEX-SMPM-73300-0111X")
      (footprint "eagle-import:J-MOLEX-SMPM-73300-0111X")
      (libsource (lib "eagle-import") (part "J-MOLEX-SMPM-73300-0111X"))
    )
    (comp (ref "CF8.1")
      (value "SFM-110-X1-XXX-D-LC")
      (footprint "eagle-import:SFM-110-X1-XXX-D-LC")
      (libsource (lib "eagle-import") (part "SFM-110-X1-XXX-D-LC"))
    )
    (comp (ref "CF8.2")
      (value "SFM-120-X1-XXX-D")
      (footprint "eagle-import:SFM-120-X1-XXX-D")
      (libsource (lib "eagle-import") (part "SFM-120-X1-XXX-D"))
    )
    (comp (ref "CF4.1")
      (value "SFM-110-X1-XXX-D-LC")
      (footprint "eagle-import:SFM-110-X1-XXX-D-LC")
      (libsource (lib "eagle-import") (part "SFM-110-X1-XXX-D-LC"))
    )
    (comp (ref "CF4.2")
      (value "SFM-120-X1-XXX-D")
      (footprint "eagle-import:SFM-120-X1-XXX-D")
      (libsource (lib "eagle-import") (part "SFM-120-X1-XXX-D"))
    )
    (comp (ref "CM4.1")
      (value "J-MOLEX-SMPM-73300-0111X")
      (footprint "eagle-import:J-MOLEX-SMPM-73300-0111X")
      (libsource (lib "eagle-import") (part "J-MOLEX-SMPM-73300-0111X"))
    )
    (comp (ref "CM4.2")
      (value "J-MOLEX-SMPM-73300-0111X")
      (footprint "eagle-import:J-MOLEX-SMPM-73300-0111X")
      (libsource (lib "eagle-import") (part "J-MOLEX-SMPM-73300-0111X"))
    )
    (comp (ref "CM4.3")
      (value "J-MOLEX-SMPM-73300-0111X")
      (footprint "eagle-import:J-MOLEX-SMPM-73300-0111X")
      (libsource (lib "eagle-import") (part "J-MOLEX-SMPM-73300-0111X"))
    )
    (comp (ref "CF5.1")
      (value "SFM-110-X1-XXX-D-LC")
      (footprint "eagle-import:SFM-110-X1-XXX-D-LC")
      (libsource (lib "eagle-import") (part "SFM-110-X1-XXX-D-LC"))
    )
    (comp (ref "CF5.2")
      (value "SFM-120-X1-XXX-D")
      (footprint "eagle-import:SFM-120-X1-XXX-D")
      (libsource (lib "eagle-import") (part "SFM-120-X1-XXX-D"))
    )
    (comp (ref "CF17.1")
      (value "SFM-110-X1-XXX-D-LC")
      (footprint "eagle-import:SFM-110-X1-XXX-D-LC")
      (libsource (lib "eagle-import") (part "SFM-110-X1-XXX-D-LC"))
    )
    (comp (ref "CF17.2")
      (value "SFM-120-X1-XXX-D")
      (footprint "eagle-import:SFM-120-X1-XXX-D")
      (libsource (lib "eagle-import") (part "SFM-120-X1-XXX-D"))
    )
    (comp (ref "CF12.1")
      (value "SFM-110-X1-XXX-D-LC")
      (footprint "eagle-import:SFM-110-X1-XXX-D-LC")
      (libsource (lib "eagle-import") (part "SFM-110-X1-XXX-D-LC"))
    )
    (comp (ref "CF12.2")
      (value "SFM-120-X1-XXX-D")
      (footprint "eagle-import:SFM-120-X1-XXX-D")
      (libsource (lib "eagle-import") (part "SFM-120-X1-XXX-D"))
    )
    (comp (ref "CF18.1")
      (value "SFM-110-X1-XXX-D-LC")
      (footprint "eagle-import:SFM-110-X1-XXX-D-LC")
      (libsource (lib "eagle-import") (part "SFM-110-X1-XXX-D-LC"))
    )
    (comp (ref "CF18.2")
      (value "SFM-120-X1-XXX-D")
      (footprint "eagle-import:SFM-120-X1-XXX-D")
      (libsource (lib "eagle-import") (part "SFM-120-X1-XXX-D"))
    )
    (comp (ref "C3")
      (value "1n")
      (footprint "eagle-import:.0603-C-NOSILK")
      (libsource (lib "eagle-import") (part "C-EU0603-C-NOSILK"))
    )
    (comp (ref "C4")
      (value "1n")
      (footprint "eagle-import:.0603-C-NOSILK")
      (libsource (lib "eagle-import") (part "C-EU0603-C-NOSILK"))
    )
    (comp (ref "CF2.4")
      (value "SFM-120-X1-XXX-D")
      (footprint "eagle-import:SFM-120-X1-XXX-D")
      (libsource (lib "eagle-import") (part "SFM-120-X1-XXX-D"))
    )
    (comp (ref "CM20.1")
      (value "J-MOLEX-SMPM-73300-0111X")
      (footprint "eagle-import:J-MOLEX-SMPM-73300-0111X")
      (libsource (lib "eagle-import") (part "J-MOLEX-SMPM-73300-0111X"))
    )
    (comp (ref "CM20.2")
      (value "J-MOLEX-SMPM-73300-0111X")
      (footprint "eagle-import:J-MOLEX-SMPM-73300-0111X")
      (libsource (lib "eagle-import") (part "J-MOLEX-SMPM-73300-0111X"))
    )
    (comp (ref "CM20.3")
      (value "J-MOLEX-SMPM-73300-0111X")
      (footprint "eagle-import:J-MOLEX-SMPM-73300-0111X")
      (libsource (lib "eagle-import") (part "J-MOLEX-SMPM-73300-0111X"))
    )
    (comp (ref "R5")
      (value "60.4")
      (footprint "eagle-import:1206-C")
      (libsource (lib "eagle-import") (part "R-US_1206-C"))
    )
    (comp (ref "R6")
      (value "60.4")
      (footprint "eagle-import:1206-C")
      (libsource (lib "eagle-import") (part "R-US_1206-C"))
    )
    (comp (ref "R7")
      (value "60.4")
      (footprint "eagle-import:1206-C")
      (libsource (lib "eagle-import") (part "R-US_1206-C"))
    )
    (comp (ref "R8")
      (value "60.4")
      (footprint "eagle-import:1206-C")
      (libsource (lib "eagle-import") (part "R-US_1206-C"))
    )
    (comp (ref "CF14.1")
      (value "SFM-110-X1-XXX-D-LC")
      (footprint "eagle-import:SFM-110-X1-XXX-D-LC")
      (libsource (lib "eagle-import") (part "SFM-110-X1-XXX-D-LC"))
    )
    (comp (ref "CF14.2")
      (value "SFM-120-X1-XXX-D")
      (footprint "eagle-import:SFM-120-X1-XXX-D")
      (libsource (lib "eagle-import") (part "SFM-120-X1-XXX-D"))
    )
    (comp (ref "CF2.1")
      (value "SFM-110-X1-XXX-D-LC")
      (footprint "eagle-import:SFM-110-X1-XXX-D-LC")
      (libsource (lib "eagle-import") (part "SFM-110-X1-XXX-D-LC"))
    )
    (comp (ref "CF2.2")
      (value "SFM-120-X1-XXX-D")
      (footprint "eagle-import:SFM-120-X1-XXX-D")
      (libsource (lib "eagle-import") (part "SFM-120-X1-XXX-D"))
    )
    (comp (ref "CM2.1")
      (value "J-MOLEX-SMPM-73300-0111X")
      (footprint "eagle-import:J-MOLEX-SMPM-73300-0111X")
      (libsource (lib "eagle-import") (part "J-MOLEX-SMPM-73300-0111X"))
    )
    (comp (ref "CM2.2")
      (value "J-MOLEX-SMPM-73300-0111X")
      (footprint "eagle-import:J-MOLEX-SMPM-73300-0111X")
      (libsource (lib "eagle-import") (part "J-MOLEX-SMPM-73300-0111X"))
    )
    (comp (ref "C1")
      (value "1n")
      (footprint "eagle-import:.0603-C-NOSILK")
      (libsource (lib "eagle-import") (part "C-EU0603-C-NOSILK"))
    )
    (comp (ref "C2")
      (value "1n")
      (footprint "eagle-import:.0603-C-NOSILK")
      (libsource (lib "eagle-import") (part "C-EU0603-C-NOSILK"))
    )
    (comp (ref "CF2.3")
      (value "SFM-120-X1-XXX-D")
      (footprint "eagle-import:SFM-120-X1-XXX-D")
      (libsource (lib "eagle-import") (part "SFM-120-X1-XXX-D"))
    )
    (comp (ref "CM1.1")
      (value "J-MOLEX-SMPM-73300-0111X")
      (footprint "eagle-import:J-MOLEX-SMPM-73300-0111X")
      (libsource (lib "eagle-import") (part "J-MOLEX-SMPM-73300-0111X"))
    )
    (comp (ref "R1")
      (value "60.4")
      (footprint "eagle-import:1206-C")
      (libsource (lib "eagle-import") (part "R-US_1206-C"))
    )
    (comp (ref "R2")
      (value "60.4")
      (footprint "eagle-import:1206-C")
      (libsource (lib "eagle-import") (part "R-US_1206-C"))
    )
    (comp (ref "R3")
      (value "60.4")
      (footprint "eagle-import:1206-C")
      (libsource (lib "eagle-import") (part "R-US_1206-C"))
    )
    (comp (ref "R4")
      (value "60.4")
      (footprint "eagle-import:1206-C")
      (libsource (lib "eagle-import") (part "R-US_1206-C"))
    )
    (comp (ref "CF19.1")
      (value "SFM-110-X1-XXX-D-LC")
      (footprint "eagle-import:SFM-110-X1-XXX-D-LC")
      (libsource (lib "eagle-import") (part "SFM-110-X1-XXX-D-LC"))
    )
    (comp (ref "CF19.2")
      (value "SFM-120-X1-XXX-D")
      (footprint "eagle-import:SFM-120-X1-XXX-D")
      (libsource (lib "eagle-import") (part "SFM-120-X1-XXX-D"))
    )
    (comp (ref "CF13.1")
      (value "SFM-110-X1-XXX-D-LC")
      (footprint "eagle-import:SFM-110-X1-XXX-D-LC")
      (libsource (lib "eagle-import") (part "SFM-110-X1-XXX-D-LC"))
    )
    (comp (ref "CF13.2")
      (value "SFM-120-X1-XXX-D")
      (footprint "eagle-import:SFM-120-X1-XXX-D")
      (libsource (lib "eagle-import") (part "SFM-120-X1-XXX-D"))
    )
    (comp (ref "CF15.1")
      (value "SFM-110-X1-XXX-D-LC")
      (footprint "eagle-import:SFM-110-X1-XXX-D-LC")
      (libsource (lib "eagle-import") (part "SFM-110-X1-XXX-D-LC"))
    )
    (comp (ref "CF15.2")
      (value "SFM-120-X1-XXX-D")
      (footprint "eagle-import:SFM-120-X1-XXX-D")
      (libsource (lib "eagle-import") (part "SFM-120-X1-XXX-D"))
    )
  )
  (nets
    (net (code "1") (name "AUX-1") (class "Default")
      (node (ref "CF12.1") (pin "1") (pinfunction "1_1") (pintype "passive"))
      (node (ref "CF12.1") (pin "2") (pinfunction "2_2") (pintype "passive"))
      (node (ref "CF13.1") (pin "1") (pinfunction "1_1") (pintype "passive"))
      (node (ref "CF13.1") (pin "2") (pinfunction "2_2") (pintype "passive"))
      (node (ref "CF14.1") (pin "1") (pinfunction "1_1") (pintype "passive"))
      (node (ref "CF14.1") (pin "2") (pinfunction "2_2") (pintype "passive"))
      (node (ref "CF15.1") (pin "1") (pinfunction "1_1") (pintype "passive"))
      (node (ref "CF15.1") (pin "2") (pinfunction "2_2") (pintype "passive"))
      (node (ref "CF16.1") (pin "1") (pinfunction "1_1") (pintype "passive"))
      (node (ref "CF16.1") (pin "2") (pinfunction "2_2") (pintype "passive"))
      (node (ref "CF17.1") (pin "1") (pinfunction "1_1") (pintype "passive"))
      (node (ref "CF17.1") (pin "2") (pinfunction "2_2") (pintype "passive"))
      (node (ref "CF18.1") (pin "1") (pinfunction "1_1") (pintype "passive"))
      (node (ref "CF18.1") (pin "2") (pinfunction "2_2") (pintype "passive"))
      (node (ref "CF19.1") (pin "1") (pinfunction "1_1") (pintype "passive"))
      (node (ref "CF19.1") (pin "2") (pinfunction "2_2") (pintype "passive"))
      (node (ref "CF2.1") (pin "1") (pinfunction "1_1") (pintype "passive"))
      (node (ref "CF2.1") (pin "2") (pinfunction "2_2") (pintype "passive"))
      (node (ref "CF3.1") (pin "1") (pinfunction "1_1") (pintype "passive"))
      (node (ref "CF3.1") (pin "2") (pinfunction "2_2") (pintype "passive"))
      (node (ref "CF4.1") (pin "1") (pinfunction "1_1") (pintype "passive"))
      (node (ref "CF4.1") (pin "2") (pinfunction "2_2") (pintype "passive"))
      (node (ref "CF5.1") (pin "1") (pinfunction "1_1") (pintype "passive"))
      (node (ref "CF5.1") (pin "2") (pinfunction "2_2") (pintype "passive"))
      (node (ref "CF6.1") (pin "1") (pinfunction "1_1") (pintype "passive"))
      (node (ref "CF6.1") (pin "2") (pinfunction "2_2") (pintype "passive"))
      (node (ref "CF7.1") (pin "1") (pinfunction "1_1") (pintype "passive"))
      (node (ref "CF7.1") (pin "2") (pinfunction "2_2") (pintype "passive"))
      (node (ref "CF8.1") (pin "1") (pinfunction "1_1") (pintype "passive"))
      (node (ref "CF8.1") (pin "2") (pinfunction "2_2") (pintype "passive"))
    )
    (net (code "2") (name "AUX-2") (class "Default")
      (node (ref "CF12.1") (pin "3") (pinfunction "3_3") (pintype "passive"))
      (node (ref "CF12.1") (pin "4") (pinfunction "4_4") (pintype "passive"))
      (node (ref "CF13.1") (pin "3") (pinfunction "3_3") (pintype "passive"))
      (node (ref "CF13.1") (pin "4") (pinfunction "4_4") (pintype "passive"))
      (node (ref "CF14.1") (pin "3") (pinfunction "3_3") (pintype "passive"))
      (node (ref "CF14.1") (pin "4") (pinfunction "4_4") (pintype "passive"))
      (node (ref "CF15.1") (pin "3") (pinfunction "3_3") (pintype "passive"))
      (node (ref "CF15.1") (pin "4") (pinfunction "4_4") (pintype "passive"))
      (node (ref "CF16.1") (pin "3") (pinfunction "3_3") (pintype "passive"))
      (node (ref "CF16.1") (pin "4") (pinfunction "4_4") (pintype "passive"))
      (node (ref "CF17.1") (pin "3") (pinfunction "3_3") (pintype "passive"))
      (node (ref "CF17.1") (pin "4") (pinfunction "4_4") (pintype "passive"))
      (node (ref "CF18.1") (pin "3") (pinfunction "3_3") (pintype "passive"))
      (node (ref "CF18.1") (pin "4") (pinfunction "4_4") (pintype "passive"))
      (node (ref "CF19.1") (pin "3") (pinfunction "3_3") (pintype "passive"))
      (node (ref "CF19.1") (pin "4") (pinfunction "4_4") (pintype "passive"))
      (node (ref "CF2.1") (pin "3") (pinfunction "3_3") (pintype "passive"))
      (node (ref "CF2.1") (pin "4") (pinfunction "4_4") (pintype "passive"))
      (node (ref "CF3.1") (pin "3") (pinfunction "3_3") (pintype "passive"))
      (node (ref "CF3.1") (pin "4") (pinfunction "4_4") (pintype "passive"))
      (node (ref "CF4.1") (pin "3") (pinfunction "3_3") (pintype "passive"))
      (node (ref "CF4.1") (pin "4") (pinfunction "4_4") (pintype "passive"))
      (node (ref "CF5.1") (pin "3") (pinfunction "3_3") (pintype "passive"))
      (node (ref "CF5.1") (pin "4") (pinfunction "4_4") (pintype "passive"))
      (node (ref "CF6.1") (pin "3") (pinfunction "3_3") (pintype "passive"))
      (node (ref "CF6.1") (pin "4") (pinfunction "4_4") (pintype "passive"))
      (node (ref "CF7.1") (pin "3") (pinfunction "3_3") (pintype "passive"))
      (node (ref "CF7.1") (pin "4") (pinfunction "4_4") (pintype "passive"))
      (node (ref "CF8.1") (pin "3") (pinfunction "3_3") (pintype "passive"))
      (node (ref "CF8.1") (pin "4") (pinfunction "4_4") (pintype "passive"))
    )
    (net (code "3") (name "AUX-3") (class "Default")
      (node (ref "CF12.1") (pin "5") (pinfunction "5_5") (pintype "passive"))
      (node (ref "CF12.1") (pin "6") (pinfunction "6_6") (pintype "passive"))
      (node (ref "CF13.1") (pin "5") (pinfunction "5_5") (pintype "passive"))
      (node (ref "CF13.1") (pin "6") (pinfunction "6_6") (pintype "passive"))
      (node (ref "CF14.1") (pin "5") (pinfunction "5_5") (pintype "passive"))
      (node (ref "CF14.1") (pin "6") (pinfunction "6_6") (pintype "passive"))
      (node (ref "CF15.1") (pin "5") (pinfunction "5_5") (pintype "passive"))
      (node (ref "CF15.1") (pin "6") (pinfunction "6_6") (pintype "passive"))
      (node (ref "CF16.1") (pin "5") (pinfunction "5_5") (pintype "passive"))
      (node (ref "CF16.1") (pin "6") (pinfunction "6_6") (pintype "passive"))
      (node (ref "CF17.1") (pin "5") (pinfunction "5_5") (pintype "passive"))
      (node (ref "CF17.1") (pin "6") (pinfunction "6_6") (pintype "passive"))
      (node (ref "CF18.1") (pin "5") (pinfunction "5_5") (pintype "passive"))
      (node (ref "CF18.1") (pin "6") (pinfunction "6_6") (pintype "passive"))
      (node (ref "CF19.1") (pin "5") (pinfunction "5_5") (pintype "passive"))
      (node (ref "CF19.1") (pin "6") (pinfunction "6_6") (pintype "passive"))
      (node (ref "CF2.1") (pin "5") (pinfunction "5_5") (pintype "passive"))
      (node (ref "CF2.1") (pin "6") (pinfunction "6_6") (pintype "passive"))
      (node (ref "CF3.1") (pin "5") (pinfunction "5_5") (pintype "passive"))
      (node (ref "CF3.1") (pin "6") (pinfunction "6_6") (pintype "passive"))
      (node (ref "CF4.1") (pin "5") (pinfunction "5_5") (pintype "passive"))
      (node (ref "CF4.1") (pin "6") (pinfunction "6_6") (pintype "passive"))
      (node (ref "CF5.1") (pin "5") (pinfunction "5_5") (pintype "passive"))
      (node (ref "CF5.1") (pin "6") (pinfunction "6_6") (pintype "passive"))
      (node (ref "CF6.1") (pin "5") (pinfunction "5_5") (pintype "passive"))
      (node (ref "CF6.1") (pin "6") (pinfunction "6_6") (pintype "passive"))
      (node (ref "CF7.1") (pin "5") (pinfunction "5_5") (pintype "passive"))
      (node (ref "CF7.1") (pin "6") (pinfunction "6_6") (pintype "passive"))
      (node (ref "CF8.1") (pin "5") (pinfunction "5_5") (pintype "passive"))
      (node (ref "CF8.1") (pin "6") (pinfunction "6_6") (pintype "passive"))
    )
    (net (code "4") (name "AUX-4") (class "Default")
      (node (ref "CF12.1") (pin "7") (pinfunction "7_7") (pintype "passive"))
      (node (ref "CF12.1") (pin "8") (pinfunction "8_8") (pintype "passive"))
      (node (ref "CF13.1") (pin "7") (pinfunction "7_7") (pintype "passive"))
      (node (ref "CF13.1") (pin "8") (pinfunction "8_8") (pintype "passive"))
      (node (ref "CF14.1") (pin "7") (pinfunction "7_7") (pintype "passive"))
      (node (ref "CF14.1") (pin "8") (pinfunction "8_8") (pintype "passive"))
      (node (ref "CF15.1") (pin "7") (pinfunction "7_7") (pintype "passive"))
      (node (ref "CF15.1") (pin "8") (pinfunction "8_8") (pintype "passive"))
      (node (ref "CF16.1") (pin "7") (pinfunction "7_7") (pintype "passive"))
      (node (ref "CF16.1") (pin "8") (pinfunction "8_8") (pintype "passive"))
      (node (ref "CF17.1") (pin "7") (pinfunction "7_7") (pintype "passive"))
      (node (ref "CF17.1") (pin "8") (pinfunction "8_8") (pintype "passive"))
      (node (ref "CF18.1") (pin "7") (pinfunction "7_7") (pintype "passive"))
      (node (ref "CF18.1") (pin "8") (pinfunction "8_8") (pintype "passive"))
      (node (ref "CF19.1") (pin "7") (pinfunction "7_7") (pintype "passive"))
      (node (ref "CF19.1") (pin "8") (pinfunction "8_8") (pintype "passive"))
      (node (ref "CF2.1") (pin "7") (pinfunction "7_7") (pintype "passive"))
      (node (ref "CF2.1") (pin "8") (pinfunction "8_8") (pintype "passive"))
      (node (ref "CF3.1") (pin "7") (pinfunction "7_7") (pintype "passive"))
      (node (ref "CF3.1") (pin "8") (pinfunction "8_8") (pintype "passive"))
      (node (ref "CF4.1") (pin "7") (pinfunction "7_7") (pintype "passive"))
      (node (ref "CF4.1") (pin "8") (pinfunction "8_8") (pintype "passive"))
      (node (ref "CF5.1") (pin "7") (pinfunction "7_7") (pintype "passive"))
      (node (ref "CF5.1") (pin "8") (pinfunction "8_8") (pintype "passive"))
      (node (ref "CF6.1") (pin "7") (pinfunction "7_7") (pintype "passive"))
      (node (ref "CF6.1") (pin "8") (pinfunction "8_8") (pintype "passive"))
      (node (ref "CF7.1") (pin "7") (pinfunction "7_7") (pintype "passive"))
      (node (ref "CF7.1") (pin "8") (pinfunction "8_8") (pintype "passive"))
      (node (ref "CF8.1") (pin "7") (pinfunction "7_7") (pintype "passive"))
      (node (ref "CF8.1") (pin "8") (pinfunction "8_8") (pintype "passive"))
    )
    (net (code "5") (name "AUX-5") (class "Default")
      (node (ref "CF12.1") (pin "10") (pinfunction "10_10") (pintype "passive"))
      (node (ref "CF12.1") (pin "9") (pinfunction "9_9") (pintype "passive"))
      (node (ref "CF13.1") (pin "10") (pinfunction "10_10") (pintype "passive"))
      (node (ref "CF13.1") (pin "9") (pinfunction "9_9") (pintype "passive"))
      (node (ref "CF14.1") (pin "10") (pinfunction "10_10") (pintype "passive"))
      (node (ref "CF14.1") (pin "9") (pinfunction "9_9") (pintype "passive"))
      (node (ref "CF15.1") (pin "10") (pinfunction "10_10") (pintype "passive"))
      (node (ref "CF15.1") (pin "9") (pinfunction "9_9") (pintype "passive"))
      (node (ref "CF16.1") (pin "10") (pinfunction "10_10") (pintype "passive"))
      (node (ref "CF16.1") (pin "9") (pinfunction "9_9") (pintype "passive"))
      (node (ref "CF17.1") (pin "10") (pinfunction "10_10") (pintype "passive"))
      (node (ref "CF17.1") (pin "9") (pinfunction "9_9") (pintype "passive"))
      (node (ref "CF18.1") (pin "10") (pinfunction "10_10") (pintype "passive"))
      (node (ref "CF18.1") (pin "9") (pinfunction "9_9") (pintype "passive"))
      (node (ref "CF19.1") (pin "10") (pinfunction "10_10") (pintype "passive"))
      (node (ref "CF19.1") (pin "9") (pinfunction "9_9") (pintype "passive"))
      (node (ref "CF2.1") (pin "10") (pinfunction "10_10") (pintype "passive"))
      (node (ref "CF2.1") (pin "9") (pinfunction "9_9") (pintype "passive"))
      (node (ref "CF3.1") (pin "10") (pinfunction "10_10") (pintype "passive"))
      (node (ref "CF3.1") (pin "9") (pinfunction "9_9") (pintype "passive"))
      (node (ref "CF4.1") (pin "10") (pinfunction "10_10") (pintype "passive"))
      (node (ref "CF4.1") (pin "9") (pinfunction "9_9") (pintype "passive"))
      (node (ref "CF5.1") (pin "10") (pinfunction "10_10") (pintype "passive"))
      (node (ref "CF5.1") (pin "9") (pinfunction "9_9") (pintype "passive"))
      (node (ref "CF6.1") (pin "10") (pinfunction "10_10") (pintype "passive"))
      (node (ref "CF6.1") (pin "9") (pinfunction "9_9") (pintype "passive"))
      (node (ref "CF7.1") (pin "10") (pinfunction "10_10") (pintype "passive"))
      (node (ref "CF7.1") (pin "9") (pinfunction "9_9") (pintype "passive"))
      (node (ref "CF8.1") (pin "10") (pinfunction "10_10") (pintype "passive"))
      (node (ref "CF8.1") (pin "9") (pinfunction "9_9") (pintype "passive"))
    )
    (net (code "6") (name "AUX-6") (class "Default")
      (node (ref "CF12.1") (pin "11") (pinfunction "11_11") (pintype "passive"))
      (node (ref "CF12.1") (pin "12") (pinfunction "12_12") (pintype "passive"))
      (node (ref "CF13.1") (pin "11") (pinfunction "11_11") (pintype "passive"))
      (node (ref "CF13.1") (pin "12") (pinfunction "12_12") (pintype "passive"))
      (node (ref "CF14.1") (pin "11") (pinfunction "11_11") (pintype "passive"))
      (node (ref "CF14.1") (pin "12") (pinfunction "12_12") (pintype "passive"))
      (node (ref "CF15.1") (pin "11") (pinfunction "11_11") (pintype "passive"))
      (node (ref "CF15.1") (pin "12") (pinfunction "12_12") (pintype "passive"))
      (node (ref "CF16.1") (pin "11") (pinfunction "11_11") (pintype "passive"))
      (node (ref "CF16.1") (pin "12") (pinfunction "12_12") (pintype "passive"))
      (node (ref "CF17.1") (pin "11") (pinfunction "11_11") (pintype "passive"))
      (node (ref "CF17.1") (pin "12") (pinfunction "12_12") (pintype "passive"))
      (node (ref "CF18.1") (pin "11") (pinfunction "11_11") (pintype "passive"))
      (node (ref "CF18.1") (pin "12") (pinfunction "12_12") (pintype "passive"))
      (node (ref "CF19.1") (pin "11") (pinfunction "11_11") (pintype "passive"))
      (node (ref "CF19.1") (pin "12") (pinfunction "12_12") (pintype "passive"))
      (node (ref "CF2.1") (pin "11") (pinfunction "11_11") (pintype "passive"))
      (node (ref "CF2.1") (pin "12") (pinfunction "12_12") (pintype "passive"))
      (node (ref "CF3.1") (pin "11") (pinfunction "11_11") (pintype "passive"))
      (node (ref "CF3.1") (pin "12") (pinfunction "12_12") (pintype "passive"))
      (node (ref "CF4.1") (pin "11") (pinfunction "11_11") (pintype "passive"))
      (node (ref "CF4.1") (pin "12") (pinfunction "12_12") (pintype "passive"))
      (node (ref "CF5.1") (pin "11") (pinfunction "11_11") (pintype "passive"))
      (node (ref "CF5.1") (pin "12") (pinfunction "12_12") (pintype "passive"))
      (node (ref "CF6.1") (pin "11") (pinfunction "11_11") (pintype "passive"))
      (node (ref "CF6.1") (pin "12") (pinfunction "12_12") (pintype "passive"))
      (node (ref "CF7.1") (pin "11") (pinfunction "11_11") (pintype "passive"))
      (node (ref "CF7.1") (pin "12") (pinfunction "12_12") (pintype "passive"))
      (node (ref "CF8.1") (pin "11") (pinfunction "11_11") (pintype "passive"))
      (node (ref "CF8.1") (pin "12") (pinfunction "12_12") (pintype "passive"))
    )
    (net (code "7") (name "AUX-7") (class "Default")
      (node (ref "CF12.1") (pin "13") (pinfunction "13_13") (pintype "passive"))
      (node (ref "CF12.1") (pin "14") (pinfunction "14_14") (pintype "passive"))
      (node (ref "CF13.1") (pin "13") (pinfunction "13_13") (pintype "passive"))
      (node (ref "CF13.1") (pin "14") (pinfunction "14_14") (pintype "passive"))
      (node (ref "CF14.1") (pin "13") (pinfunction "13_13") (pintype "passive"))
      (node (ref "CF14.1") (pin "14") (pinfunction "14_14") (pintype "passive"))
      (node (ref "CF15.1") (pin "13") (pinfunction "13_13") (pintype "passive"))
      (node (ref "CF15.1") (pin "14") (pinfunction "14_14") (pintype "passive"))
      (node (ref "CF16.1") (pin "13") (pinfunction "13_13") (pintype "passive"))
      (node (ref "CF16.1") (pin "14") (pinfunction "14_14") (pintype "passive"))
      (node (ref "CF17.1") (pin "13") (pinfunction "13_13") (pintype "passive"))
      (node (ref "CF17.1") (pin "14") (pinfunction "14_14") (pintype "passive"))
      (node (ref "CF18.1") (pin "13") (pinfunction "13_13") (pintype "passive"))
      (node (ref "CF18.1") (pin "14") (pinfunction "14_14") (pintype "passive"))
      (node (ref "CF19.1") (pin "13") (pinfunction "13_13") (pintype "passive"))
      (node (ref "CF19.1") (pin "14") (pinfunction "14_14") (pintype "passive"))
      (node (ref "CF2.1") (pin "13") (pinfunction "13_13") (pintype "passive"))
      (node (ref "CF2.1") (pin "14") (pinfunction "14_14") (pintype "passive"))
      (node (ref "CF3.1") (pin "13") (pinfunction "13_13") (pintype "passive"))
      (node (ref "CF3.1") (pin "14") (pinfunction "14_14") (pintype "passive"))
      (node (ref "CF4.1") (pin "13") (pinfunction "13_13") (pintype "passive"))
      (node (ref "CF4.1") (pin "14") (pinfunction "14_14") (pintype "passive"))
      (node (ref "CF5.1") (pin "13") (pinfunction "13_13") (pintype "passive"))
      (node (ref "CF5.1") (pin "14") (pinfunction "14_14") (pintype "passive"))
      (node (ref "CF6.1") (pin "13") (pinfunction "13_13") (pintype "passive"))
      (node (ref "CF6.1") (pin "14") (pinfunction "14_14") (pintype "passive"))
      (node (ref "CF7.1") (pin "13") (pinfunction "13_13") (pintype "passive"))
      (node (ref "CF7.1") (pin "14") (pinfunction "14_14") (pintype "passive"))
      (node (ref "CF8.1") (pin "13") (pinfunction "13_13") (pintype "passive"))
      (node (ref "CF8.1") (pin "14") (pinfunction "14_14") (pintype "passive"))
    )
    (net (code "8") (name "AUX-8") (class "Default")
      (node (ref "CF12.1") (pin "15") (pinfunction "15_15") (pintype "passive"))
      (node (ref "CF12.1") (pin "16") (pinfunction "16_16") (pintype "passive"))
      (node (ref "CF13.1") (pin "15") (pinfunction "15_15") (pintype "passive"))
      (node (ref "CF13.1") (pin "16") (pinfunction "16_16") (pintype "passive"))
      (node (ref "CF14.1") (pin "15") (pinfunction "15_15") (pintype "passive"))
      (node (ref "CF14.1") (pin "16") (pinfunction "16_16") (pintype "passive"))
      (node (ref "CF15.1") (pin "15") (pinfunction "15_15") (pintype "passive"))
      (node (ref "CF15.1") (pin "16") (pinfunction "16_16") (pintype "passive"))
      (node (ref "CF16.1") (pin "15") (pinfunction "15_15") (pintype "passive"))
      (node (ref "CF16.1") (pin "16") (pinfunction "16_16") (pintype "passive"))
      (node (ref "CF17.1") (pin "15") (pinfunction "15_15") (pintype "passive"))
      (node (ref "CF17.1") (pin "16") (pinfunction "16_16") (pintype "passive"))
      (node (ref "CF18.1") (pin "15") (pinfunction "15_15") (pintype "passive"))
      (node (ref "CF18.1") (pin "16") (pinfunction "16_16") (pintype "passive"))
      (node (ref "CF19.1") (pin "15") (pinfunction "15_15") (pintype "passive"))
      (node (ref "CF19.1") (pin "16") (pinfunction "16_16") (pintype "passive"))
      (node (ref "CF2.1") (pin "15") (pinfunction "15_15") (pintype "passive"))
      (node (ref "CF2.1") (pin "16") (pinfunction "16_16") (pintype "passive"))
      (node (ref "CF3.1") (pin "15") (pinfunction "15_15") (pintype "passive"))
      (node (ref "CF3.1") (pin "16") (pinfunction "16_16") (pintype "passive"))
      (node (ref "CF4.1") (pin "15") (pinfunction "15_15") (pintype "passive"))
      (node (ref "CF4.1") (pin "16") (pinfunction "16_16") (pintype "passive"))
      (node (ref "CF5.1") (pin "15") (pinfunction "15_15") (pintype "passive"))
      (node (ref "CF5.1") (pin "16") (pinfunction "16_16") (pintype "passive"))
      (node (ref "CF6.1") (pin "15") (pinfunction "15_15") (pintype "passive"))
      (node (ref "CF6.1") (pin "16") (pinfunction "16_16") (pintype "passive"))
      (node (ref "CF7.1") (pin "15") (pinfunction "15_15") (pintype "passive"))
      (node (ref "CF7.1") (pin "16") (pinfunction "16_16") (pintype "passive"))
      (node (ref "CF8.1") (pin "15") (pinfunction "15_15") (pintype "passive"))
      (node (ref "CF8.1") (pin "16") (pinfunction "16_16") (pintype "passive"))
    )
    (net (code "9") (name "AUX-9") (class "Default")
      (node (ref "CF12.1") (pin "17") (pinfunction "17_17") (pintype "passive"))
      (node (ref "CF12.1") (pin "18") (pinfunction "18_18") (pintype "passive"))
      (node (ref "CF13.1") (pin "17") (pinfunction "17_17") (pintype "passive"))
      (node (ref "CF13.1") (pin "18") (pinfunction "18_18") (pintype "passive"))
      (node (ref "CF14.1") (pin "17") (pinfunction "17_17") (pintype "passive"))
      (node (ref "CF14.1") (pin "18") (pinfunction "18_18") (pintype "passive"))
      (node (ref "CF15.1") (pin "17") (pinfunction "17_17") (pintype "passive"))
      (node (ref "CF15.1") (pin "18") (pinfunction "18_18") (pintype "passive"))
      (node (ref "CF16.1") (pin "17") (pinfunction "17_17") (pintype "passive"))
      (node (ref "CF16.1") (pin "18") (pinfunction "18_18") (pintype "passive"))
      (node (ref "CF17.1") (pin "17") (pinfunction "17_17") (pintype "passive"))
      (node (ref "CF17.1") (pin "18") (pinfunction "18_18") (pintype "passive"))
      (node (ref "CF18.1") (pin "17") (pinfunction "17_17") (pintype "passive"))
      (node (ref "CF18.1") (pin "18") (pinfunction "18_18") (pintype "passive"))
      (node (ref "CF19.1") (pin "17") (pinfunction "17_17") (pintype "passive"))
      (node (ref "CF19.1") (pin "18") (pinfunction "18_18") (pintype "passive"))
      (node (ref "CF2.1") (pin "17") (pinfunction "17_17") (pintype "passive"))
      (node (ref "CF2.1") (pin "18") (pinfunction "18_18") (pintype "passive"))
      (node (ref "CF3.1") (pin "17") (pinfunction "17_17") (pintype "passive"))
      (node (ref "CF3.1") (pin "18") (pinfunction "18_18") (pintype "passive"))
      (node (ref "CF4.1") (pin "17") (pinfunction "17_17") (pintype "passive"))
      (node (ref "CF4.1") (pin "18") (pinfunction "18_18") (pintype "passive"))
      (node (ref "CF5.1") (pin "17") (pinfunction "17_17") (pintype "passive"))
      (node (ref "CF5.1") (pin "18") (pinfunction "18_18") (pintype "passive"))
      (node (ref "CF6.1") (pin "17") (pinfunction "17_17") (pintype "passive"))
      (node (ref "CF6.1") (pin "18") (pinfunction "18_18") (pintype "passive"))
      (node (ref "CF7.1") (pin "17") (pinfunction "17_17") (pintype "passive"))
      (node (ref "CF7.1") (pin "18") (pinfunction "18_18") (pintype "passive"))
      (node (ref "CF8.1") (pin "17") (pinfunction "17_17") (pintype "passive"))
      (node (ref "CF8.1") (pin "18") (pinfunction "18_18") (pintype "passive"))
    )
    (net (code "10") (name "AUX-10") (class "Default")
      (node (ref "CF12.1") (pin "19") (pinfunction "19_19") (pintype "passive"))
      (node (ref "CF12.1") (pin "20") (pinfunction "20_20") (pintype "passive"))
      (node (ref "CF13.1") (pin "19") (pinfunction "19_19") (pintype "passive"))
      (node (ref "CF13.1") (pin "20") (pinfunction "20_20") (pintype "passive"))
      (node (ref "CF14.1") (pin "19") (pinfunction "19_19") (pintype "passive"))
      (node (ref "CF14.1") (pin "20") (pinfunction "20_20") (pintype "passive"))
      (node (ref "CF15.1") (pin "19") (pinfunction "19_19") (pintype "passive"))
      (node (ref "CF15.1") (pin "20") (pinfunction "20_20") (pintype "passive"))
      (node (ref "CF16.1") (pin "19") (pinfunction "19_19") (pintype "passive"))
      (node (ref "CF16.1") (pin "20") (pinfunction "20_20") (pintype "passive"))
      (node (ref "CF17.1") (pin "19") (pinfunction "19_19") (pintype "passive"))
      (node (ref "CF17.1") (pin "20") (pinfunction "20_20") (pintype "passive"))
      (node (ref "CF18.1") (pin "19") (pinfunction "19_19") (pintype "passive"))
      (node (ref "CF18.1") (pin "20") (pinfunction "20_20") (pintype "passive"))
      (node (ref "CF19.1") (pin "19") (pinfunction "19_19") (pintype "passive"))
      (node (ref "CF19.1") (pin "20") (pinfunction "20_20") (pintype "passive"))
      (node (ref "CF2.1") (pin "19") (pinfunction "19_19") (pintype "passive"))
      (node (ref "CF2.1") (pin "20") (pinfunction "20_20") (pintype "passive"))
      (node (ref "CF3.1") (pin "19") (pinfunction "19_19") (pintype "passive"))
      (node (ref "CF3.1") (pin "20") (pinfunction "20_20") (pintype "passive"))
      (node (ref "CF4.1") (pin "19") (pinfunction "19_19") (pintype "passive"))
      (node (ref "CF4.1") (pin "20") (pinfunction "20_20") (pintype "passive"))
      (node (ref "CF5.1") (pin "19") (pinfunction "19_19") (pintype "passive"))
      (node (ref "CF5.1") (pin "20") (pinfunction "20_20") (pintype "passive"))
      (node (ref "CF6.1") (pin "19") (pinfunction "19_19") (pintype "passive"))
      (node (ref "CF6.1") (pin "20") (pinfunction "20_20") (pintype "passive"))
      (node (ref "CF7.1") (pin "19") (pinfunction "19_19") (pintype "passive"))
      (node (ref "CF7.1") (pin "20") (pinfunction "20_20") (pintype "passive"))
      (node (ref "CF8.1") (pin "19") (pinfunction "19_19") (pintype "passive"))
      (node (ref "CF8.1") (pin "20") (pinfunction "20_20") (pintype "passive"))
    )
    (net (code "11") (name "CAN1_H") (class "Default")
      (node (ref "CF12.2") (pin "33") (pinfunction "33_33") (pintype "passive"))
      (node (ref "CF12.2") (pin "34") (pinfunction "34_34") (pintype "passive"))
      (node (ref "CF13.2") (pin "33") (pinfunction "33_33") (pintype "passive"))
      (node (ref "CF13.2") (pin "34") (pinfunction "34_34") (pintype "passive"))
      (node (ref "CF14.2") (pin "33") (pinfunction "33_33") (pintype "passive"))
      (node (ref "CF14.2") (pin "34") (pinfunction "34_34") (pintype "passive"))
      (node (ref "CF15.2") (pin "33") (pinfunction "33_33") (pintype "passive"))
      (node (ref "CF15.2") (pin "34") (pinfunction "34_34") (pintype "passive"))
      (node (ref "CF16.2") (pin "33") (pinfunction "33_33") (pintype "passive"))
      (node (ref "CF16.2") (pin "34") (pinfunction "34_34") (pintype "passive"))
      (node (ref "CF17.2") (pin "33") (pinfunction "33_33") (pintype "passive"))
      (node (ref "CF17.2") (pin "34") (pinfunction "34_34") (pintype "passive"))
      (node (ref "CF18.2") (pin "33") (pinfunction "33_33") (pintype "passive"))
      (node (ref "CF18.2") (pin "34") (pinfunction "34_34") (pintype "passive"))
      (node (ref "CF19.2") (pin "33") (pinfunction "33_33") (pintype "passive"))
      (node (ref "CF19.2") (pin "34") (pinfunction "34_34") (pintype "passive"))
      (node (ref "CF2.2") (pin "33") (pinfunction "33_33") (pintype "passive"))
      (node (ref "CF2.2") (pin "34") (pinfunction "34_34") (pintype "passive"))
      (node (ref "CF2.3") (pin "33") (pinfunction "33_33") (pintype "passive"))
      (node (ref "CF2.3") (pin "34") (pinfunction "34_34") (pintype "passive"))
      (node (ref "CF2.4") (pin "33") (pinfunction "33_33") (pintype "passive"))
      (node (ref "CF2.4") (pin "34") (pinfunction "34_34") (pintype "passive"))
      (node (ref "CF3.2") (pin "33") (pinfunction "33_33") (pintype "passive"))
      (node (ref "CF3.2") (pin "34") (pinfunction "34_34") (pintype "passive"))
      (node (ref "CF4.2") (pin "33") (pinfunction "33_33") (pintype "passive"))
      (node (ref "CF4.2") (pin "34") (pinfunction "34_34") (pintype "passive"))
      (node (ref "CF5.2") (pin "33") (pinfunction "33_33") (pintype "passive"))
      (node (ref "CF5.2") (pin "34") (pinfunction "34_34") (pintype "passive"))
      (node (ref "CF6.2") (pin "33") (pinfunction "33_33") (pintype "passive"))
      (node (ref "CF6.2") (pin "34") (pinfunction "34_34") (pintype "passive"))
      (node (ref "CF7.2") (pin "33") (pinfunction "33_33") (pintype "passive"))
      (node (ref "CF7.2") (pin "34") (pinfunction "34_34") (pintype "passive"))
      (node (ref "CF8.2") (pin "33") (pinfunction "33_33") (pintype "passive"))
      (node (ref "CF8.2") (pin "34") (pinfunction "34_34") (pintype "passive"))
      (node (ref "R1") (pin "1") (pinfunction "1_1") (pintype "passive"))
      (node (ref "R5") (pin "1") (pinfunction "1_1") (pintype "passive"))
    )
    (net (code "12") (name "CAN1_L") (class "Default")
      (node (ref "CF12.2") (pin "35") (pinfunction "35_35") (pintype "passive"))
      (node (ref "CF12.2") (pin "36") (pinfunction "36_36") (pintype "passive"))
      (node (ref "CF13.2") (pin "35") (pinfunction "35_35") (pintype "passive"))
      (node (ref "CF13.2") (pin "36") (pinfunction "36_36") (pintype "passive"))
      (node (ref "CF14.2") (pin "35") (pinfunction "35_35") (pintype "passive"))
      (node (ref "CF14.2") (pin "36") (pinfunction "36_36") (pintype "passive"))
      (node (ref "CF15.2") (pin "35") (pinfunction "35_35") (pintype "passive"))
      (node (ref "CF15.2") (pin "36") (pinfunction "36_36") (pintype "passive"))
      (node (ref "CF16.2") (pin "35") (pinfunction "35_35") (pintype "passive"))
      (node (ref "CF16.2") (pin "36") (pinfunction "36_36") (pintype "passive"))
      (node (ref "CF17.2") (pin "35") (pinfunction "35_35") (pintype "passive"))
      (node (ref "CF17.2") (pin "36") (pinfunction "36_36") (pintype "passive"))
      (node (ref "CF18.2") (pin "35") (pinfunction "35_35") (pintype "passive"))
      (node (ref "CF18.2") (pin "36") (pinfunction "36_36") (pintype "passive"))
      (node (ref "CF19.2") (pin "35") (pinfunction "35_35") (pintype "passive"))
      (node (ref "CF19.2") (pin "36") (pinfunction "36_36") (pintype "passive"))
      (node (ref "CF2.2") (pin "35") (pinfunction "35_35") (pintype "passive"))
      (node (ref "CF2.2") (pin "36") (pinfunction "36_36") (pintype "passive"))
      (node (ref "CF2.3") (pin "35") (pinfunction "35_35") (pintype "passive"))
      (node (ref "CF2.3") (pin "36") (pinfunction "36_36") (pintype "passive"))
      (node (ref "CF2.4") (pin "35") (pinfunction "35_35") (pintype "passive"))
      (node (ref "CF2.4") (pin "36") (pinfunction "36_36") (pintype "passive"))
      (node (ref "CF3.2") (pin "35") (pinfunction "35_35") (pintype "passive"))
      (node (ref "CF3.2") (pin "36") (pinfunction "36_36") (pintype "passive"))
      (node (ref "CF4.2") (pin "35") (pinfunction "35_35") (pintype "passive"))
      (node (ref "CF4.2") (pin "36") (pinfunction "36_36") (pintype "passive"))
      (node (ref "CF5.2") (pin "35") (pinfunction "35_35") (pintype "passive"))
      (node (ref "CF5.2") (pin "36") (pinfunction "36_36") (pintype "passive"))
      (node (ref "CF6.2") (pin "35") (pinfunction "35_35") (pintype "passive"))
      (node (ref "CF6.2") (pin "36") (pinfunction "36_36") (pintype "passive"))
      (node (ref "CF7.2") (pin "35") (pinfunction "35_35") (pintype "passive"))
      (node (ref "CF7.2") (pin "36") (pinfunction "36_36") (pintype "passive"))
      (node (ref "CF8.2") (pin "35") (pinfunction "35_35") (pintype "passive"))
      (node (ref "CF8.2") (pin "36") (pinfunction "36_36") (pintype "passive"))
      (node (ref "R2") (pin "1") (pinfunction "1_1") (pintype "passive"))
      (node (ref "R6") (pin "1") (pinfunction "1_1") (pintype "passive"))
    )
    (net (code "13") (name "CAN2_H") (class "Default")
      (node (ref "CF12.2") (pin "17") (pinfunction "17_17") (pintype "passive"))
      (node (ref "CF12.2") (pin "18") (pinfunction "18_18") (pintype "passive"))
      (node (ref "CF13.2") (pin "17") (pinfunction "17_17") (pintype "passive"))
      (node (ref "CF13.2") (pin "18") (pinfunction "18_18") (pintype "passive"))
      (node (ref "CF14.2") (pin "17") (pinfunction "17_17") (pintype "passive"))
      (node (ref "CF14.2") (pin "18") (pinfunction "18_18") (pintype "passive"))
      (node (ref "CF15.2") (pin "17") (pinfunction "17_17") (pintype "passive"))
      (node (ref "CF15.2") (pin "18") (pinfunction "18_18") (pintype "passive"))
      (node (ref "CF16.2") (pin "17") (pinfunction "17_17") (pintype "passive"))
      (node (ref "CF16.2") (pin "18") (pinfunction "18_18") (pintype "passive"))
      (node (ref "CF17.2") (pin "17") (pinfunction "17_17") (pintype "passive"))
      (node (ref "CF17.2") (pin "18") (pinfunction "18_18") (pintype "passive"))
      (node (ref "CF18.2") (pin "17") (pinfunction "17_17") (pintype "passive"))
      (node (ref "CF18.2") (pin "18") (pinfunction "18_18") (pintype "passive"))
      (node (ref "CF19.2") (pin "17") (pinfunction "17_17") (pintype "passive"))
      (node (ref "CF19.2") (pin "18") (pinfunction "18_18") (pintype "passive"))
      (node (ref "CF2.2") (pin "17") (pinfunction "17_17") (pintype "passive"))
      (node (ref "CF2.2") (pin "18") (pinfunction "18_18") (pintype "passive"))
      (node (ref "CF2.3") (pin "17") (pinfunction "17_17") (pintype "passive"))
      (node (ref "CF2.3") (pin "18") (pinfunction "18_18") (pintype "passive"))
      (node (ref "CF2.4") (pin "17") (pinfunction "17_17") (pintype "passive"))
      (node (ref "CF2.4") (pin "18") (pinfunction "18_18") (pintype "passive"))
      (node (ref "CF3.2") (pin "17") (pinfunction "17_17") (pintype "passive"))
      (node (ref "CF3.2") (pin "18") (pinfunction "18_18") (pintype "passive"))
      (node (ref "CF4.2") (pin "17") (pinfunction "17_17") (pintype "passive"))
      (node (ref "CF4.2") (pin "18") (pinfunction "18_18") (pintype "passive"))
      (node (ref "CF5.2") (pin "17") (pinfunction "17_17") (pintype "passive"))
      (node (ref "CF5.2") (pin "18") (pinfunction "18_18") (pintype "passive"))
      (node (ref "CF6.2") (pin "17") (pinfunction "17_17") (pintype "passive"))
      (node (ref "CF6.2") (pin "18") (pinfunction "18_18") (pintype "passive"))
      (node (ref "CF7.2") (pin "17") (pinfunction "17_17") (pintype "passive"))
      (node (ref "CF7.2") (pin "18") (pinfunction "18_18") (pintype "passive"))
      (node (ref "CF8.2") (pin "17") (pinfunction "17_17") (pintype "passive"))
      (node (ref "CF8.2") (pin "18") (pinfunction "18_18") (pintype "passive"))
      (node (ref "R3") (pin "1") (pinfunction "1_1") (pintype "passive"))
      (node (ref "R7") (pin "1") (pinfunction "1_1") (pintype "passive"))
    )
    (net (code "14") (name "CAN2_L") (class "Default")
      (node (ref "CF12.2") (pin "19") (pinfunction "19_19") (pintype "passive"))
      (node (ref "CF12.2") (pin "20") (pinfunction "20_20") (pintype "passive"))
      (node (ref "CF13.2") (pin "19") (pinfunction "19_19") (pintype "passive"))
      (node (ref "CF13.2") (pin "20") (pinfunction "20_20") (pintype "passive"))
      (node (ref "CF14.2") (pin "19") (pinfunction "19_19") (pintype "passive"))
      (node (ref "CF14.2") (pin "20") (pinfunction "20_20") (pintype "passive"))
      (node (ref "CF15.2") (pin "19") (pinfunction "19_19") (pintype "passive"))
      (node (ref "CF15.2") (pin "20") (pinfunction "20_20") (pintype "passive"))
      (node (ref "CF16.2") (pin "19") (pinfunction "19_19") (pintype "passive"))
      (node (ref "CF16.2") (pin "20") (pinfunction "20_20") (pintype "passive"))
      (node (ref "CF17.2") (pin "19") (pinfunction "19_19") (pintype "passive"))
      (node (ref "CF17.2") (pin "20") (pinfunction "20_20") (pintype "passive"))
      (node (ref "CF18.2") (pin "19") (pinfunction "19_19") (pintype "passive"))
      (node (ref "CF18.2") (pin "20") (pinfunction "20_20") (pintype "passive"))
      (node (ref "CF19.2") (pin "19") (pinfunction "19_19") (pintype "passive"))
      (node (ref "CF19.2") (pin "20") (pinfunction "20_20") (pintype "passive"))
      (node (ref "CF2.2") (pin "19") (pinfunction "19_19") (pintype "passive"))
      (node (ref "CF2.2") (pin "20") (pinfunction "20_20") (pintype "passive"))
      (node (ref "CF2.3") (pin "19") (pinfunction "19_19") (pintype "passive"))
      (node (ref "CF2.3") (pin "20") (pinfunction "20_20") (pintype "passive"))
      (node (ref "CF2.4") (pin "19") (pinfunction "19_19") (pintype "passive"))
      (node (ref "CF2.4") (pin "20") (pinfunction "20_20") (pintype "passive"))
      (node (ref "CF3.2") (pin "19") (pinfunction "19_19") (pintype "passive"))
      (node (ref "CF3.2") (pin "20") (pinfunction "20_20") (pintype "passive"))
      (node (ref "CF4.2") (pin "19") (pinfunction "19_19") (pintype "passive"))
      (node (ref "CF4.2") (pin "20") (pinfunction "20_20") (pintype "passive"))
      (node (ref "CF5.2") (pin "19") (pinfunction "19_19") (pintype "passive"))
      (node (ref "CF5.2") (pin "20") (pinfunction "20_20") (pintype "passive"))
      (node (ref "CF6.2") (pin "19") (pinfunction "19_19") (pintype "passive"))
      (node (ref "CF6.2") (pin "20") (pinfunction "20_20") (pintype "passive"))
      (node (ref "CF7.2") (pin "19") (pinfunction "19_19") (pintype "passive"))
      (node (ref "CF7.2") (pin "20") (pinfunction "20_20") (pintype "passive"))
      (node (ref "CF8.2") (pin "19") (pinfunction "19_19") (pintype "passive"))
      (node (ref "CF8.2") (pin "20") (pinfunction "20_20") (pintype "passive"))
      (node (ref "R4") (pin "1") (pinfunction "1_1") (pintype "passive"))
      (node (ref "R8") (pin "1") (pinfunction "1_1") (pintype "passive"))
    )
    (net (code "15") (name "GND") (class "Default")
      (node (ref "C1") (pin "2") (pinfunction "2_2") (pintype "passive"))
      (node (ref "C2") (pin "2") (pinfunction "2_2") (pintype "passive"))
      (node (ref "C3") (pin "2") (pinfunction "2_2") (pintype "passive"))
      (node (ref "C4") (pin "2") (pinfunction "2_2") (pintype "passive"))
      (node (ref "CF12.1") (pin "LC1") (pinfunction "LC1_LC1") (pintype "passive"))
      (node (ref "CF12.1") (pin "LC2") (pinfunction "LC2_LC2") (pintype "passive"))
      (node (ref "CF12.2") (pin "27") (pinfunction "27_27") (pintype "passive"))
      (node (ref "CF12.2") (pin "28") (pinfunction "28_28") (pintype "passive"))
      (node (ref "CF12.2") (pin "29") (pinfunction "29_29") (pintype "passive"))
      (node (ref "CF12.2") (pin "30") (pinfunction "30_30") (pintype "passive"))
      (node (ref "CF12.2") (pin "31") (pinfunction "31_31") (pintype "passive"))
      (node (ref "CF12.2") (pin "32") (pinfunction "32_32") (pintype "passive"))
      (node (ref "CF12.2") (pin "37") (pinfunction "37_37") (pintype "passive"))
      (node (ref "CF12.2") (pin "38") (pinfunction "38_38") (pintype "passive"))
      (node (ref "CF12.2") (pin "LC1") (pinfunction "LC1_LC1") (pintype "passive"))
      (node (ref "CF12.2") (pin "LC2") (pinfunction "LC2_LC2") (pintype "passive"))
      (node (ref "CF13.1") (pin "LC1") (pinfunction "LC1_LC1") (pintype "passive"))
      (node (ref "CF13.1") (pin "LC2") (pinfunction "LC2_LC2") (pintype "passive"))
      (node (ref "CF13.2") (pin "27") (pinfunction "27_27") (pintype "passive"))
      (node (ref "CF13.2") (pin "28") (pinfunction "28_28") (pintype "passive"))
      (node (ref "CF13.2") (pin "29") (pinfunction "29_29") (pintype "passive"))
      (node (ref "CF13.2") (pin "30") (pinfunction "30_30") (pintype "passive"))
      (node (ref "CF13.2") (pin "31") (pinfunction "31_31") (pintype "passive"))
      (node (ref "CF13.2") (pin "32") (pinfunction "32_32") (pintype "passive"))
      (node (ref "CF13.2") (pin "37") (pinfunction "37_37") (pintype "passive"))
      (node (ref "CF13.2") (pin "38") (pinfunction "38_38") (pintype "passive"))
      (node (ref "CF13.2") (pin "LC1") (pinfunction "LC1_LC1") (pintype "passive"))
      (node (ref "CF13.2") (pin "LC2") (pinfunction "LC2_LC2") (pintype "passive"))
      (node (ref "CF14.1") (pin "LC1") (pinfunction "LC1_LC1") (pintype "passive"))
      (node (ref "CF14.1") (pin "LC2") (pinfunction "LC2_LC2") (pintype "passive"))
      (node (ref "CF14.2") (pin "27") (pinfunction "27_27") (pintype "passive"))
      (node (ref "CF14.2") (pin "28") (pinfunction "28_28") (pintype "passive"))
      (node (ref "CF14.2") (pin "29") (pinfunction "29_29") (pintype "passive"))
      (node (ref "CF14.2") (pin "30") (pinfunction "30_30") (pintype "passive"))
      (node (ref "CF14.2") (pin "31") (pinfunction "31_31") (pintype "passive"))
      (node (ref "CF14.2") (pin "32") (pinfunction "32_32") (pintype "passive"))
      (node (ref "CF14.2") (pin "37") (pinfunction "37_37") (pintype "passive"))
      (node (ref "CF14.2") (pin "38") (pinfunction "38_38") (pintype "passive"))
      (node (ref "CF14.2") (pin "LC1") (pinfunction "LC1_LC1") (pintype "passive"))
      (node (ref "CF14.2") (pin "LC2") (pinfunction "LC2_LC2") (pintype "passive"))
      (node (ref "CF15.1") (pin "LC1") (pinfunction "LC1_LC1") (pintype "passive"))
      (node (ref "CF15.1") (pin "LC2") (pinfunction "LC2_LC2") (pintype "passive"))
      (node (ref "CF15.2") (pin "27") (pinfunction "27_27") (pintype "passive"))
      (node (ref "CF15.2") (pin "28") (pinfunction "28_28") (pintype "passive"))
      (node (ref "CF15.2") (pin "29") (pinfunction "29_29") (pintype "passive"))
      (node (ref "CF15.2") (pin "30") (pinfunction "30_30") (pintype "passive"))
      (node (ref "CF15.2") (pin "31") (pinfunction "31_31") (pintype "passive"))
      (node (ref "CF15.2") (pin "32") (pinfunction "32_32") (pintype "passive"))
      (node (ref "CF15.2") (pin "37") (pinfunction "37_37") (pintype "passive"))
      (node (ref "CF15.2") (pin "38") (pinfunction "38_38") (pintype "passive"))
      (node (ref "CF15.2") (pin "LC1") (pinfunction "LC1_LC1") (pintype "passive"))
      (node (ref "CF15.2") (pin "LC2") (pinfunction "LC2_LC2") (pintype "passive"))
      (node (ref "CF16.1") (pin "LC1") (pinfunction "LC1_LC1") (pintype "passive"))
      (node (ref "CF16.1") (pin "LC2") (pinfunction "LC2_LC2") (pintype "passive"))
      (node (ref "CF16.2") (pin "27") (pinfunction "27_27") (pintype "passive"))
      (node (ref "CF16.2") (pin "28") (pinfunction "28_28") (pintype "passive"))
      (node (ref "CF16.2") (pin "29") (pinfunction "29_29") (pintype "passive"))
      (node (ref "CF16.2") (pin "30") (pinfunction "30_30") (pintype "passive"))
      (node (ref "CF16.2") (pin "31") (pinfunction "31_31") (pintype "passive"))
      (node (ref "CF16.2") (pin "32") (pinfunction "32_32") (pintype "passive"))
      (node (ref "CF16.2") (pin "37") (pinfunction "37_37") (pintype "passive"))
      (node (ref "CF16.2") (pin "38") (pinfunction "38_38") (pintype "passive"))
      (node (ref "CF16.2") (pin "LC1") (pinfunction "LC1_LC1") (pintype "passive"))
      (node (ref "CF16.2") (pin "LC2") (pinfunction "LC2_LC2") (pintype "passive"))
      (node (ref "CF17.1") (pin "LC1") (pinfunction "LC1_LC1") (pintype "passive"))
      (node (ref "CF17.1") (pin "LC2") (pinfunction "LC2_LC2") (pintype "passive"))
      (node (ref "CF17.2") (pin "27") (pinfunction "27_27") (pintype "passive"))
      (node (ref "CF17.2") (pin "28") (pinfunction "28_28") (pintype "passive"))
      (node (ref "CF17.2") (pin "29") (pinfunction "29_29") (pintype "passive"))
      (node (ref "CF17.2") (pin "30") (pinfunction "30_30") (pintype "passive"))
      (node (ref "CF17.2") (pin "31") (pinfunction "31_31") (pintype "passive"))
      (node (ref "CF17.2") (pin "32") (pinfunction "32_32") (pintype "passive"))
      (node (ref "CF17.2") (pin "37") (pinfunction "37_37") (pintype "passive"))
      (node (ref "CF17.2") (pin "38") (pinfunction "38_38") (pintype "passive"))
      (node (ref "CF17.2") (pin "LC1") (pinfunction "LC1_LC1") (pintype "passive"))
      (node (ref "CF17.2") (pin "LC2") (pinfunction "LC2_LC2") (pintype "passive"))
      (node (ref "CF18.1") (pin "LC1") (pinfunction "LC1_LC1") (pintype "passive"))
      (node (ref "CF18.1") (pin "LC2") (pinfunction "LC2_LC2") (pintype "passive"))
      (node (ref "CF18.2") (pin "27") (pinfunction "27_27") (pintype "passive"))
      (node (ref "CF18.2") (pin "28") (pinfunction "28_28") (pintype "passive"))
      (node (ref "CF18.2") (pin "29") (pinfunction "29_29") (pintype "passive"))
      (node (ref "CF18.2") (pin "30") (pinfunction "30_30") (pintype "passive"))
      (node (ref "CF18.2") (pin "31") (pinfunction "31_31") (pintype "passive"))
      (node (ref "CF18.2") (pin "32") (pinfunction "32_32") (pintype "passive"))
      (node (ref "CF18.2") (pin "37") (pinfunction "37_37") (pintype "passive"))
      (node (ref "CF18.2") (pin "38") (pinfunction "38_38") (pintype "passive"))
      (node (ref "CF18.2") (pin "LC1") (pinfunction "LC1_LC1") (pintype "passive"))
      (node (ref "CF18.2") (pin "LC2") (pinfunction "LC2_LC2") (pintype "passive"))
      (node (ref "CF19.1") (pin "LC1") (pinfunction "LC1_LC1") (pintype "passive"))
      (node (ref "CF19.1") (pin "LC2") (pinfunction "LC2_LC2") (pintype "passive"))
      (node (ref "CF19.2") (pin "27") (pinfunction "27_27") (pintype "passive"))
      (node (ref "CF19.2") (pin "28") (pinfunction "28_28") (pintype "passive"))
      (node (ref "CF19.2") (pin "29") (pinfunction "29_29") (pintype "passive"))
      (node (ref "CF19.2") (pin "30") (pinfunction "30_30") (pintype "passive"))
      (node (ref "CF19.2") (pin "31") (pinfunction "31_31") (pintype "passive"))
      (node (ref "CF19.2") (pin "32") (pinfunction "32_32") (pintype "passive"))
      (node (ref "CF19.2") (pin "37") (pinfunction "37_37") (pintype "passive"))
      (node (ref "CF19.2") (pin "38") (pinfunction "38_38") (pintype "passive"))
      (node (ref "CF19.2") (pin "LC1") (pinfunction "LC1_LC1") (pintype "passive"))
      (node (ref "CF19.2") (pin "LC2") (pinfunction "LC2_LC2") (pintype "passive"))
      (node (ref "CF2.1") (pin "LC1") (pinfunction "LC1_LC1") (pintype "passive"))
      (node (ref "CF2.1") (pin "LC2") (pinfunction "LC2_LC2") (pintype "passive"))
      (node (ref "CF2.2") (pin "27") (pinfunction "27_27") (pintype "passive"))
      (node (ref "CF2.2") (pin "28") (pinfunction "28_28") (pintype "passive"))
      (node (ref "CF2.2") (pin "29") (pinfunction "29_29") (pintype "passive"))
      (node (ref "CF2.2") (pin "30") (pinfunction "30_30") (pintype "passive"))
      (node (ref "CF2.2") (pin "31") (pinfunction "31_31") (pintype "passive"))
      (node (ref "CF2.2") (pin "32") (pinfunction "32_32") (pintype "passive"))
      (node (ref "CF2.2") (pin "37") (pinfunction "37_37") (pintype "passive"))
      (node (ref "CF2.2") (pin "38") (pinfunction "38_38") (pintype "passive"))
      (node (ref "CF2.2") (pin "LC1") (pinfunction "LC1_LC1") (pintype "passive"))
      (node (ref "CF2.2") (pin "LC2") (pinfunction "LC2_LC2") (pintype "passive"))
      (node (ref "CF2.3") (pin "27") (pinfunction "27_27") (pintype "passive"))
      (node (ref "CF2.3") (pin "28") (pinfunction "28_28") (pintype "passive"))
      (node (ref "CF2.3") (pin "29") (pinfunction "29_29") (pintype "passive"))
      (node (ref "CF2.3") (pin "30") (pinfunction "30_30") (pintype "passive"))
      (node (ref "CF2.3") (pin "31") (pinfunction "31_31") (pintype "passive"))
      (node (ref "CF2.3") (pin "32") (pinfunction "32_32") (pintype "passive"))
      (node (ref "CF2.3") (pin "37") (pinfunction "37_37") (pintype "passive"))
      (node (ref "CF2.3") (pin "38") (pinfunction "38_38") (pintype "passive"))
      (node (ref "CF2.3") (pin "LC1") (pinfunction "LC1_LC1") (pintype "passive"))
      (node (ref "CF2.3") (pin "LC2") (pinfunction "LC2_LC2") (pintype "passive"))
      (node (ref "CF2.4") (pin "27") (pinfunction "27_27") (pintype "passive"))
      (node (ref "CF2.4") (pin "28") (pinfunction "28_28") (pintype "passive"))
      (node (ref "CF2.4") (pin "29") (pinfunction "29_29") (pintype "passive"))
      (node (ref "CF2.4") (pin "30") (pinfunction "30_30") (pintype "passive"))
      (node (ref "CF2.4") (pin "31") (pinfunction "31_31") (pintype "passive"))
      (node (ref "CF2.4") (pin "32") (pinfunction "32_32") (pintype "passive"))
      (node (ref "CF2.4") (pin "37") (pinfunction "37_37") (pintype "passive"))
      (node (ref "CF2.4") (pin "38") (pinfunction "38_38") (pintype "passive"))
      (node (ref "CF2.4") (pin "LC1") (pinfunction "LC1_LC1") (pintype "passive"))
      (node (ref "CF2.4") (pin "LC2") (pinfunction "LC2_LC2") (pintype "passive"))
      (node (ref "CF3.1") (pin "LC1") (pinfunction "LC1_LC1") (pintype "passive"))
      (node (ref "CF3.1") (pin "LC2") (pinfunction "LC2_LC2") (pintype "passive"))
      (node (ref "CF3.2") (pin "27") (pinfunction "27_27") (pintype "passive"))
      (node (ref "CF3.2") (pin "28") (pinfunction "28_28") (pintype "passive"))
      (node (ref "CF3.2") (pin "29") (pinfunction "29_29") (pintype "passive"))
      (node (ref "CF3.2") (pin "30") (pinfunction "30_30") (pintype "passive"))
      (node (ref "CF3.2") (pin "31") (pinfunction "31_31") (pintype "passive"))
      (node (ref "CF3.2") (pin "32") (pinfunction "32_32") (pintype "passive"))
      (node (ref "CF3.2") (pin "37") (pinfunction "37_37") (pintype "passive"))
      (node (ref "CF3.2") (pin "38") (pinfunction "38_38") (pintype "passive"))
      (node (ref "CF3.2") (pin "LC1") (pinfunction "LC1_LC1") (pintype "passive"))
      (node (ref "CF3.2") (pin "LC2") (pinfunction "LC2_LC2") (pintype "passive"))
      (node (ref "CF4.1") (pin "LC1") (pinfunction "LC1_LC1") (pintype "passive"))
      (node (ref "CF4.1") (pin "LC2") (pinfunction "LC2_LC2") (pintype "passive"))
      (node (ref "CF4.2") (pin "27") (pinfunction "27_27") (pintype "passive"))
      (node (ref "CF4.2") (pin "28") (pinfunction "28_28") (pintype "passive"))
      (node (ref "CF4.2") (pin "29") (pinfunction "29_29") (pintype "passive"))
      (node (ref "CF4.2") (pin "30") (pinfunction "30_30") (pintype "passive"))
      (node (ref "CF4.2") (pin "31") (pinfunction "31_31") (pintype "passive"))
      (node (ref "CF4.2") (pin "32") (pinfunction "32_32") (pintype "passive"))
      (node (ref "CF4.2") (pin "37") (pinfunction "37_37") (pintype "passive"))
      (node (ref "CF4.2") (pin "38") (pinfunction "38_38") (pintype "passive"))
      (node (ref "CF4.2") (pin "LC1") (pinfunction "LC1_LC1") (pintype "passive"))
      (node (ref "CF4.2") (pin "LC2") (pinfunction "LC2_LC2") (pintype "passive"))
      (node (ref "CF5.1") (pin "LC1") (pinfunction "LC1_LC1") (pintype "passive"))
      (node (ref "CF5.1") (pin "LC2") (pinfunction "LC2_LC2") (pintype "passive"))
      (node (ref "CF5.2") (pin "27") (pinfunction "27_27") (pintype "passive"))
      (node (ref "CF5.2") (pin "28") (pinfunction "28_28") (pintype "passive"))
      (node (ref "CF5.2") (pin "29") (pinfunction "29_29") (pintype "passive"))
      (node (ref "CF5.2") (pin "30") (pinfunction "30_30") (pintype "passive"))
      (node (ref "CF5.2") (pin "31") (pinfunction "31_31") (pintype "passive"))
      (node (ref "CF5.2") (pin "32") (pinfunction "32_32") (pintype "passive"))
      (node (ref "CF5.2") (pin "37") (pinfunction "37_37") (pintype "passive"))
      (node (ref "CF5.2") (pin "38") (pinfunction "38_38") (pintype "passive"))
      (node (ref "CF5.2") (pin "LC1") (pinfunction "LC1_LC1") (pintype "passive"))
      (node (ref "CF5.2") (pin "LC2") (pinfunction "LC2_LC2") (pintype "passive"))
      (node (ref "CF6.1") (pin "LC1") (pinfunction "LC1_LC1") (pintype "passive"))
      (node (ref "CF6.1") (pin "LC2") (pinfunction "LC2_LC2") (pintype "passive"))
      (node (ref "CF6.2") (pin "27") (pinfunction "27_27") (pintype "passive"))
      (node (ref "CF6.2") (pin "28") (pinfunction "28_28") (pintype "passive"))
      (node (ref "CF6.2") (pin "29") (pinfunction "29_29") (pintype "passive"))
      (node (ref "CF6.2") (pin "30") (pinfunction "30_30") (pintype "passive"))
      (node (ref "CF6.2") (pin "31") (pinfunction "31_31") (pintype "passive"))
      (node (ref "CF6.2") (pin "32") (pinfunction "32_32") (pintype "passive"))
      (node (ref "CF6.2") (pin "37") (pinfunction "37_37") (pintype "passive"))
      (node (ref "CF6.2") (pin "38") (pinfunction "38_38") (pintype "passive"))
      (node (ref "CF6.2") (pin "LC1") (pinfunction "LC1_LC1") (pintype "passive"))
      (node (ref "CF6.2") (pin "LC2") (pinfunction "LC2_LC2") (pintype "passive"))
      (node (ref "CF7.1") (pin "LC1") (pinfunction "LC1_LC1") (pintype "passive"))
      (node (ref "CF7.1") (pin "LC2") (pinfunction "LC2_LC2") (pintype "passive"))
      (node (ref "CF7.2") (pin "27") (pinfunction "27_27") (pintype "passive"))
      (node (ref "CF7.2") (pin "28") (pinfunction "28_28") (pintype "passive"))
      (node (ref "CF7.2") (pin "29") (pinfunction "29_29") (pintype "passive"))
      (node (ref "CF7.2") (pin "30") (pinfunction "30_30") (pintype "passive"))
      (node (ref "CF7.2") (pin "31") (pinfunction "31_31") (pintype "passive"))
      (node (ref "CF7.2") (pin "32") (pinfunction "32_32") (pintype "passive"))
      (node (ref "CF7.2") (pin "37") (pinfunction "37_37") (pintype "passive"))
      (node (ref "CF7.2") (pin "38") (pinfunction "38_38") (pintype "passive"))
      (node (ref "CF7.2") (pin "LC1") (pinfunction "LC1_LC1") (pintype "passive"))
      (node (ref "CF7.2") (pin "LC2") (pinfunction "LC2_LC2") (pintype "passive"))
      (node (ref "CF8.1") (pin "LC1") (pinfunction "LC1_LC1") (pintype "passive"))
      (node (ref "CF8.1") (pin "LC2") (pinfunction "LC2_LC2") (pintype "passive"))
      (node (ref "CF8.2") (pin "27") (pinfunction "27_27") (pintype "passive"))
      (node (ref "CF8.2") (pin "28") (pinfunction "28_28") (pintype "passive"))
      (node (ref "CF8.2") (pin "29") (pinfunction "29_29") (pintype "passive"))
      (node (ref "CF8.2") (pin "30") (pinfunction "30_30") (pintype "passive"))
      (node (ref "CF8.2") (pin "31") (pinfunction "31_31") (pintype "passive"))
      (node (ref "CF8.2") (pin "32") (pinfunction "32_32") (pintype "passive"))
      (node (ref "CF8.2") (pin "37") (pinfunction "37_37") (pintype "passive"))
      (node (ref "CF8.2") (pin "38") (pinfunction "38_38") (pintype "passive"))
      (node (ref "CF8.2") (pin "LC1") (pinfunction "LC1_LC1") (pintype "passive"))
      (node (ref "CF8.2") (pin "LC2") (pinfunction "LC2_LC2") (pintype "passive"))
      (node (ref "CM1.1") (pin "P$1") (pinfunction "SHIELD1_P$1") (pintype "passive"))
      (node (ref "CM1.1") (pin "P$2") (pinfunction "SHIELD1_P$2") (pintype "passive"))
      (node (ref "CM1.1") (pin "P$3") (pinfunction "SHIELD1_P$3") (pintype "passive"))
      (node (ref "CM1.1") (pin "P$4") (pinfunction "SHIELD1_P$4") (pintype "passive"))
      (node (ref "CM2.1") (pin "P$1") (pinfunction "SHIELD1_P$1") (pintype "passive"))
      (node (ref "CM2.1") (pin "P$2") (pinfunction "SHIELD1_P$2") (pintype "passive"))
      (node (ref "CM2.1") (pin "P$3") (pinfunction "SHIELD1_P$3") (pintype "passive"))
      (node (ref "CM2.1") (pin "P$4") (pinfunction "SHIELD1_P$4") (pintype "passive"))
      (node (ref "CM2.2") (pin "P$1") (pinfunction "SHIELD1_P$1") (pintype "passive"))
      (node (ref "CM2.2") (pin "P$2") (pinfunction "SHIELD1_P$2") (pintype "passive"))
      (node (ref "CM2.2") (pin "P$3") (pinfunction "SHIELD1_P$3") (pintype "passive"))
      (node (ref "CM2.2") (pin "P$4") (pinfunction "SHIELD1_P$4") (pintype "passive"))
      (node (ref "CM20.1") (pin "P$1") (pinfunction "SHIELD1_P$1") (pintype "passive"))
      (node (ref "CM20.1") (pin "P$2") (pinfunction "SHIELD1_P$2") (pintype "passive"))
      (node (ref "CM20.1") (pin "P$3") (pinfunction "SHIELD1_P$3") (pintype "passive"))
      (node (ref "CM20.1") (pin "P$4") (pinfunction "SHIELD1_P$4") (pintype "passive"))
      (node (ref "CM20.2") (pin "P$1") (pinfunction "SHIELD1_P$1") (pintype "passive"))
      (node (ref "CM20.2") (pin "P$2") (pinfunction "SHIELD1_P$2") (pintype "passive"))
      (node (ref "CM20.2") (pin "P$3") (pinfunction "SHIELD1_P$3") (pintype "passive"))
      (node (ref "CM20.2") (pin "P$4") (pinfunction "SHIELD1_P$4") (pintype "passive"))
      (node (ref "CM20.3") (pin "P$1") (pinfunction "SHIELD1_P$1") (pintype "passive"))
      (node (ref "CM20.3") (pin "P$2") (pinfunction "SHIELD1_P$2") (pintype "passive"))
      (node (ref "CM20.3") (pin "P$3") (pinfunction "SHIELD1_P$3") (pintype "passive"))
      (node (ref "CM20.3") (pin "P$4") (pinfunction "SHIELD1_P$4") (pintype "passive"))
      (node (ref "CM3.2") (pin "P$1") (pinfunction "SHIELD1_P$1") (pintype "passive"))
      (node (ref "CM3.2") (pin "P$2") (pinfunction "SHIELD1_P$2") (pintype "passive"))
      (node (ref "CM3.2") (pin "P$3") (pinfunction "SHIELD1_P$3") (pintype "passive"))
      (node (ref "CM3.2") (pin "P$4") (pinfunction "SHIELD1_P$4") (pintype "passive"))
      (node (ref "CM4.1") (pin "P$1") (pinfunction "SHIELD1_P$1") (pintype "passive"))
      (node (ref "CM4.1") (pin "P$2") (pinfunction "SHIELD1_P$2") (pintype "passive"))
      (node (ref "CM4.1") (pin "P$3") (pinfunction "SHIELD1_P$3") (pintype "passive"))
      (node (ref "CM4.1") (pin "P$4") (pinfunction "SHIELD1_P$4") (pintype "passive"))
      (node (ref "CM4.2") (pin "P$1") (pinfunction "SHIELD1_P$1") (pintype "passive"))
      (node (ref "CM4.2") (pin "P$2") (pinfunction "SHIELD1_P$2") (pintype "passive"))
      (node (ref "CM4.2") (pin "P$3") (pinfunction "SHIELD1_P$3") (pintype "passive"))
      (node (ref "CM4.2") (pin "P$4") (pinfunction "SHIELD1_P$4") (pintype "passive"))
      (node (ref "CM4.3") (pin "P$1") (pinfunction "SHIELD1_P$1") (pintype "passive"))
      (node (ref "CM4.3") (pin "P$2") (pinfunction "SHIELD1_P$2") (pintype "passive"))
      (node (ref "CM4.3") (pin "P$3") (pinfunction "SHIELD1_P$3") (pintype "passive"))
      (node (ref "CM4.3") (pin "P$4") (pinfunction "SHIELD1_P$4") (pintype "passive"))
    )
    (net (code "16") (name "L-GPS") (class "Default")
      (node (ref "CM3.2") (pin "RF-DOWN") (pinfunction "RF_RF-DOWN") (pintype "passive"))
      (node (ref "CM4.1") (pin "RF-DOWN") (pinfunction "RF_RF-DOWN") (pintype "passive"))
    )
    (net (code "17") (name "L-TURNSTILE") (class "Default")
      (node (ref "CM20.1") (pin "RF-DOWN") (pinfunction "RF_RF-DOWN") (pintype "passive"))
      (node (ref "CM4.2") (pin "RF-DOWN") (pinfunction "RF_RF-DOWN") (pintype "passive"))
    )
    (net (code "18") (name "Net-(C1-Pad1)") (class "Default")
      (node (ref "C1") (pin "1") (pinfunction "1_1") (pintype "passive"))
      (node (ref "R1") (pin "2") (pinfunction "2_2") (pintype "passive"))
      (node (ref "R2") (pin "2") (pinfunction "2_2") (pintype "passive"))
    )
    (net (code "19") (name "Net-(C2-Pad1)") (class "Default")
      (node (ref "C2") (pin "1") (pinfunction "1_1") (pintype "passive"))
      (node (ref "R3") (pin "2") (pinfunction "2_2") (pintype "passive"))
      (node (ref "R4") (pin "2") (pinfunction "2_2") (pintype "passive"))
    )
    (net (code "20") (name "Net-(C3-Pad1)") (class "Default")
      (node (ref "C3") (pin "1") (pinfunction "1_1") (pintype "passive"))
      (node (ref "R5") (pin "2") (pinfunction "2_2") (pintype "passive"))
      (node (ref "R6") (pin "2") (pinfunction "2_2") (pintype "passive"))
    )
    (net (code "21") (name "Net-(C4-Pad1)") (class "Default")
      (node (ref "C4") (pin "1") (pinfunction "1_1") (pintype "passive"))
      (node (ref "R7") (pin "2") (pinfunction "2_2") (pintype "passive"))
      (node (ref "R8") (pin "2") (pinfunction "2_2") (pintype "passive"))
    )
    (net (code "22") (name "OPD_PWR") (class "Default")
      (node (ref "CF12.2") (pin "15") (pinfunction "15_15") (pintype "passive"))
      (node (ref "CF12.2") (pin "16") (pinfunction "16_16") (pintype "passive"))
      (node (ref "CF13.2") (pin "15") (pinfunction "15_15") (pintype "passive"))
      (node (ref "CF13.2") (pin "16") (pinfunction "16_16") (pintype "passive"))
      (node (ref "CF14.2") (pin "15") (pinfunction "15_15") (pintype "passive"))
      (node (ref "CF14.2") (pin "16") (pinfunction "16_16") (pintype "passive"))
      (node (ref "CF15.2") (pin "15") (pinfunction "15_15") (pintype "passive"))
      (node (ref "CF15.2") (pin "16") (pinfunction "16_16") (pintype "passive"))
      (node (ref "CF16.2") (pin "15") (pinfunction "15_15") (pintype "passive"))
      (node (ref "CF16.2") (pin "16") (pinfunction "16_16") (pintype "passive"))
      (node (ref "CF17.2") (pin "15") (pinfunction "15_15") (pintype "passive"))
      (node (ref "CF17.2") (pin "16") (pinfunction "16_16") (pintype "passive"))
      (node (ref "CF18.2") (pin "15") (pinfunction "15_15") (pintype "passive"))
      (node (ref "CF18.2") (pin "16") (pinfunction "16_16") (pintype "passive"))
      (node (ref "CF19.2") (pin "15") (pinfunction "15_15") (pintype "passive"))
      (node (ref "CF19.2") (pin "16") (pinfunction "16_16") (pintype "passive"))
      (node (ref "CF2.2") (pin "15") (pinfunction "15_15") (pintype "passive"))
      (node (ref "CF2.2") (pin "16") (pinfunction "16_16") (pintype "passive"))
      (node (ref "CF2.3") (pin "15") (pinfunction "15_15") (pintype "passive"))
      (node (ref "CF2.3") (pin "16") (pinfunction "16_16") (pintype "passive"))
      (node (ref "CF2.4") (pin "15") (pinfunction "15_15") (pintype "passive"))
      (node (ref "CF2.4") (pin "16") (pinfunction "16_16") (pintype "passive"))
      (node (ref "CF3.2") (pin "15") (pinfunction "15_15") (pintype "passive"))
      (node (ref "CF3.2") (pin "16") (pinfunction "16_16") (pintype "passive"))
      (node (ref "CF4.2") (pin "15") (pinfunction "15_15") (pintype "passive"))
      (node (ref "CF4.2") (pin "16") (pinfunction "16_16") (pintype "passive"))
      (node (ref "CF5.2") (pin "15") (pinfunction "15_15") (pintype "passive"))
      (node (ref "CF5.2") (pin "16") (pinfunction "16_16") (pintype "passive"))
      (node (ref "CF6.2") (pin "15") (pinfunction "15_15") (pintype "passive"))
      (node (ref "CF6.2") (pin "16") (pinfunction "16_16") (pintype "passive"))
      (node (ref "CF7.2") (pin "15") (pinfunction "15_15") (pintype "passive"))
      (node (ref "CF7.2") (pin "16") (pinfunction "16_16") (pintype "passive"))
      (node (ref "CF8.2") (pin "15") (pinfunction "15_15") (pintype "passive"))
      (node (ref "CF8.2") (pin "16") (pinfunction "16_16") (pintype "passive"))
    )
    (net (code "23") (name "OPD_SCL") (class "Default")
      (node (ref "CF12.2") (pin "13") (pinfunction "13_13") (pintype "passive"))
      (node (ref "CF12.2") (pin "14") (pinfunction "14_14") (pintype "passive"))
      (node (ref "CF13.2") (pin "13") (pinfunction "13_13") (pintype "passive"))
      (node (ref "CF13.2") (pin "14") (pinfunction "14_14") (pintype "passive"))
      (node (ref "CF14.2") (pin "13") (pinfunction "13_13") (pintype "passive"))
      (node (ref "CF14.2") (pin "14") (pinfunction "14_14") (pintype "passive"))
      (node (ref "CF15.2") (pin "13") (pinfunction "13_13") (pintype "passive"))
      (node (ref "CF15.2") (pin "14") (pinfunction "14_14") (pintype "passive"))
      (node (ref "CF16.2") (pin "13") (pinfunction "13_13") (pintype "passive"))
      (node (ref "CF16.2") (pin "14") (pinfunction "14_14") (pintype "passive"))
      (node (ref "CF17.2") (pin "13") (pinfunction "13_13") (pintype "passive"))
      (node (ref "CF17.2") (pin "14") (pinfunction "14_14") (pintype "passive"))
      (node (ref "CF18.2") (pin "13") (pinfunction "13_13") (pintype "passive"))
      (node (ref "CF18.2") (pin "14") (pinfunction "14_14") (pintype "passive"))
      (node (ref "CF19.2") (pin "13") (pinfunction "13_13") (pintype "passive"))
      (node (ref "CF19.2") (pin "14") (pinfunction "14_14") (pintype "passive"))
      (node (ref "CF2.2") (pin "13") (pinfunction "13_13") (pintype "passive"))
      (node (ref "CF2.2") (pin "14") (pinfunction "14_14") (pintype "passive"))
      (node (ref "CF2.3") (pin "13") (pinfunction "13_13") (pintype "passive"))
      (node (ref "CF2.3") (pin "14") (pinfunction "14_14") (pintype "passive"))
      (node (ref "CF2.4") (pin "13") (pinfunction "13_13") (pintype "passive"))
      (node (ref "CF2.4") (pin "14") (pinfunction "14_14") (pintype "passive"))
      (node (ref "CF3.2") (pin "13") (pinfunction "13_13") (pintype "passive"))
      (node (ref "CF3.2") (pin "14") (pinfunction "14_14") (pintype "passive"))
      (node (ref "CF4.2") (pin "13") (pinfunction "13_13") (pintype "passive"))
      (node (ref "CF4.2") (pin "14") (pinfunction "14_14") (pintype "passive"))
      (node (ref "CF5.2") (pin "13") (pinfunction "13_13") (pintype "passive"))
      (node (ref "CF5.2") (pin "14") (pinfunction "14_14") (pintype "passive"))
      (node (ref "CF6.2") (pin "13") (pinfunction "13_13") (pintype "passive"))
      (node (ref "CF6.2") (pin "14") (pinfunction "14_14") (pintype "passive"))
      (node (ref "CF7.2") (pin "13") (pinfunction "13_13") (pintype "passive"))
      (node (ref "CF7.2") (pin "14") (pinfunction "14_14") (pintype "passive"))
      (node (ref "CF8.2") (pin "13") (pinfunction "13_13") (pintype "passive"))
      (node (ref "CF8.2") (pin "14") (pinfunction "14_14") (pintype "passive"))
    )
    (net (code "24") (name "OPD_SDA") (class "Default")
      (node (ref "CF12.2") (pin "11") (pinfunction "11_11") (pintype "passive"))
      (node (ref "CF12.2") (pin "12") (pinfunction "12_12") (pintype "passive"))
      (node (ref "CF13.2") (pin "11") (pinfunction "11_11") (pintype "passive"))
      (node (ref "CF13.2") (pin "12") (pinfunction "12_12") (pintype "passive"))
      (node (ref "CF14.2") (pin "11") (pinfunction "11_11") (pintype "passive"))
      (node (ref "CF14.2") (pin "12") (pinfunction "12_12") (pintype "passive"))
      (node (ref "CF15.2") (pin "11") (pinfunction "11_11") (pintype "passive"))
      (node (ref "CF15.2") (pin "12") (pinfunction "12_12") (pintype "passive"))
      (node (ref "CF16.2") (pin "11") (pinfunction "11_11") (pintype "passive"))
      (node (ref "CF16.2") (pin "12") (pinfunction "12_12") (pintype "passive"))
      (node (ref "CF17.2") (pin "11") (pinfunction "11_11") (pintype "passive"))
      (node (ref "CF17.2") (pin "12") (pinfunction "12_12") (pintype "passive"))
      (node (ref "CF18.2") (pin "11") (pinfunction "11_11") (pintype "passive"))
      (node (ref "CF18.2") (pin "12") (pinfunction "12_12") (pintype "passive"))
      (node (ref "CF19.2") (pin "11") (pinfunction "11_11") (pintype "passive"))
      (node (ref "CF19.2") (pin "12") (pinfunction "12_12") (pintype "passive"))
      (node (ref "CF2.2") (pin "11") (pinfunction "11_11") (pintype "passive"))
      (node (ref "CF2.2") (pin "12") (pinfunction "12_12") (pintype "passive"))
      (node (ref "CF2.3") (pin "11") (pinfunction "11_11") (pintype "passive"))
      (node (ref "CF2.3") (pin "12") (pinfunction "12_12") (pintype "passive"))
      (node (ref "CF2.4") (pin "11") (pinfunction "11_11") (pintype "passive"))
      (node (ref "CF2.4") (pin "12") (pinfunction "12_12") (pintype "passive"))
      (node (ref "CF3.2") (pin "11") (pinfunction "11_11") (pintype "passive"))
      (node (ref "CF3.2") (pin "12") (pinfunction "12_12") (pintype "passive"))
      (node (ref "CF4.2") (pin "11") (pinfunction "11_11") (pintype "passive"))
      (node (ref "CF4.2") (pin "12") (pinfunction "12_12") (pintype "passive"))
      (node (ref "CF5.2") (pin "11") (pinfunction "11_11") (pintype "passive"))
      (node (ref "CF5.2") (pin "12") (pinfunction "12_12") (pintype "passive"))
      (node (ref "CF6.2") (pin "11") (pinfunction "11_11") (pintype "passive"))
      (node (ref "CF6.2") (pin "12") (pinfunction "12_12") (pintype "passive"))
      (node (ref "CF7.2") (pin "11") (pinfunction "11_11") (pintype "passive"))
      (node (ref "CF7.2") (pin "12") (pinfunction "12_12") (pintype "passive"))
      (node (ref "CF8.2") (pin "11") (pinfunction "11_11") (pintype "passive"))
      (node (ref "CF8.2") (pin "12") (pinfunction "12_12") (pintype "passive"))
    )
    (net (code "25") (name "S-HELICAL") (class "Default")
      (node (ref "CM1.1") (pin "RF-DOWN") (pinfunction "RF_RF-DOWN") (pintype "passive"))
      (node (ref "CM2.2") (pin "RF-DOWN") (pinfunction "RF_RF-DOWN") (pintype "passive"))
    )
    (net (code "26") (name "S-TURNSTILE") (class "Default")
      (node (ref "CM2.1") (pin "RF-DOWN") (pinfunction "RF_RF-DOWN") (pintype "passive"))
      (node (ref "CM20.3") (pin "RF-DOWN") (pinfunction "RF_RF-DOWN") (pintype "passive"))
    )
    (net (code "27") (name "SPARE1") (class "Default")
      (node (ref "CF12.2") (pin "10") (pinfunction "10_10") (pintype "passive"))
      (node (ref "CF12.2") (pin "9") (pinfunction "9_9") (pintype "passive"))
      (node (ref "CF13.2") (pin "10") (pinfunction "10_10") (pintype "passive"))
      (node (ref "CF13.2") (pin "9") (pinfunction "9_9") (pintype "passive"))
      (node (ref "CF14.2") (pin "10") (pinfunction "10_10") (pintype "passive"))
      (node (ref "CF14.2") (pin "9") (pinfunction "9_9") (pintype "passive"))
      (node (ref "CF15.2") (pin "10") (pinfunction "10_10") (pintype "passive"))
      (node (ref "CF15.2") (pin "9") (pinfunction "9_9") (pintype "passive"))
      (node (ref "CF16.2") (pin "10") (pinfunction "10_10") (pintype "passive"))
      (node (ref "CF16.2") (pin "9") (pinfunction "9_9") (pintype "passive"))
      (node (ref "CF17.2") (pin "10") (pinfunction "10_10") (pintype "passive"))
      (node (ref "CF17.2") (pin "9") (pinfunction "9_9") (pintype "passive"))
      (node (ref "CF18.2") (pin "10") (pinfunction "10_10") (pintype "passive"))
      (node (ref "CF18.2") (pin "9") (pinfunction "9_9") (pintype "passive"))
      (node (ref "CF19.2") (pin "10") (pinfunction "10_10") (pintype "passive"))
      (node (ref "CF19.2") (pin "9") (pinfunction "9_9") (pintype "passive"))
      (node (ref "CF2.2") (pin "10") (pinfunction "10_10") (pintype "passive"))
      (node (ref "CF2.2") (pin "9") (pinfunction "9_9") (pintype "passive"))
      (node (ref "CF2.3") (pin "10") (pinfunction "10_10") (pintype "passive"))
      (node (ref "CF2.3") (pin "9") (pinfunction "9_9") (pintype "passive"))
      (node (ref "CF2.4") (pin "10") (pinfunction "10_10") (pintype "passive"))
      (node (ref "CF2.4") (pin "9") (pinfunction "9_9") (pintype "passive"))
      (node (ref "CF3.2") (pin "10") (pinfunction "10_10") (pintype "passive"))
      (node (ref "CF3.2") (pin "9") (pinfunction "9_9") (pintype "passive"))
      (node (ref "CF4.2") (pin "10") (pinfunction "10_10") (pintype "passive"))
      (node (ref "CF4.2") (pin "9") (pinfunction "9_9") (pintype "passive"))
      (node (ref "CF5.2") (pin "10") (pinfunction "10_10") (pintype "passive"))
      (node (ref "CF5.2") (pin "9") (pinfunction "9_9") (pintype "passive"))
      (node (ref "CF6.2") (pin "10") (pinfunction "10_10") (pintype "passive"))
      (node (ref "CF6.2") (pin "9") (pinfunction "9_9") (pintype "passive"))
      (node (ref "CF7.2") (pin "10") (pinfunction "10_10") (pintype "passive"))
      (node (ref "CF7.2") (pin "9") (pinfunction "9_9") (pintype "passive"))
      (node (ref "CF8.2") (pin "10") (pinfunction "10_10") (pintype "passive"))
      (node (ref "CF8.2") (pin "9") (pinfunction "9_9") (pintype "passive"))
    )
    (net (code "28") (name "SPARE2") (class "Default")
      (node (ref "CF12.2") (pin "7") (pinfunction "7_7") (pintype "passive"))
      (node (ref "CF12.2") (pin "8") (pinfunction "8_8") (pintype "passive"))
      (node (ref "CF13.2") (pin "7") (pinfunction "7_7") (pintype "passive"))
      (node (ref "CF13.2") (pin "8") (pinfunction "8_8") (pintype "passive"))
      (node (ref "CF14.2") (pin "7") (pinfunction "7_7") (pintype "passive"))
      (node (ref "CF14.2") (pin "8") (pinfunction "8_8") (pintype "passive"))
      (node (ref "CF15.2") (pin "7") (pinfunction "7_7") (pintype "passive"))
      (node (ref "CF15.2") (pin "8") (pinfunction "8_8") (pintype "passive"))
      (node (ref "CF16.2") (pin "7") (pinfunction "7_7") (pintype "passive"))
      (node (ref "CF16.2") (pin "8") (pinfunction "8_8") (pintype "passive"))
      (node (ref "CF17.2") (pin "7") (pinfunction "7_7") (pintype "passive"))
      (node (ref "CF17.2") (pin "8") (pinfunction "8_8") (pintype "passive"))
      (node (ref "CF18.2") (pin "7") (pinfunction "7_7") (pintype "passive"))
      (node (ref "CF18.2") (pin "8") (pinfunction "8_8") (pintype "passive"))
      (node (ref "CF19.2") (pin "7") (pinfunction "7_7") (pintype "passive"))
      (node (ref "CF19.2") (pin "8") (pinfunction "8_8") (pintype "passive"))
      (node (ref "CF2.2") (pin "7") (pinfunction "7_7") (pintype "passive"))
      (node (ref "CF2.2") (pin "8") (pinfunction "8_8") (pintype "passive"))
      (node (ref "CF2.3") (pin "7") (pinfunction "7_7") (pintype "passive"))
      (node (ref "CF2.3") (pin "8") (pinfunction "8_8") (pintype "passive"))
      (node (ref "CF2.4") (pin "7") (pinfunction "7_7") (pintype "passive"))
      (node (ref "CF2.4") (pin "8") (pinfunction "8_8") (pintype "passive"))
      (node (ref "CF3.2") (pin "7") (pinfunction "7_7") (pintype "passive"))
      (node (ref "CF3.2") (pin "8") (pinfunction "8_8") (pintype "passive"))
      (node (ref "CF4.2") (pin "7") (pinfunction "7_7") (pintype "passive"))
      (node (ref "CF4.2") (pin "8") (pinfunction "8_8") (pintype "passive"))
      (node (ref "CF5.2") (pin "7") (pinfunction "7_7") (pintype "passive"))
      (node (ref "CF5.2") (pin "8") (pinfunction "8_8") (pintype "passive"))
      (node (ref "CF6.2") (pin "7") (pinfunction "7_7") (pintype "passive"))
      (node (ref "CF6.2") (pin "8") (pinfunction "8_8") (pintype "passive"))
      (node (ref "CF7.2") (pin "7") (pinfunction "7_7") (pintype "passive"))
      (node (ref "CF7.2") (pin "8") (pinfunction "8_8") (pintype "passive"))
      (node (ref "CF8.2") (pin "7") (pinfunction "7_7") (pintype "passive"))
      (node (ref "CF8.2") (pin "8") (pinfunction "8_8") (pintype "passive"))
    )
    (net (code "29") (name "SPARE3") (class "Default")
      (node (ref "CF12.2") (pin "5") (pinfunction "5_5") (pintype "passive"))
      (node (ref "CF12.2") (pin "6") (pinfunction "6_6") (pintype "passive"))
      (node (ref "CF13.2") (pin "5") (pinfunction "5_5") (pintype "passive"))
      (node (ref "CF13.2") (pin "6") (pinfunction "6_6") (pintype "passive"))
      (node (ref "CF14.2") (pin "5") (pinfunction "5_5") (pintype "passive"))
      (node (ref "CF14.2") (pin "6") (pinfunction "6_6") (pintype "passive"))
      (node (ref "CF15.2") (pin "5") (pinfunction "5_5") (pintype "passive"))
      (node (ref "CF15.2") (pin "6") (pinfunction "6_6") (pintype "passive"))
      (node (ref "CF16.2") (pin "5") (pinfunction "5_5") (pintype "passive"))
      (node (ref "CF16.2") (pin "6") (pinfunction "6_6") (pintype "passive"))
      (node (ref "CF17.2") (pin "5") (pinfunction "5_5") (pintype "passive"))
      (node (ref "CF17.2") (pin "6") (pinfunction "6_6") (pintype "passive"))
      (node (ref "CF18.2") (pin "5") (pinfunction "5_5") (pintype "passive"))
      (node (ref "CF18.2") (pin "6") (pinfunction "6_6") (pintype "passive"))
      (node (ref "CF19.2") (pin "5") (pinfunction "5_5") (pintype "passive"))
      (node (ref "CF19.2") (pin "6") (pinfunction "6_6") (pintype "passive"))
      (node (ref "CF2.2") (pin "5") (pinfunction "5_5") (pintype "passive"))
      (node (ref "CF2.2") (pin "6") (pinfunction "6_6") (pintype "passive"))
      (node (ref "CF2.3") (pin "5") (pinfunction "5_5") (pintype "passive"))
      (node (ref "CF2.3") (pin "6") (pinfunction "6_6") (pintype "passive"))
      (node (ref "CF2.4") (pin "5") (pinfunction "5_5") (pintype "passive"))
      (node (ref "CF2.4") (pin "6") (pinfunction "6_6") (pintype "passive"))
      (node (ref "CF3.2") (pin "5") (pinfunction "5_5") (pintype "passive"))
      (node (ref "CF3.2") (pin "6") (pinfunction "6_6") (pintype "passive"))
      (node (ref "CF4.2") (pin "5") (pinfunction "5_5") (pintype "passive"))
      (node (ref "CF4.2") (pin "6") (pinfunction "6_6") (pintype "passive"))
      (node (ref "CF5.2") (pin "5") (pinfunction "5_5") (pintype "passive"))
      (node (ref "CF5.2") (pin "6") (pinfunction "6_6") (pintype "passive"))
      (node (ref "CF6.2") (pin "5") (pinfunction "5_5") (pintype "passive"))
      (node (ref "CF6.2") (pin "6") (pinfunction "6_6") (pintype "passive"))
      (node (ref "CF7.2") (pin "5") (pinfunction "5_5") (pintype "passive"))
      (node (ref "CF7.2") (pin "6") (pinfunction "6_6") (pintype "passive"))
      (node (ref "CF8.2") (pin "5") (pinfunction "5_5") (pintype "passive"))
      (node (ref "CF8.2") (pin "6") (pinfunction "6_6") (pintype "passive"))
    )
    (net (code "30") (name "SPARE4") (class "Default")
      (node (ref "CF12.2") (pin "3") (pinfunction "3_3") (pintype "passive"))
      (node (ref "CF12.2") (pin "4") (pinfunction "4_4") (pintype "passive"))
      (node (ref "CF13.2") (pin "3") (pinfunction "3_3") (pintype "passive"))
      (node (ref "CF13.2") (pin "4") (pinfunction "4_4") (pintype "passive"))
      (node (ref "CF14.2") (pin "3") (pinfunction "3_3") (pintype "passive"))
      (node (ref "CF14.2") (pin "4") (pinfunction "4_4") (pintype "passive"))
      (node (ref "CF15.2") (pin "3") (pinfunction "3_3") (pintype "passive"))
      (node (ref "CF15.2") (pin "4") (pinfunction "4_4") (pintype "passive"))
      (node (ref "CF16.2") (pin "3") (pinfunction "3_3") (pintype "passive"))
      (node (ref "CF16.2") (pin "4") (pinfunction "4_4") (pintype "passive"))
      (node (ref "CF17.2") (pin "3") (pinfunction "3_3") (pintype "passive"))
      (node (ref "CF17.2") (pin "4") (pinfunction "4_4") (pintype "passive"))
      (node (ref "CF18.2") (pin "3") (pinfunction "3_3") (pintype "passive"))
      (node (ref "CF18.2") (pin "4") (pinfunction "4_4") (pintype "passive"))
      (node (ref "CF19.2") (pin "3") (pinfunction "3_3") (pintype "passive"))
      (node (ref "CF19.2") (pin "4") (pinfunction "4_4") (pintype "passive"))
      (node (ref "CF2.2") (pin "3") (pinfunction "3_3") (pintype "passive"))
      (node (ref "CF2.2") (pin "4") (pinfunction "4_4") (pintype "passive"))
      (node (ref "CF2.3") (pin "3") (pinfunction "3_3") (pintype "passive"))
      (node (ref "CF2.3") (pin "4") (pinfunction "4_4") (pintype "passive"))
      (node (ref "CF2.4") (pin "3") (pinfunction "3_3") (pintype "passive"))
      (node (ref "CF2.4") (pin "4") (pinfunction "4_4") (pintype "passive"))
      (node (ref "CF3.2") (pin "3") (pinfunction "3_3") (pintype "passive"))
      (node (ref "CF3.2") (pin "4") (pinfunction "4_4") (pintype "passive"))
      (node (ref "CF4.2") (pin "3") (pinfunction "3_3") (pintype "passive"))
      (node (ref "CF4.2") (pin "4") (pinfunction "4_4") (pintype "passive"))
      (node (ref "CF5.2") (pin "3") (pinfunction "3_3") (pintype "passive"))
      (node (ref "CF5.2") (pin "4") (pinfunction "4_4") (pintype "passive"))
      (node (ref "CF6.2") (pin "3") (pinfunction "3_3") (pintype "passive"))
      (node (ref "CF6.2") (pin "4") (pinfunction "4_4") (pintype "passive"))
      (node (ref "CF7.2") (pin "3") (pinfunction "3_3") (pintype "passive"))
      (node (ref "CF7.2") (pin "4") (pinfunction "4_4") (pintype "passive"))
      (node (ref "CF8.2") (pin "3") (pinfunction "3_3") (pintype "passive"))
      (node (ref "CF8.2") (pin "4") (pinfunction "4_4") (pintype "passive"))
    )
    (net (code "31") (name "SPARE5") (class "Default")
      (node (ref "CF12.2") (pin "1") (pinfunction "1_1") (pintype "passive"))
      (node (ref "CF12.2") (pin "2") (pinfunction "2_2") (pintype "passive"))
      (node (ref "CF13.2") (pin "1") (pinfunction "1_1") (pintype "passive"))
      (node (ref "CF13.2") (pin "2") (pinfunction "2_2") (pintype "passive"))
      (node (ref "CF14.2") (pin "1") (pinfunction "1_1") (pintype "passive"))
      (node (ref "CF14.2") (pin "2") (pinfunction "2_2") (pintype "passive"))
      (node (ref "CF15.2") (pin "1") (pinfunction "1_1") (pintype "passive"))
      (node (ref "CF15.2") (pin "2") (pinfunction "2_2") (pintype "passive"))
      (node (ref "CF16.2") (pin "1") (pinfunction "1_1") (pintype "passive"))
      (node (ref "CF16.2") (pin "2") (pinfunction "2_2") (pintype "passive"))
      (node (ref "CF17.2") (pin "1") (pinfunction "1_1") (pintype "passive"))
      (node (ref "CF17.2") (pin "2") (pinfunction "2_2") (pintype "passive"))
      (node (ref "CF18.2") (pin "1") (pinfunction "1_1") (pintype "passive"))
      (node (ref "CF18.2") (pin "2") (pinfunction "2_2") (pintype "passive"))
      (node (ref "CF19.2") (pin "1") (pinfunction "1_1") (pintype "passive"))
      (node (ref "CF19.2") (pin "2") (pinfunction "2_2") (pintype "passive"))
      (node (ref "CF2.2") (pin "1") (pinfunction "1_1") (pintype "passive"))
      (node (ref "CF2.2") (pin "2") (pinfunction "2_2") (pintype "passive"))
      (node (ref "CF2.3") (pin "1") (pinfunction "1_1") (pintype "passive"))
      (node (ref "CF2.3") (pin "2") (pinfunction "2_2") (pintype "passive"))
      (node (ref "CF2.4") (pin "1") (pinfunction "1_1") (pintype "passive"))
      (node (ref "CF2.4") (pin "2") (pinfunction "2_2") (pintype "passive"))
      (node (ref "CF3.2") (pin "1") (pinfunction "1_1") (pintype "passive"))
      (node (ref "CF3.2") (pin "2") (pinfunction "2_2") (pintype "passive"))
      (node (ref "CF4.2") (pin "1") (pinfunction "1_1") (pintype "passive"))
      (node (ref "CF4.2") (pin "2") (pinfunction "2_2") (pintype "passive"))
      (node (ref "CF5.2") (pin "1") (pinfunction "1_1") (pintype "passive"))
      (node (ref "CF5.2") (pin "2") (pinfunction "2_2") (pintype "passive"))
      (node (ref "CF6.2") (pin "1") (pinfunction "1_1") (pintype "passive"))
      (node (ref "CF6.2") (pin "2") (pinfunction "2_2") (pintype "passive"))
      (node (ref "CF7.2") (pin "1") (pinfunction "1_1") (pintype "passive"))
      (node (ref "CF7.2") (pin "2") (pinfunction "2_2") (pintype "passive"))
      (node (ref "CF8.2") (pin "1") (pinfunction "1_1") (pintype "passive"))
      (node (ref "CF8.2") (pin "2") (pinfunction "2_2") (pintype "passive"))
    )
    (net (code "32") (name "U-TURNSTILE") (class "Default")
      (node (ref "CM20.2") (pin "RF-DOWN") (pinfunction "RF_RF-DOWN") (pintype "passive"))
      (node (ref "CM4.3") (pin "RF-DOWN") (pinfunction "RF_RF-DOWN") (pintype "passive"))
    )
    (net (code "33") (name "VBUS") (class "Default")
      (node (ref "CF12.2") (pin "21") (pinfunction "21_21") (pintype "passive"))
      (node (ref "CF12.2") (pin "22") (pinfunction "22_22") (pintype "passive"))
      (node (ref "CF12.2") (pin "23") (pinfunction "23_23") (pintype "passive"))
      (node (ref "CF12.2") (pin "24") (pinfunction "24_24") (pintype "passive"))
      (node (ref "CF12.2") (pin "25") (pinfunction "25_25") (pintype "passive"))
      (node (ref "CF12.2") (pin "26") (pinfunction "26_26") (pintype "passive"))
      (node (ref "CF13.2") (pin "21") (pinfunction "21_21") (pintype "passive"))
      (node (ref "CF13.2") (pin "22") (pinfunction "22_22") (pintype "passive"))
      (node (ref "CF13.2") (pin "23") (pinfunction "23_23") (pintype "passive"))
      (node (ref "CF13.2") (pin "24") (pinfunction "24_24") (pintype "passive"))
      (node (ref "CF13.2") (pin "25") (pinfunction "25_25") (pintype "passive"))
      (node (ref "CF13.2") (pin "26") (pinfunction "26_26") (pintype "passive"))
      (node (ref "CF14.2") (pin "21") (pinfunction "21_21") (pintype "passive"))
      (node (ref "CF14.2") (pin "22") (pinfunction "22_22") (pintype "passive"))
      (node (ref "CF14.2") (pin "23") (pinfunction "23_23") (pintype "passive"))
      (node (ref "CF14.2") (pin "24") (pinfunction "24_24") (pintype "passive"))
      (node (ref "CF14.2") (pin "25") (pinfunction "25_25") (pintype "passive"))
      (node (ref "CF14.2") (pin "26") (pinfunction "26_26") (pintype "passive"))
      (node (ref "CF15.2") (pin "21") (pinfunction "21_21") (pintype "passive"))
      (node (ref "CF15.2") (pin "22") (pinfunction "22_22") (pintype "passive"))
      (node (ref "CF15.2") (pin "23") (pinfunction "23_23") (pintype "passive"))
      (node (ref "CF15.2") (pin "24") (pinfunction "24_24") (pintype "passive"))
      (node (ref "CF15.2") (pin "25") (pinfunction "25_25") (pintype "passive"))
      (node (ref "CF15.2") (pin "26") (pinfunction "26_26") (pintype "passive"))
      (node (ref "CF16.2") (pin "21") (pinfunction "21_21") (pintype "passive"))
      (node (ref "CF16.2") (pin "22") (pinfunction "22_22") (pintype "passive"))
      (node (ref "CF16.2") (pin "23") (pinfunction "23_23") (pintype "passive"))
      (node (ref "CF16.2") (pin "24") (pinfunction "24_24") (pintype "passive"))
      (node (ref "CF16.2") (pin "25") (pinfunction "25_25") (pintype "passive"))
      (node (ref "CF16.2") (pin "26") (pinfunction "26_26") (pintype "passive"))
      (node (ref "CF17.2") (pin "21") (pinfunction "21_21") (pintype "passive"))
      (node (ref "CF17.2") (pin "22") (pinfunction "22_22") (pintype "passive"))
      (node (ref "CF17.2") (pin "23") (pinfunction "23_23") (pintype "passive"))
      (node (ref "CF17.2") (pin "24") (pinfunction "24_24") (pintype "passive"))
      (node (ref "CF17.2") (pin "25") (pinfunction "25_25") (pintype "passive"))
      (node (ref "CF17.2") (pin "26") (pinfunction "26_26") (pintype "passive"))
      (node (ref "CF18.2") (pin "21") (pinfunction "21_21") (pintype "passive"))
      (node (ref "CF18.2") (pin "22") (pinfunction "22_22") (pintype "passive"))
      (node (ref "CF18.2") (pin "23") (pinfunction "23_23") (pintype "passive"))
      (node (ref "CF18.2") (pin "24") (pinfunction "24_24") (pintype "passive"))
      (node (ref "CF18.2") (pin "25") (pinfunction "25_25") (pintype "passive"))
      (node (ref "CF18.2") (pin "26") (pinfunction "26_26") (pintype "passive"))
      (node (ref "CF19.2") (pin "21") (pinfunction "21_21") (pintype "passive"))
      (node (ref "CF19.2") (pin "22") (pinfunction "22_22") (pintype "passive"))
      (node (ref "CF19.2") (pin "23") (pinfunction "23_23") (pintype "passive"))
      (node (ref "CF19.2") (pin "24") (pinfunction "24_24") (pintype "passive"))
      (node (ref "CF19.2") (pin "25") (pinfunction "25_25") (pintype "passive"))
      (node (ref "CF19.2") (pin "26") (pinfunction "26_26") (pintype "passive"))
      (node (ref "CF2.2") (pin "21") (pinfunction "21_21") (pintype "passive"))
      (node (ref "CF2.2") (pin "22") (pinfunction "22_22") (pintype "passive"))
      (node (ref "CF2.2") (pin "23") (pinfunction "23_23") (pintype "passive"))
      (node (ref "CF2.2") (pin "24") (pinfunction "24_24") (pintype "passive"))
      (node (ref "CF2.2") (pin "25") (pinfunction "25_25") (pintype "passive"))
      (node (ref "CF2.2") (pin "26") (pinfunction "26_26") (pintype "passive"))
      (node (ref "CF2.3") (pin "21") (pinfunction "21_21") (pintype "passive"))
      (node (ref "CF2.3") (pin "22") (pinfunction "22_22") (pintype "passive"))
      (node (ref "CF2.3") (pin "23") (pinfunction "23_23") (pintype "passive"))
      (node (ref "CF2.3") (pin "24") (pinfunction "24_24") (pintype "passive"))
      (node (ref "CF2.3") (pin "25") (pinfunction "25_25") (pintype "passive"))
      (node (ref "CF2.3") (pin "26") (pinfunction "26_26") (pintype "passive"))
      (node (ref "CF2.4") (pin "21") (pinfunction "21_21") (pintype "passive"))
      (node (ref "CF2.4") (pin "22") (pinfunction "22_22") (pintype "passive"))
      (node (ref "CF2.4") (pin "23") (pinfunction "23_23") (pintype "passive"))
      (node (ref "CF2.4") (pin "24") (pinfunction "24_24") (pintype "passive"))
      (node (ref "CF2.4") (pin "25") (pinfunction "25_25") (pintype "passive"))
      (node (ref "CF2.4") (pin "26") (pinfunction "26_26") (pintype "passive"))
      (node (ref "CF3.2") (pin "21") (pinfunction "21_21") (pintype "passive"))
      (node (ref "CF3.2") (pin "22") (pinfunction "22_22") (pintype "passive"))
      (node (ref "CF3.2") (pin "23") (pinfunction "23_23") (pintype "passive"))
      (node (ref "CF3.2") (pin "24") (pinfunction "24_24") (pintype "passive"))
      (node (ref "CF3.2") (pin "25") (pinfunction "25_25") (pintype "passive"))
      (node (ref "CF3.2") (pin "26") (pinfunction "26_26") (pintype "passive"))
      (node (ref "CF4.2") (pin "21") (pinfunction "21_21") (pintype "passive"))
      (node (ref "CF4.2") (pin "22") (pinfunction "22_22") (pintype "passive"))
      (node (ref "CF4.2") (pin "23") (pinfunction "23_23") (pintype "passive"))
      (node (ref "CF4.2") (pin "24") (pinfunction "24_24") (pintype "passive"))
      (node (ref "CF4.2") (pin "25") (pinfunction "25_25") (pintype "passive"))
      (node (ref "CF4.2") (pin "26") (pinfunction "26_26") (pintype "passive"))
      (node (ref "CF5.2") (pin "21") (pinfunction "21_21") (pintype "passive"))
      (node (ref "CF5.2") (pin "22") (pinfunction "22_22") (pintype "passive"))
      (node (ref "CF5.2") (pin "23") (pinfunction "23_23") (pintype "passive"))
      (node (ref "CF5.2") (pin "24") (pinfunction "24_24") (pintype "passive"))
      (node (ref "CF5.2") (pin "25") (pinfunction "25_25") (pintype "passive"))
      (node (ref "CF5.2") (pin "26") (pinfunction "26_26") (pintype "passive"))
      (node (ref "CF6.2") (pin "21") (pinfunction "21_21") (pintype "passive"))
      (node (ref "CF6.2") (pin "22") (pinfunction "22_22") (pintype "passive"))
      (node (ref "CF6.2") (pin "23") (pinfunction "23_23") (pintype "passive"))
      (node (ref "CF6.2") (pin "24") (pinfunction "24_24") (pintype "passive"))
      (node (ref "CF6.2") (pin "25") (pinfunction "25_25") (pintype "passive"))
      (node (ref "CF6.2") (pin "26") (pinfunction "26_26") (pintype "passive"))
      (node (ref "CF7.2") (pin "21") (pinfunction "21_21") (pintype "passive"))
      (node (ref "CF7.2") (pin "22") (pinfunction "22_22") (pintype "passive"))
      (node (ref "CF7.2") (pin "23") (pinfunction "23_23") (pintype "passive"))
      (node (ref "CF7.2") (pin "24") (pinfunction "24_24") (pintype "passive"))
      (node (ref "CF7.2") (pin "25") (pinfunction "25_25") (pintype "passive"))
      (node (ref "CF7.2") (pin "26") (pinfunction "26_26") (pintype "passive"))
      (node (ref "CF8.2") (pin "21") (pinfunction "21_21") (pintype "passive"))
      (node (ref "CF8.2") (pin "22") (pinfunction "22_22") (pintype "passive"))
      (node (ref "CF8.2") (pin "23") (pinfunction "23_23") (pintype "passive"))
      (node (ref "CF8.2") (pin "24") (pinfunction "24_24") (pintype "passive"))
      (node (ref "CF8.2") (pin "25") (pinfunction "25_25") (pintype "passive"))
      (node (ref "CF8.2") (pin "26") (pinfunction "26_26") (pintype "passive"))
    )
    (net (code "34") (name "~{SD}") (class "Default")
      (node (ref "CF12.2") (pin "39") (pinfunction "39_39") (pintype "passive"))
      (node (ref "CF12.2") (pin "40") (pinfunction "40_40") (pintype "passive"))
      (node (ref "CF13.2") (pin "39") (pinfunction "39_39") (pintype "passive"))
      (node (ref "CF13.2") (pin "40") (pinfunction "40_40") (pintype "passive"))
      (node (ref "CF14.2") (pin "39") (pinfunction "39_39") (pintype "passive"))
      (node (ref "CF14.2") (pin "40") (pinfunction "40_40") (pintype "passive"))
      (node (ref "CF15.2") (pin "39") (pinfunction "39_39") (pintype "passive"))
      (node (ref "CF15.2") (pin "40") (pinfunction "40_40") (pintype "passive"))
      (node (ref "CF16.2") (pin "39") (pinfunction "39_39") (pintype "passive"))
      (node (ref "CF16.2") (pin "40") (pinfunction "40_40") (pintype "passive"))
      (node (ref "CF17.2") (pin "39") (pinfunction "39_39") (pintype "passive"))
      (node (ref "CF17.2") (pin "40") (pinfunction "40_40") (pintype "passive"))
      (node (ref "CF18.2") (pin "39") (pinfunction "39_39") (pintype "passive"))
      (node (ref "CF18.2") (pin "40") (pinfunction "40_40") (pintype "passive"))
      (node (ref "CF19.2") (pin "39") (pinfunction "39_39") (pintype "passive"))
      (node (ref "CF19.2") (pin "40") (pinfunction "40_40") (pintype "passive"))
      (node (ref "CF2.2") (pin "39") (pinfunction "39_39") (pintype "passive"))
      (node (ref "CF2.2") (pin "40") (pinfunction "40_40") (pintype "passive"))
      (node (ref "CF2.3") (pin "39") (pinfunction "39_39") (pintype "passive"))
      (node (ref "CF2.3") (pin "40") (pinfunction "40_40") (pintype "passive"))
      (node (ref "CF2.4") (pin "39") (pinfunction "39_39") (pintype "passive"))
      (node (ref "CF2.4") (pin "40") (pinfunction "40_40") (pintype "passive"))
      (node (ref "CF3.2") (pin "39") (pinfunction "39_39") (pintype "passive"))
      (node (ref "CF3.2") (pin "40") (pinfunction "40_40") (pintype "passive"))
      (node (ref "CF4.2") (pin "39") (pinfunction "39_39") (pintype "passive"))
      (node (ref "CF4.2") (pin "40") (pinfunction "40_40") (pintype "passive"))
      (node (ref "CF5.2") (pin "39") (pinfunction "39_39") (pintype "passive"))
      (node (ref "CF5.2") (pin "40") (pinfunction "40_40") (pintype "passive"))
      (node (ref "CF6.2") (pin "39") (pinfunction "39_39") (pintype "passive"))
      (node (ref "CF6.2") (pin "40") (pinfunction "40_40") (pintype "passive"))
      (node (ref "CF7.2") (pin "39") (pinfunction "39_39") (pintype "passive"))
      (node (ref "CF7.2") (pin "40") (pinfunction "40_40") (pintype "passive"))
      (node (ref "CF8.2") (pin "39") (pinfunction "39_39") (pintype "passive"))
      (node (ref "CF8.2") (pin "40") (pinfunction "40_40") (pintype "passive"))
    )
  )
)
